# Sheet_1_2023-02-03.net
KiCad netlist of a schematic drawn in Altium Designer
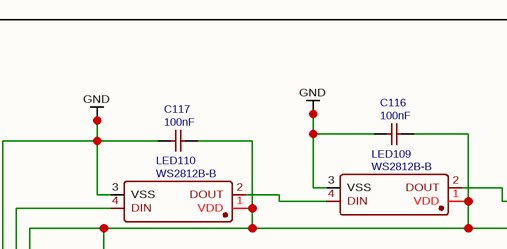
[diagram p0: Sheet_1_2023-02-03.schdoc, row 1 of 4 left]
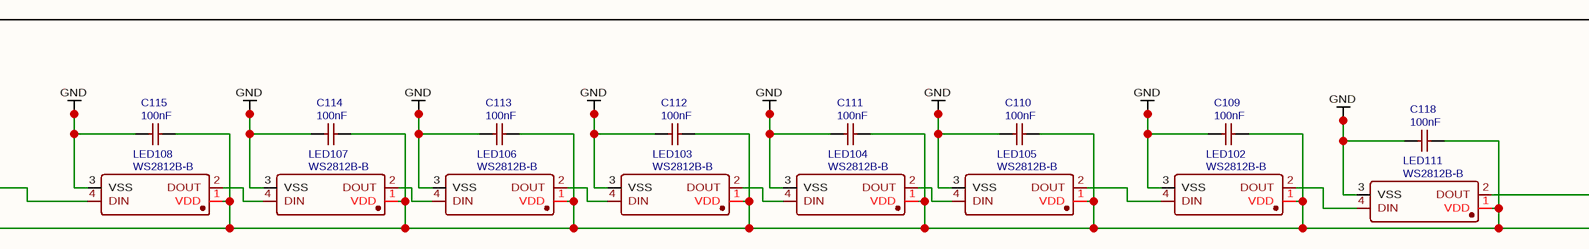
[diagram p1: Sheet_1_2023-02-03.schdoc, row 1 of 4 middle]
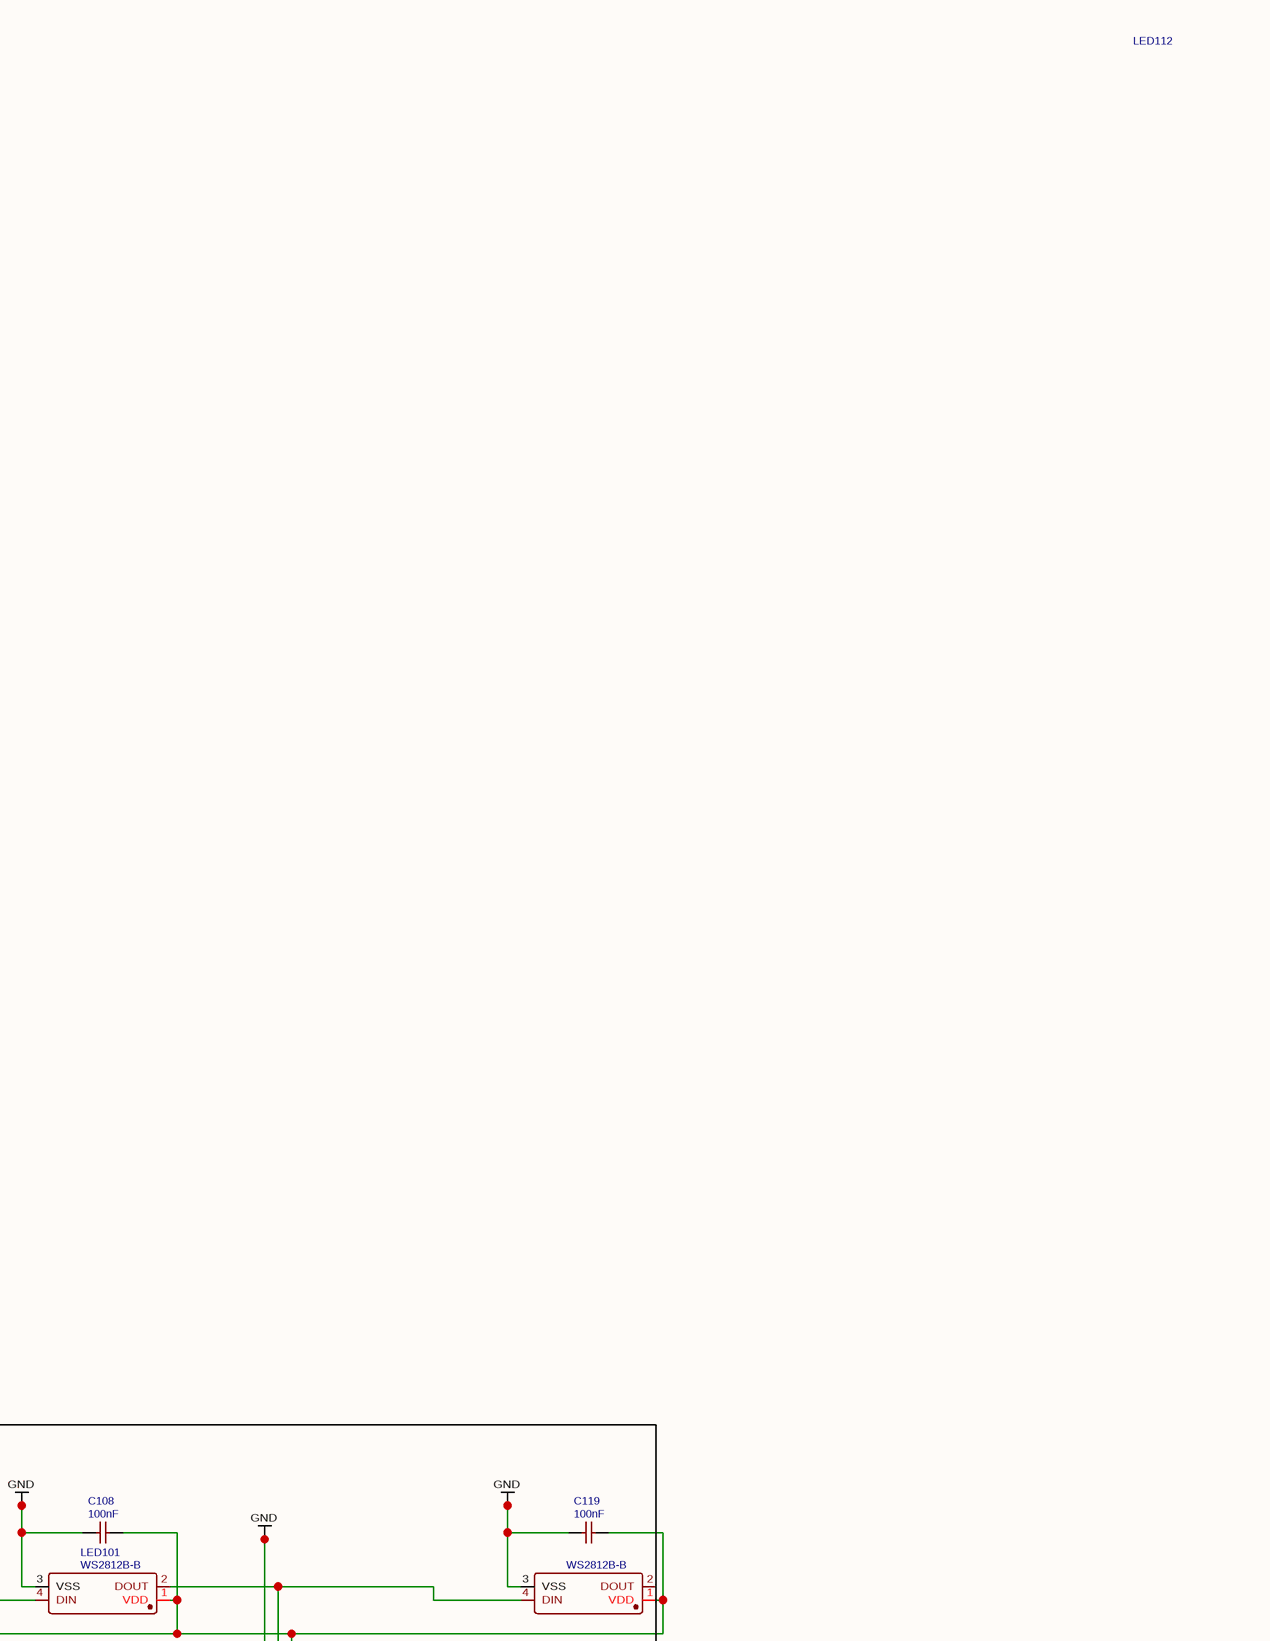
[diagram p2: Sheet_1_2023-02-03.schdoc, row 1 of 4 right]
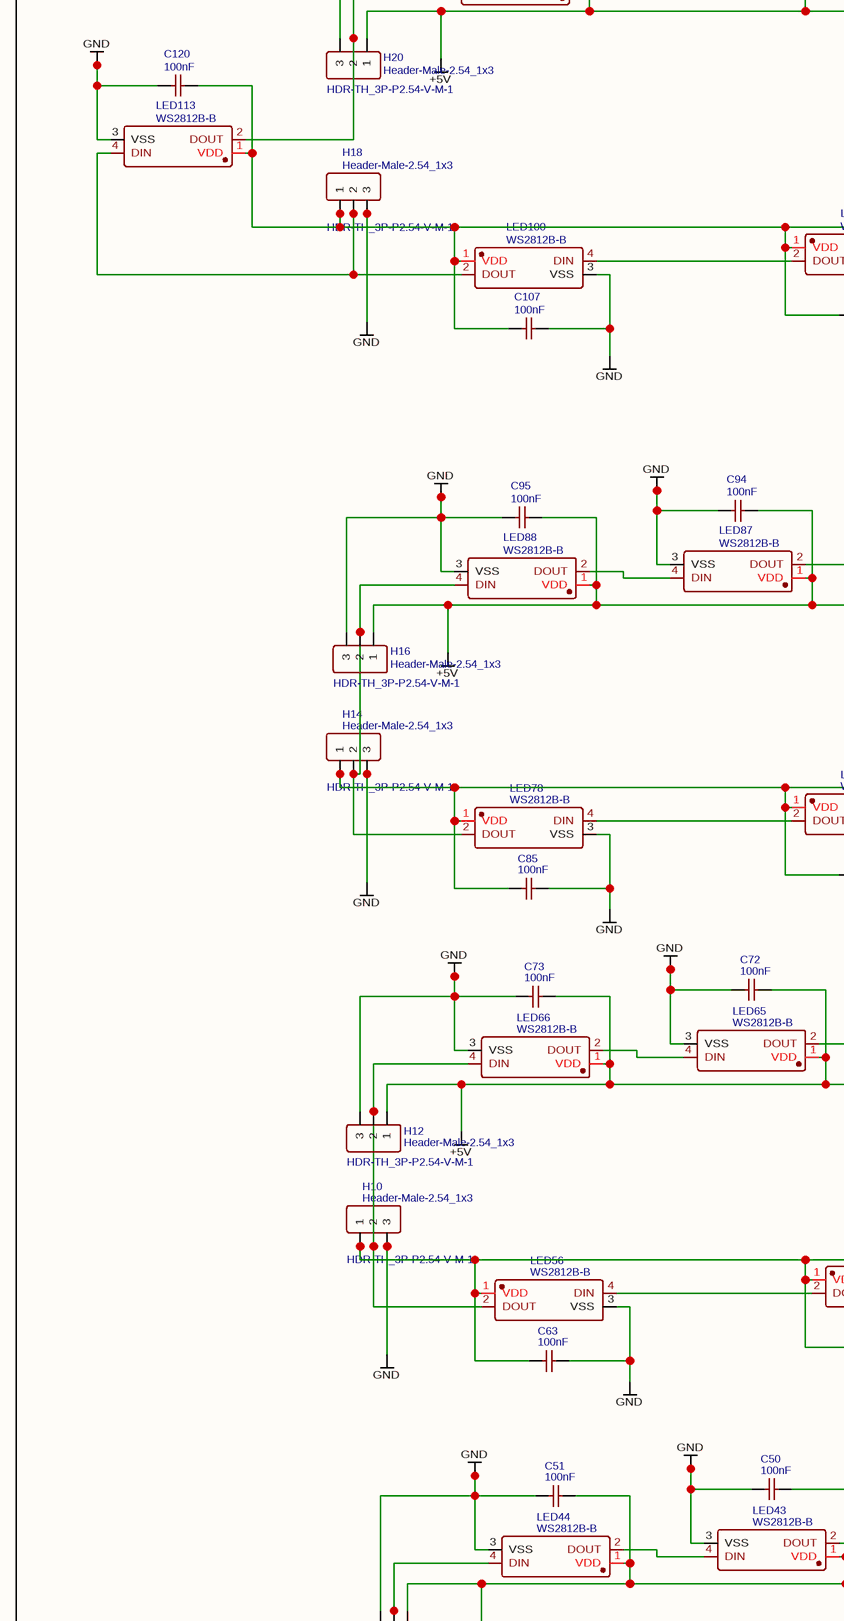
[diagram p3: Sheet_1_2023-02-03.schdoc, row 2 of 4 left]
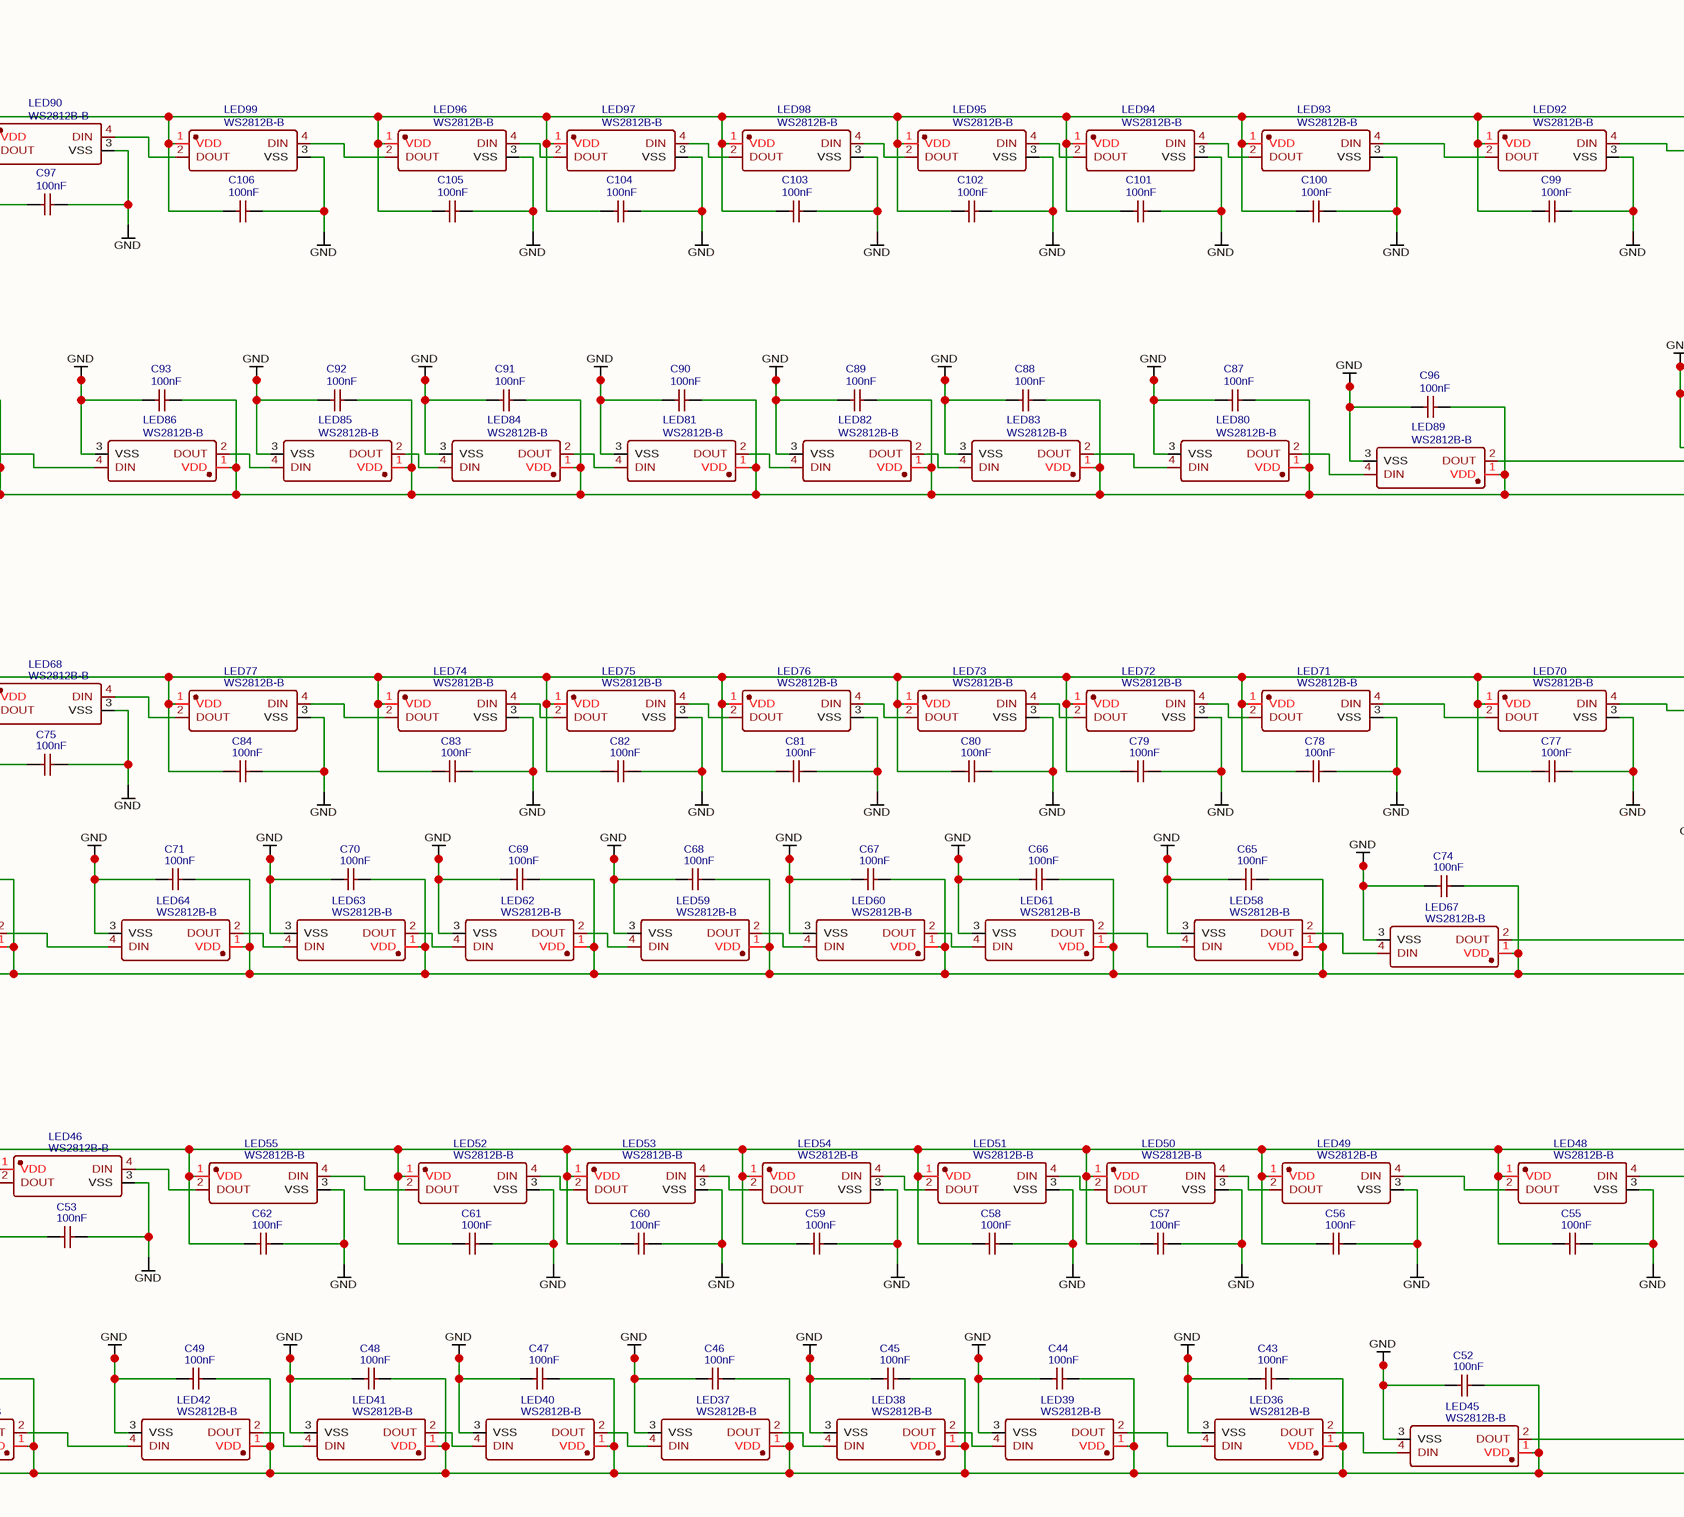
[diagram p4: Sheet_1_2023-02-03.schdoc, row 2 of 4 middle]
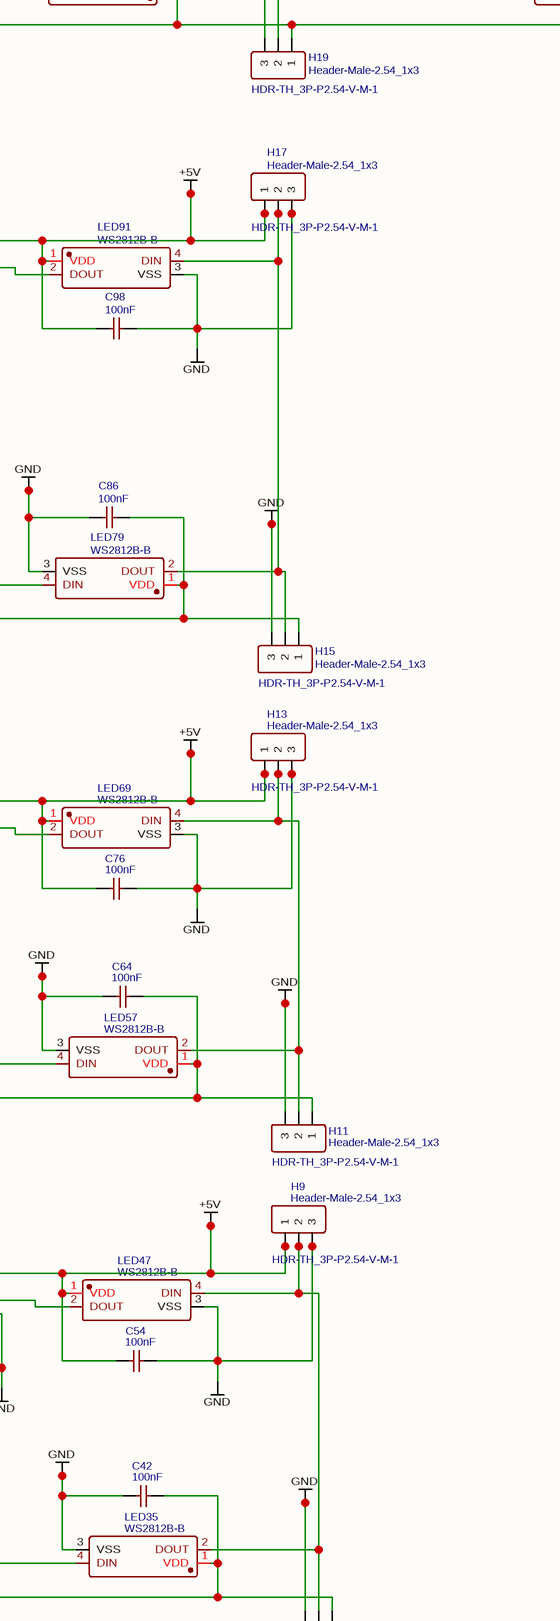
[diagram p5: Sheet_1_2023-02-03.schdoc, row 2 of 4 right]
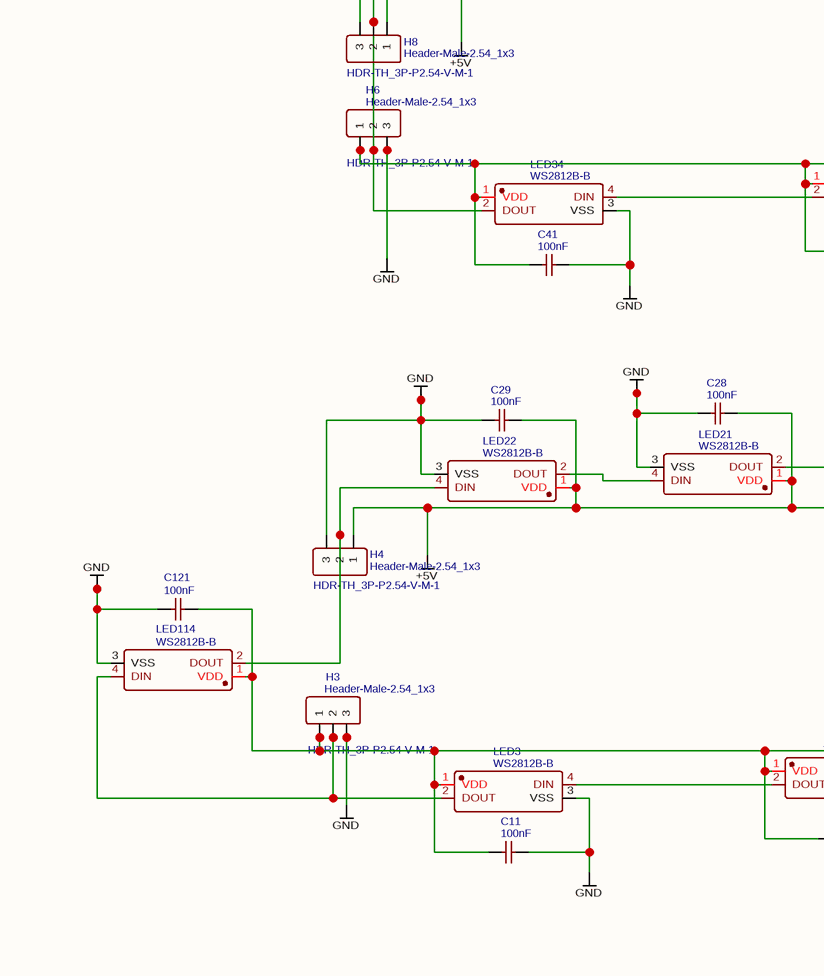
[diagram p6: Sheet_1_2023-02-03.schdoc, row 3 of 4 left]
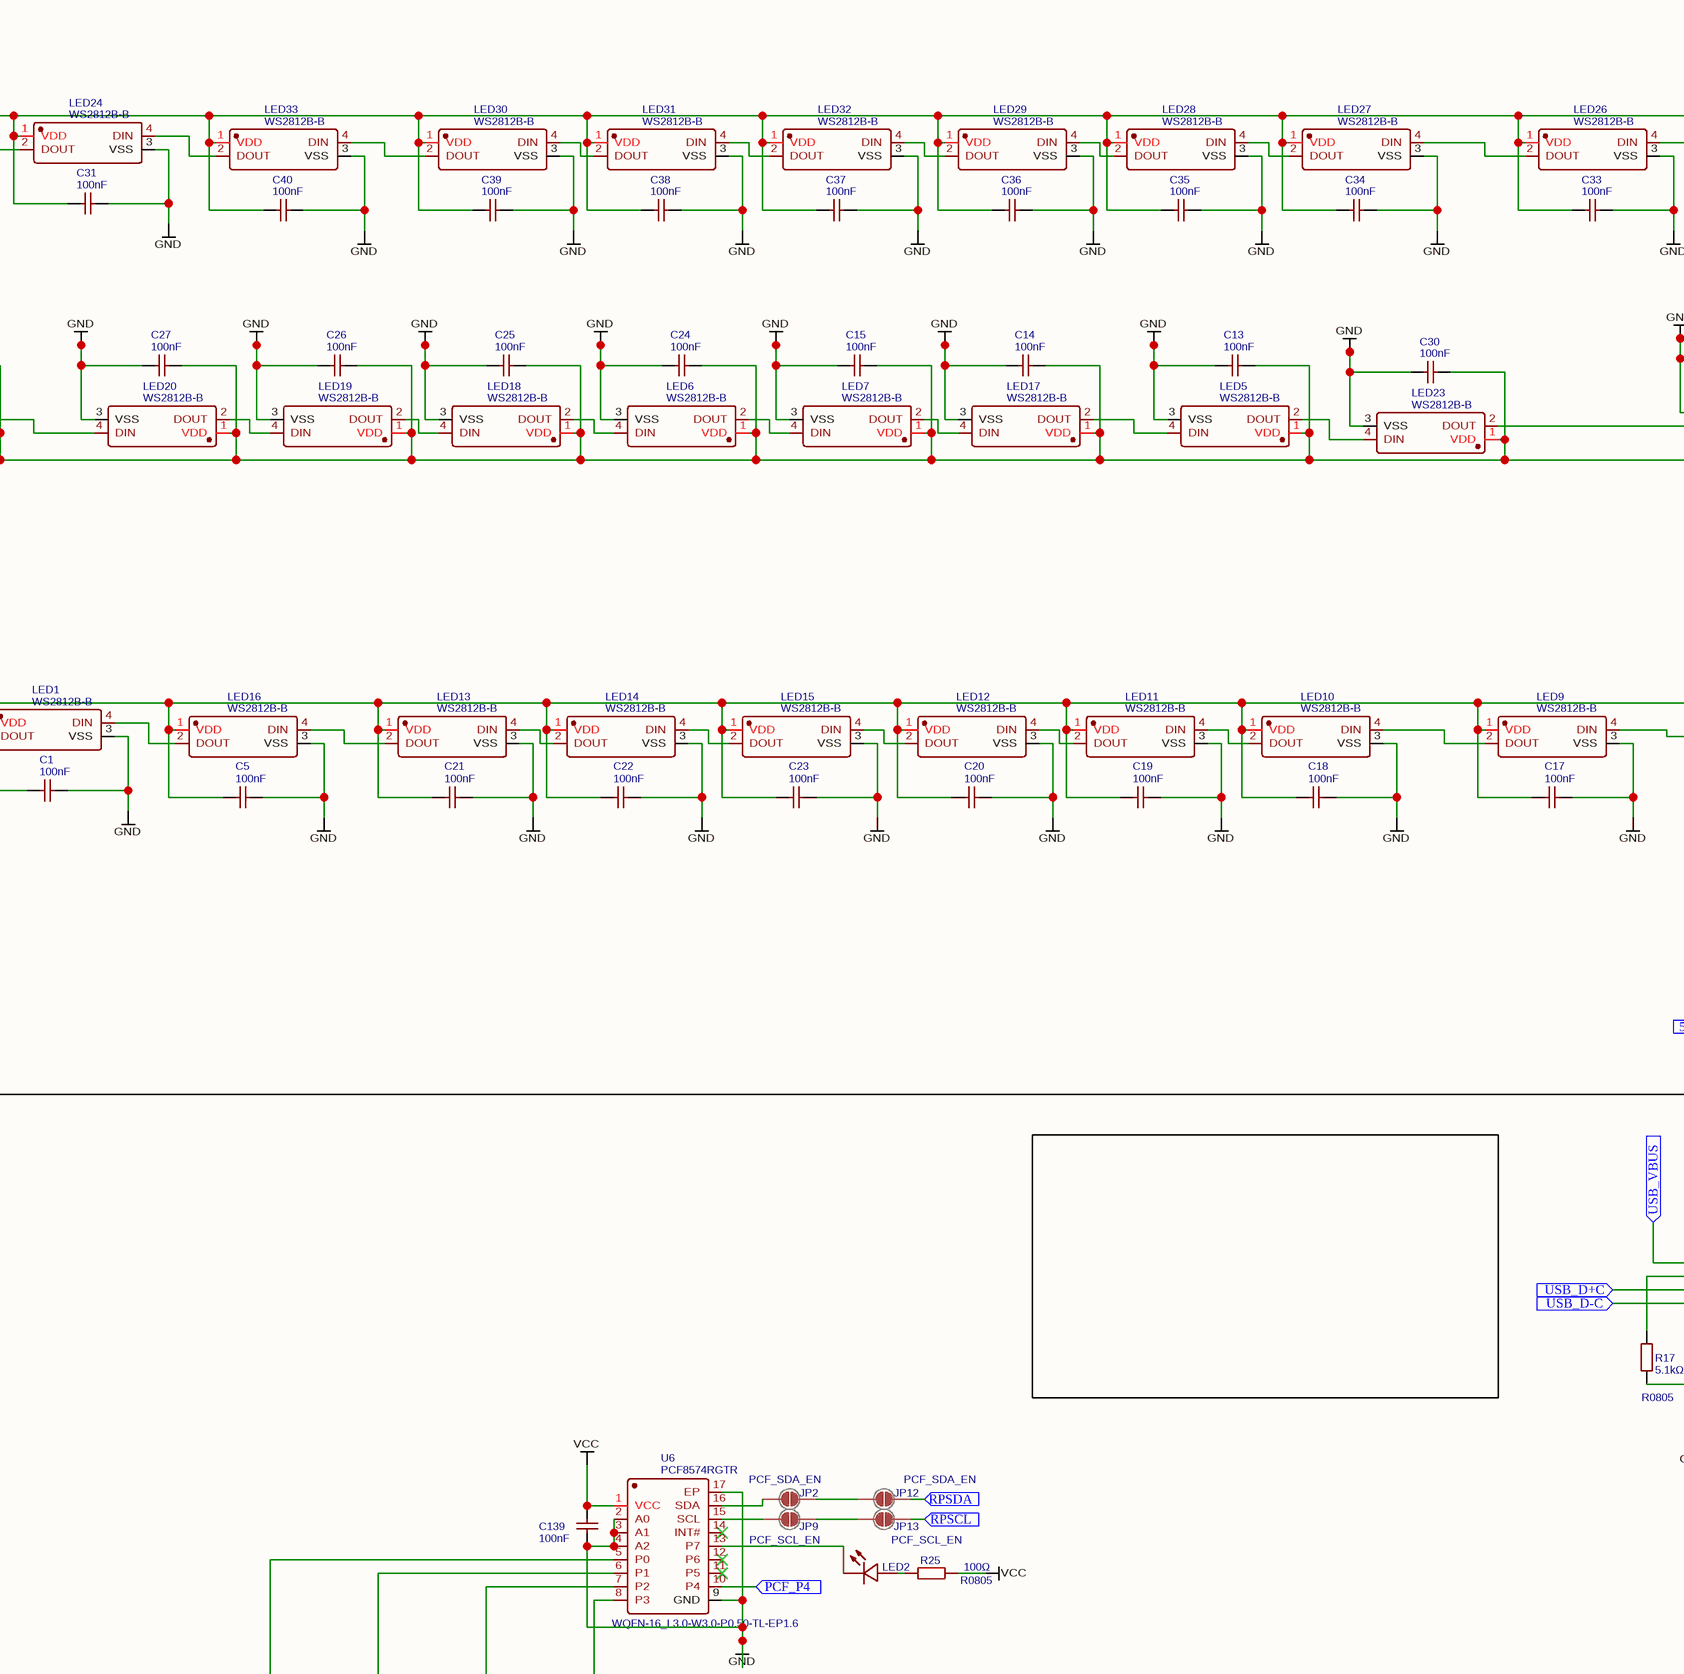
[diagram p7: Sheet_1_2023-02-03.schdoc, row 3 of 4 middle]
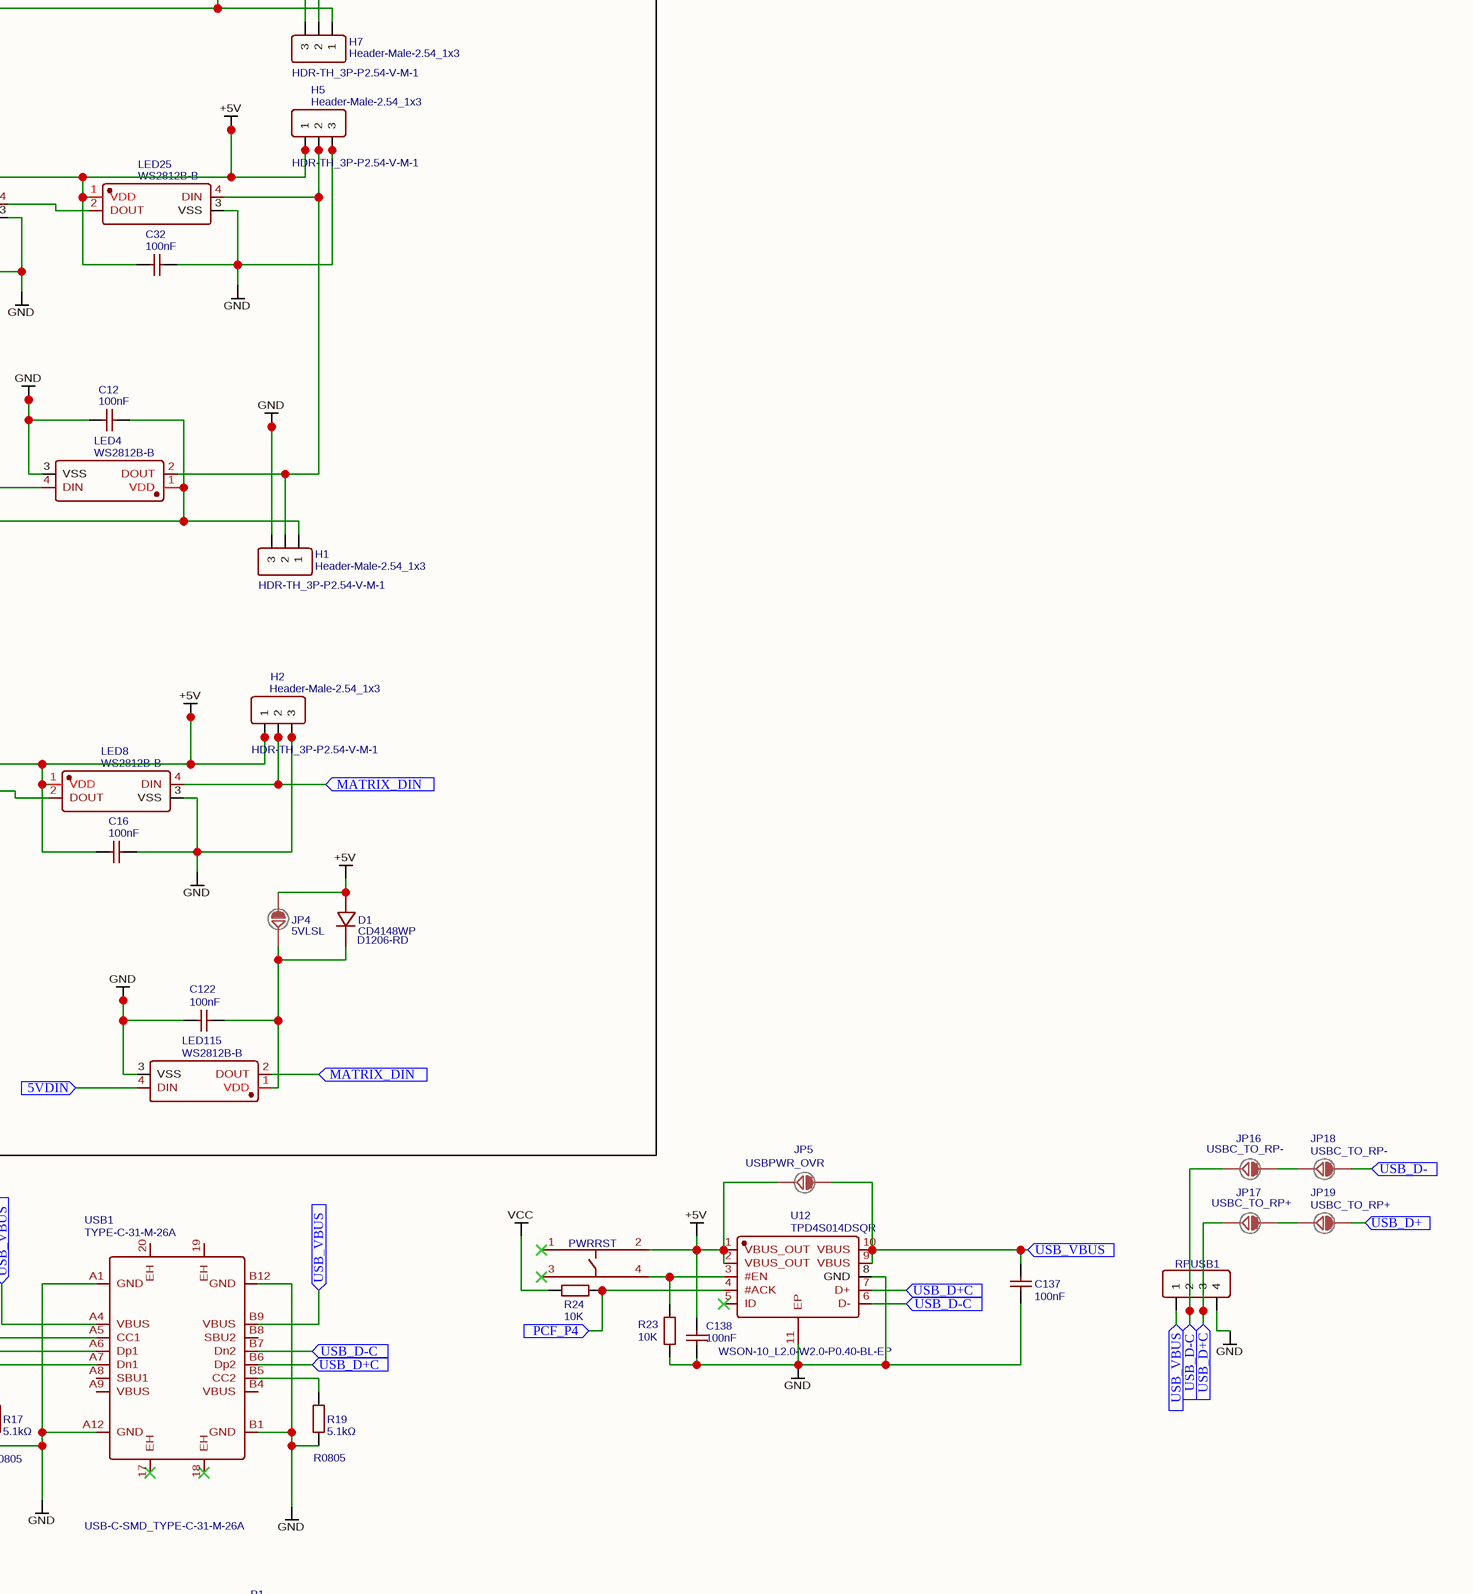
[diagram p8: Sheet_1_2023-02-03.schdoc, row 3 of 4 right]
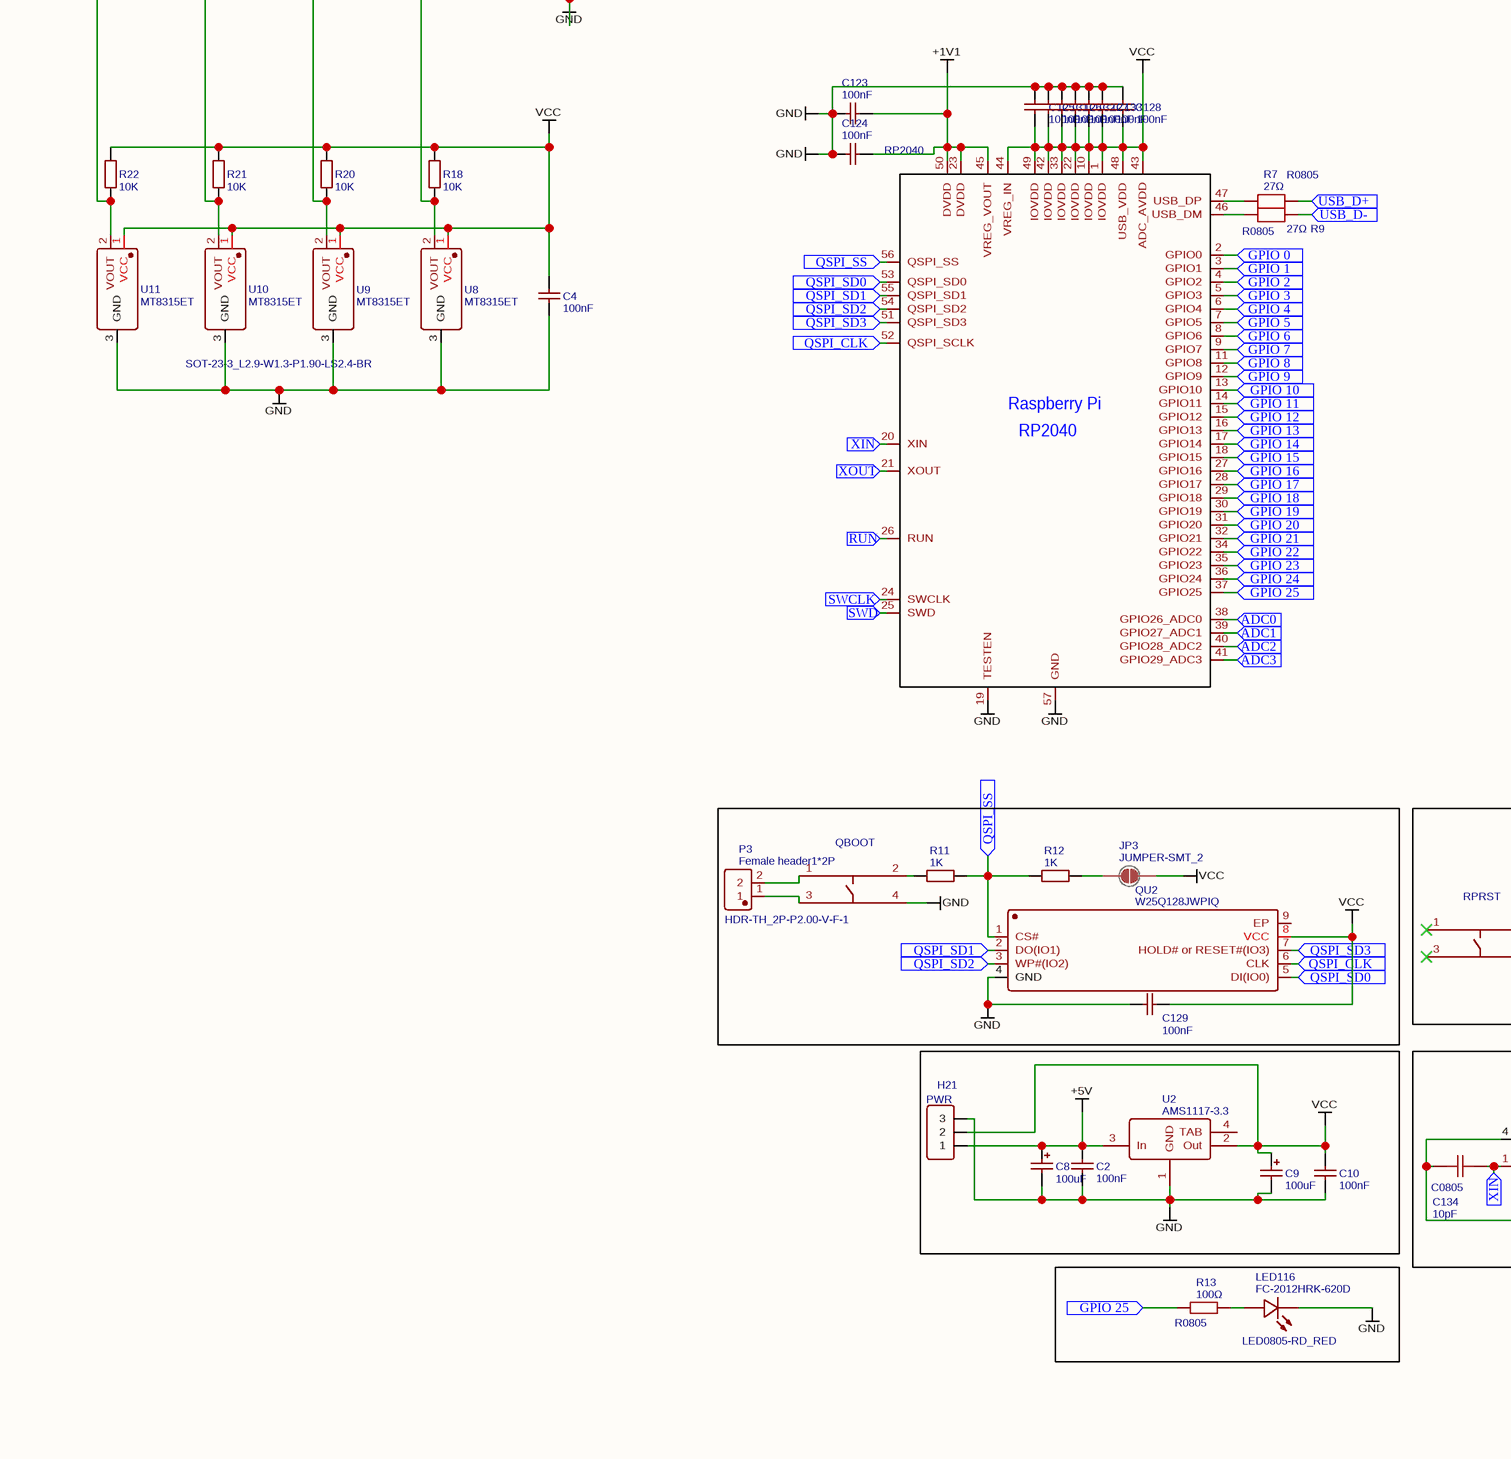
[diagram p9: Sheet_1_2023-02-03.schdoc, row 4 of 4 middle]
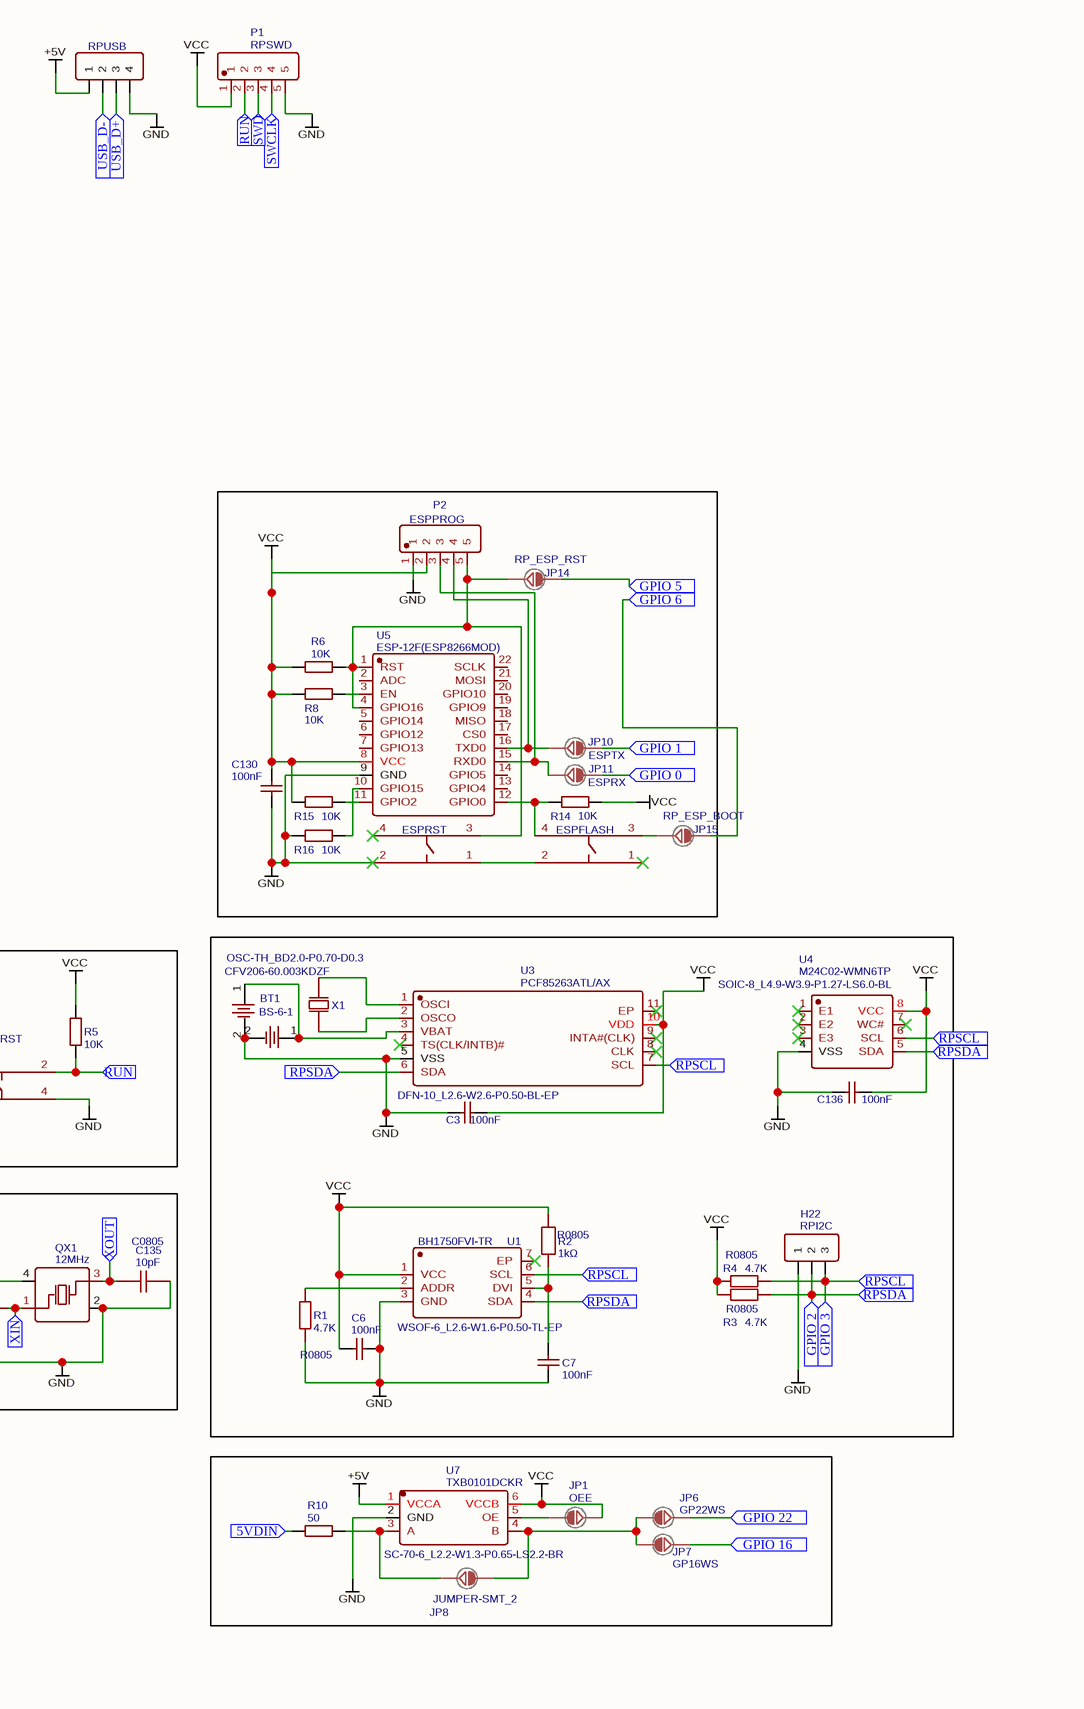
[diagram p10: Sheet_1_2023-02-03.schdoc, row 4 of 4 right]

(export (version "E")
  (design (tool "Eeschema 10.0.6"))
  (components
    (comp (ref "BT1")
      (value "BS-6-1")
      (fields (field (name "BOM_SUPPLIER PART") "C969909") (field (name "CONTRIBUTOR") "LCSC"))
      (libsource (lib "altium-import") (part "root_0_BS-6-1_"))
    )
    (comp (ref "BT2")
      (value "BS-6-1")
      (fields (field (name "BOM_SUPPLIER PART") "C969909") (field (name "CONTRIBUTOR") "LCSC"))
      (libsource (lib "altium-import") (part "root_1_BS-6-1_"))
    )
    (comp (ref "C1")
      (value "100nF")
      (fields
        (field (name "BOM_MANUFACTURER PART") "CC0805KRX7R9BB104")
        (field (name "BOM_SUPPLIER PART") "C49678")
      )
      (libsource (lib "altium-import") (part "root_0_100nF_"))
    )
    (comp (ref "C2")
      (value "100nF")
      (fields
        (field (name "BOM_MANUFACTURER PART") "CC0805KRX7R9BB104")
        (field (name "BOM_SUPPLIER PART") "C49678")
      )
      (libsource (lib "altium-import") (part "root_1_100nF_"))
    )
    (comp (ref "C3")
      (value "100nF")
      (fields
        (field (name "BOM_MANUFACTURER PART") "CC0805KRX7R9BB104")
        (field (name "BOM_SUPPLIER PART") "C49678")
      )
      (libsource (lib "altium-import") (part "root_2_100nF_"))
    )
    (comp (ref "C4")
      (value "100nF")
      (fields
        (field (name "BOM_MANUFACTURER PART") "CC0805KRX7R9BB104")
        (field (name "BOM_SUPPLIER PART") "C49678")
      )
      (libsource (lib "altium-import") (part "root_3_100nF_"))
    )
    (comp (ref "C5")
      (value "100nF")
      (fields
        (field (name "BOM_MANUFACTURER PART") "CC0805KRX7R9BB104")
        (field (name "BOM_SUPPLIER PART") "C49678")
      )
      (libsource (lib "altium-import") (part "root_0_100nF_"))
    )
    (comp (ref "C6")
      (value "100nF")
      (fields
        (field (name "BOM_MANUFACTURER PART") "CC0805KRX7R9BB104")
        (field (name "BOM_SUPPLIER PART") "C49678")
      )
      (libsource (lib "altium-import") (part "root_2_100nF_"))
    )
    (comp (ref "C7")
      (value "100nF")
      (fields
        (field (name "BOM_MANUFACTURER PART") "CC0805KRX7R9BB104")
        (field (name "BOM_SUPPLIER PART") "C49678")
      )
      (libsource (lib "altium-import") (part "root_3_100nF_"))
    )
    (comp (ref "C8")
      (value "100uF")
      (fields
        (field (name "BOM_MANUFACTURER PART") "TAJB107K006RNJ")
        (field (name "BOM_SUPPLIER PART") "C16133")
      )
      (libsource (lib "altium-import") (part "root_3_100uF_"))
    )
    (comp (ref "C9")
      (value "100uF")
      (fields
        (field (name "BOM_MANUFACTURER PART") "TAJB107K006RNJ")
        (field (name "BOM_SUPPLIER PART") "C16133")
      )
      (libsource (lib "altium-import") (part "root_3_100uF_"))
    )
    (comp (ref "C10")
      (value "100nF")
      (fields
        (field (name "BOM_MANUFACTURER PART") "CC0805KRX7R9BB104")
        (field (name "BOM_SUPPLIER PART") "C49678")
      )
      (libsource (lib "altium-import") (part "root_1_100nF_"))
    )
    (comp (ref "C11")
      (value "100nF")
      (fields
        (field (name "BOM_MANUFACTURER PART") "CC0805KRX7R9BB104")
        (field (name "BOM_SUPPLIER PART") "C49678")
      )
      (libsource (lib "altium-import") (part "root_0_100nF_"))
    )
    (comp (ref "C12")
      (value "100nF")
      (fields
        (field (name "BOM_MANUFACTURER PART") "CC0805KRX7R9BB104")
        (field (name "BOM_SUPPLIER PART") "C49678")
      )
      (libsource (lib "altium-import") (part "root_2_100nF_"))
    )
    (comp (ref "C13")
      (value "100nF")
      (fields
        (field (name "BOM_MANUFACTURER PART") "CC0805KRX7R9BB104")
        (field (name "BOM_SUPPLIER PART") "C49678")
      )
      (libsource (lib "altium-import") (part "root_2_100nF_"))
    )
    (comp (ref "C14")
      (value "100nF")
      (fields
        (field (name "BOM_MANUFACTURER PART") "CC0805KRX7R9BB104")
        (field (name "BOM_SUPPLIER PART") "C49678")
      )
      (libsource (lib "altium-import") (part "root_2_100nF_"))
    )
    (comp (ref "C15")
      (value "100nF")
      (fields
        (field (name "BOM_MANUFACTURER PART") "CC0805KRX7R9BB104")
        (field (name "BOM_SUPPLIER PART") "C49678")
      )
      (libsource (lib "altium-import") (part "root_2_100nF_"))
    )
    (comp (ref "C16")
      (value "100nF")
      (fields
        (field (name "BOM_MANUFACTURER PART") "CC0805KRX7R9BB104")
        (field (name "BOM_SUPPLIER PART") "C49678")
      )
      (libsource (lib "altium-import") (part "root_0_100nF_"))
    )
    (comp (ref "C17")
      (value "100nF")
      (fields
        (field (name "BOM_MANUFACTURER PART") "CC0805KRX7R9BB104")
        (field (name "BOM_SUPPLIER PART") "C49678")
      )
      (libsource (lib "altium-import") (part "root_0_100nF_"))
    )
    (comp (ref "C18")
      (value "100nF")
      (fields
        (field (name "BOM_MANUFACTURER PART") "CC0805KRX7R9BB104")
        (field (name "BOM_SUPPLIER PART") "C49678")
      )
      (libsource (lib "altium-import") (part "root_0_100nF_"))
    )
    (comp (ref "C19")
      (value "100nF")
      (fields
        (field (name "BOM_MANUFACTURER PART") "CC0805KRX7R9BB104")
        (field (name "BOM_SUPPLIER PART") "C49678")
      )
      (libsource (lib "altium-import") (part "root_0_100nF_"))
    )
    (comp (ref "C20")
      (value "100nF")
      (fields
        (field (name "BOM_MANUFACTURER PART") "CC0805KRX7R9BB104")
        (field (name "BOM_SUPPLIER PART") "C49678")
      )
      (libsource (lib "altium-import") (part "root_0_100nF_"))
    )
    (comp (ref "C21")
      (value "100nF")
      (fields
        (field (name "BOM_MANUFACTURER PART") "CC0805KRX7R9BB104")
        (field (name "BOM_SUPPLIER PART") "C49678")
      )
      (libsource (lib "altium-import") (part "root_0_100nF_"))
    )
    (comp (ref "C22")
      (value "100nF")
      (fields
        (field (name "BOM_MANUFACTURER PART") "CC0805KRX7R9BB104")
        (field (name "BOM_SUPPLIER PART") "C49678")
      )
      (libsource (lib "altium-import") (part "root_0_100nF_"))
    )
    (comp (ref "C23")
      (value "100nF")
      (fields
        (field (name "BOM_MANUFACTURER PART") "CC0805KRX7R9BB104")
        (field (name "BOM_SUPPLIER PART") "C49678")
      )
      (libsource (lib "altium-import") (part "root_0_100nF_"))
    )
    (comp (ref "C24")
      (value "100nF")
      (fields
        (field (name "BOM_MANUFACTURER PART") "CC0805KRX7R9BB104")
        (field (name "BOM_SUPPLIER PART") "C49678")
      )
      (libsource (lib "altium-import") (part "root_2_100nF_"))
    )
    (comp (ref "C25")
      (value "100nF")
      (fields
        (field (name "BOM_MANUFACTURER PART") "CC0805KRX7R9BB104")
        (field (name "BOM_SUPPLIER PART") "C49678")
      )
      (libsource (lib "altium-import") (part "root_2_100nF_"))
    )
    (comp (ref "C26")
      (value "100nF")
      (fields
        (field (name "BOM_MANUFACTURER PART") "CC0805KRX7R9BB104")
        (field (name "BOM_SUPPLIER PART") "C49678")
      )
      (libsource (lib "altium-import") (part "root_2_100nF_"))
    )
    (comp (ref "C27")
      (value "100nF")
      (fields
        (field (name "BOM_MANUFACTURER PART") "CC0805KRX7R9BB104")
        (field (name "BOM_SUPPLIER PART") "C49678")
      )
      (libsource (lib "altium-import") (part "root_2_100nF_"))
    )
    (comp (ref "C28")
      (value "100nF")
      (fields
        (field (name "BOM_MANUFACTURER PART") "CC0805KRX7R9BB104")
        (field (name "BOM_SUPPLIER PART") "C49678")
      )
      (libsource (lib "altium-import") (part "root_2_100nF_"))
    )
    (comp (ref "C29")
      (value "100nF")
      (fields
        (field (name "BOM_MANUFACTURER PART") "CC0805KRX7R9BB104")
        (field (name "BOM_SUPPLIER PART") "C49678")
      )
      (libsource (lib "altium-import") (part "root_2_100nF_"))
    )
    (comp (ref "C30")
      (value "100nF")
      (fields
        (field (name "BOM_MANUFACTURER PART") "CC0805KRX7R9BB104")
        (field (name "BOM_SUPPLIER PART") "C49678")
      )
      (libsource (lib "altium-import") (part "root_2_100nF_"))
    )
    (comp (ref "C31")
      (value "100nF")
      (fields
        (field (name "BOM_MANUFACTURER PART") "CC0805KRX7R9BB104")
        (field (name "BOM_SUPPLIER PART") "C49678")
      )
      (libsource (lib "altium-import") (part "root_0_100nF_"))
    )
    (comp (ref "C32")
      (value "100nF")
      (fields
        (field (name "BOM_MANUFACTURER PART") "CC0805KRX7R9BB104")
        (field (name "BOM_SUPPLIER PART") "C49678")
      )
      (libsource (lib "altium-import") (part "root_0_100nF_"))
    )
    (comp (ref "C33")
      (value "100nF")
      (fields
        (field (name "BOM_MANUFACTURER PART") "CC0805KRX7R9BB104")
        (field (name "BOM_SUPPLIER PART") "C49678")
      )
      (libsource (lib "altium-import") (part "root_0_100nF_"))
    )
    (comp (ref "C34")
      (value "100nF")
      (fields
        (field (name "BOM_MANUFACTURER PART") "CC0805KRX7R9BB104")
        (field (name "BOM_SUPPLIER PART") "C49678")
      )
      (libsource (lib "altium-import") (part "root_0_100nF_"))
    )
    (comp (ref "C35")
      (value "100nF")
      (fields
        (field (name "BOM_MANUFACTURER PART") "CC0805KRX7R9BB104")
        (field (name "BOM_SUPPLIER PART") "C49678")
      )
      (libsource (lib "altium-import") (part "root_0_100nF_"))
    )
    (comp (ref "C36")
      (value "100nF")
      (fields
        (field (name "BOM_MANUFACTURER PART") "CC0805KRX7R9BB104")
        (field (name "BOM_SUPPLIER PART") "C49678")
      )
      (libsource (lib "altium-import") (part "root_0_100nF_"))
    )
    (comp (ref "C37")
      (value "100nF")
      (fields
        (field (name "BOM_MANUFACTURER PART") "CC0805KRX7R9BB104")
        (field (name "BOM_SUPPLIER PART") "C49678")
      )
      (libsource (lib "altium-import") (part "root_0_100nF_"))
    )
    (comp (ref "C38")
      (value "100nF")
      (fields
        (field (name "BOM_MANUFACTURER PART") "CC0805KRX7R9BB104")
        (field (name "BOM_SUPPLIER PART") "C49678")
      )
      (libsource (lib "altium-import") (part "root_0_100nF_"))
    )
    (comp (ref "C39")
      (value "100nF")
      (fields
        (field (name "BOM_MANUFACTURER PART") "CC0805KRX7R9BB104")
        (field (name "BOM_SUPPLIER PART") "C49678")
      )
      (libsource (lib "altium-import") (part "root_0_100nF_"))
    )
    (comp (ref "C40")
      (value "100nF")
      (fields
        (field (name "BOM_MANUFACTURER PART") "CC0805KRX7R9BB104")
        (field (name "BOM_SUPPLIER PART") "C49678")
      )
      (libsource (lib "altium-import") (part "root_0_100nF_"))
    )
    (comp (ref "C41")
      (value "100nF")
      (fields
        (field (name "BOM_MANUFACTURER PART") "CC0805KRX7R9BB104")
        (field (name "BOM_SUPPLIER PART") "C49678")
      )
      (libsource (lib "altium-import") (part "root_0_100nF_"))
    )
    (comp (ref "C42")
      (value "100nF")
      (fields
        (field (name "BOM_MANUFACTURER PART") "CC0805KRX7R9BB104")
        (field (name "BOM_SUPPLIER PART") "C49678")
      )
      (libsource (lib "altium-import") (part "root_2_100nF_"))
    )
    (comp (ref "C43")
      (value "100nF")
      (fields
        (field (name "BOM_MANUFACTURER PART") "CC0805KRX7R9BB104")
        (field (name "BOM_SUPPLIER PART") "C49678")
      )
      (libsource (lib "altium-import") (part "root_2_100nF_"))
    )
    (comp (ref "C44")
      (value "100nF")
      (fields
        (field (name "BOM_MANUFACTURER PART") "CC0805KRX7R9BB104")
        (field (name "BOM_SUPPLIER PART") "C49678")
      )
      (libsource (lib "altium-import") (part "root_2_100nF_"))
    )
    (comp (ref "C45")
      (value "100nF")
      (fields
        (field (name "BOM_MANUFACTURER PART") "CC0805KRX7R9BB104")
        (field (name "BOM_SUPPLIER PART") "C49678")
      )
      (libsource (lib "altium-import") (part "root_2_100nF_"))
    )
    (comp (ref "C46")
      (value "100nF")
      (fields
        (field (name "BOM_MANUFACTURER PART") "CC0805KRX7R9BB104")
        (field (name "BOM_SUPPLIER PART") "C49678")
      )
      (libsource (lib "altium-import") (part "root_2_100nF_"))
    )
    (comp (ref "C47")
      (value "100nF")
      (fields
        (field (name "BOM_MANUFACTURER PART") "CC0805KRX7R9BB104")
        (field (name "BOM_SUPPLIER PART") "C49678")
      )
      (libsource (lib "altium-import") (part "root_2_100nF_"))
    )
    (comp (ref "C48")
      (value "100nF")
      (fields
        (field (name "BOM_MANUFACTURER PART") "CC0805KRX7R9BB104")
        (field (name "BOM_SUPPLIER PART") "C49678")
      )
      (libsource (lib "altium-import") (part "root_2_100nF_"))
    )
    (comp (ref "C49")
      (value "100nF")
      (fields
        (field (name "BOM_MANUFACTURER PART") "CC0805KRX7R9BB104")
        (field (name "BOM_SUPPLIER PART") "C49678")
      )
      (libsource (lib "altium-import") (part "root_2_100nF_"))
    )
    (comp (ref "C50")
      (value "100nF")
      (fields
        (field (name "BOM_MANUFACTURER PART") "CC0805KRX7R9BB104")
        (field (name "BOM_SUPPLIER PART") "C49678")
      )
      (libsource (lib "altium-import") (part "root_2_100nF_"))
    )
    (comp (ref "C51")
      (value "100nF")
      (fields
        (field (name "BOM_MANUFACTURER PART") "CC0805KRX7R9BB104")
        (field (name "BOM_SUPPLIER PART") "C49678")
      )
      (libsource (lib "altium-import") (part "root_2_100nF_"))
    )
    (comp (ref "C52")
      (value "100nF")
      (fields
        (field (name "BOM_MANUFACTURER PART") "CC0805KRX7R9BB104")
        (field (name "BOM_SUPPLIER PART") "C49678")
      )
      (libsource (lib "altium-import") (part "root_2_100nF_"))
    )
    (comp (ref "C53")
      (value "100nF")
      (fields
        (field (name "BOM_MANUFACTURER PART") "CC0805KRX7R9BB104")
        (field (name "BOM_SUPPLIER PART") "C49678")
      )
      (libsource (lib "altium-import") (part "root_0_100nF_"))
    )
    (comp (ref "C54")
      (value "100nF")
      (fields
        (field (name "BOM_MANUFACTURER PART") "CC0805KRX7R9BB104")
        (field (name "BOM_SUPPLIER PART") "C49678")
      )
      (libsource (lib "altium-import") (part "root_0_100nF_"))
    )
    (comp (ref "C55")
      (value "100nF")
      (fields
        (field (name "BOM_MANUFACTURER PART") "CC0805KRX7R9BB104")
        (field (name "BOM_SUPPLIER PART") "C49678")
      )
      (libsource (lib "altium-import") (part "root_0_100nF_"))
    )
    (comp (ref "C56")
      (value "100nF")
      (fields
        (field (name "BOM_MANUFACTURER PART") "CC0805KRX7R9BB104")
        (field (name "BOM_SUPPLIER PART") "C49678")
      )
      (libsource (lib "altium-import") (part "root_0_100nF_"))
    )
    (comp (ref "C57")
      (value "100nF")
      (fields
        (field (name "BOM_MANUFACTURER PART") "CC0805KRX7R9BB104")
        (field (name "BOM_SUPPLIER PART") "C49678")
      )
      (libsource (lib "altium-import") (part "root_0_100nF_"))
    )
    (comp (ref "C58")
      (value "100nF")
      (fields
        (field (name "BOM_MANUFACTURER PART") "CC0805KRX7R9BB104")
        (field (name "BOM_SUPPLIER PART") "C49678")
      )
      (libsource (lib "altium-import") (part "root_0_100nF_"))
    )
    (comp (ref "C59")
      (value "100nF")
      (fields
        (field (name "BOM_MANUFACTURER PART") "CC0805KRX7R9BB104")
        (field (name "BOM_SUPPLIER PART") "C49678")
      )
      (libsource (lib "altium-import") (part "root_0_100nF_"))
    )
    (comp (ref "C60")
      (value "100nF")
      (fields
        (field (name "BOM_MANUFACTURER PART") "CC0805KRX7R9BB104")
        (field (name "BOM_SUPPLIER PART") "C49678")
      )
      (libsource (lib "altium-import") (part "root_0_100nF_"))
    )
    (comp (ref "C61")
      (value "100nF")
      (fields
        (field (name "BOM_MANUFACTURER PART") "CC0805KRX7R9BB104")
        (field (name "BOM_SUPPLIER PART") "C49678")
      )
      (libsource (lib "altium-import") (part "root_0_100nF_"))
    )
    (comp (ref "C62")
      (value "100nF")
      (fields
        (field (name "BOM_MANUFACTURER PART") "CC0805KRX7R9BB104")
        (field (name "BOM_SUPPLIER PART") "C49678")
      )
      (libsource (lib "altium-import") (part "root_0_100nF_"))
    )
    (comp (ref "C63")
      (value "100nF")
      (fields
        (field (name "BOM_MANUFACTURER PART") "CC0805KRX7R9BB104")
        (field (name "BOM_SUPPLIER PART") "C49678")
      )
      (libsource (lib "altium-import") (part "root_0_100nF_"))
    )
    (comp (ref "C64")
      (value "100nF")
      (fields
        (field (name "BOM_MANUFACTURER PART") "CC0805KRX7R9BB104")
        (field (name "BOM_SUPPLIER PART") "C49678")
      )
      (libsource (lib "altium-import") (part "root_2_100nF_"))
    )
    (comp (ref "C65")
      (value "100nF")
      (fields
        (field (name "BOM_MANUFACTURER PART") "CC0805KRX7R9BB104")
        (field (name "BOM_SUPPLIER PART") "C49678")
      )
      (libsource (lib "altium-import") (part "root_2_100nF_"))
    )
    (comp (ref "C66")
      (value "100nF")
      (fields
        (field (name "BOM_MANUFACTURER PART") "CC0805KRX7R9BB104")
        (field (name "BOM_SUPPLIER PART") "C49678")
      )
      (libsource (lib "altium-import") (part "root_2_100nF_"))
    )
    (comp (ref "C67")
      (value "100nF")
      (fields
        (field (name "BOM_MANUFACTURER PART") "CC0805KRX7R9BB104")
        (field (name "BOM_SUPPLIER PART") "C49678")
      )
      (libsource (lib "altium-import") (part "root_2_100nF_"))
    )
    (comp (ref "C68")
      (value "100nF")
      (fields
        (field (name "BOM_MANUFACTURER PART") "CC0805KRX7R9BB104")
        (field (name "BOM_SUPPLIER PART") "C49678")
      )
      (libsource (lib "altium-import") (part "root_2_100nF_"))
    )
    (comp (ref "C69")
      (value "100nF")
      (fields
        (field (name "BOM_MANUFACTURER PART") "CC0805KRX7R9BB104")
        (field (name "BOM_SUPPLIER PART") "C49678")
      )
      (libsource (lib "altium-import") (part "root_2_100nF_"))
    )
    (comp (ref "C70")
      (value "100nF")
      (fields
        (field (name "BOM_MANUFACTURER PART") "CC0805KRX7R9BB104")
        (field (name "BOM_SUPPLIER PART") "C49678")
      )
      (libsource (lib "altium-import") (part "root_2_100nF_"))
    )
    (comp (ref "C71")
      (value "100nF")
      (fields
        (field (name "BOM_MANUFACTURER PART") "CC0805KRX7R9BB104")
        (field (name "BOM_SUPPLIER PART") "C49678")
      )
      (libsource (lib "altium-import") (part "root_2_100nF_"))
    )
    (comp (ref "C72")
      (value "100nF")
      (fields
        (field (name "BOM_MANUFACTURER PART") "CC0805KRX7R9BB104")
        (field (name "BOM_SUPPLIER PART") "C49678")
      )
      (libsource (lib "altium-import") (part "root_2_100nF_"))
    )
    (comp (ref "C73")
      (value "100nF")
      (fields
        (field (name "BOM_MANUFACTURER PART") "CC0805KRX7R9BB104")
        (field (name "BOM_SUPPLIER PART") "C49678")
      )
      (libsource (lib "altium-import") (part "root_2_100nF_"))
    )
    (comp (ref "C74")
      (value "100nF")
      (fields
        (field (name "BOM_MANUFACTURER PART") "CC0805KRX7R9BB104")
        (field (name "BOM_SUPPLIER PART") "C49678")
      )
      (libsource (lib "altium-import") (part "root_2_100nF_"))
    )
    (comp (ref "C75")
      (value "100nF")
      (fields
        (field (name "BOM_MANUFACTURER PART") "CC0805KRX7R9BB104")
        (field (name "BOM_SUPPLIER PART") "C49678")
      )
      (libsource (lib "altium-import") (part "root_0_100nF_"))
    )
    (comp (ref "C76")
      (value "100nF")
      (fields
        (field (name "BOM_MANUFACTURER PART") "CC0805KRX7R9BB104")
        (field (name "BOM_SUPPLIER PART") "C49678")
      )
      (libsource (lib "altium-import") (part "root_0_100nF_"))
    )
    (comp (ref "C77")
      (value "100nF")
      (fields
        (field (name "BOM_MANUFACTURER PART") "CC0805KRX7R9BB104")
        (field (name "BOM_SUPPLIER PART") "C49678")
      )
      (libsource (lib "altium-import") (part "root_0_100nF_"))
    )
    (comp (ref "C78")
      (value "100nF")
      (fields
        (field (name "BOM_MANUFACTURER PART") "CC0805KRX7R9BB104")
        (field (name "BOM_SUPPLIER PART") "C49678")
      )
      (libsource (lib "altium-import") (part "root_0_100nF_"))
    )
    (comp (ref "C79")
      (value "100nF")
      (fields
        (field (name "BOM_MANUFACTURER PART") "CC0805KRX7R9BB104")
        (field (name "BOM_SUPPLIER PART") "C49678")
      )
      (libsource (lib "altium-import") (part "root_0_100nF_"))
    )
    (comp (ref "C80")
      (value "100nF")
      (fields
        (field (name "BOM_MANUFACTURER PART") "CC0805KRX7R9BB104")
        (field (name "BOM_SUPPLIER PART") "C49678")
      )
      (libsource (lib "altium-import") (part "root_0_100nF_"))
    )
    (comp (ref "C81")
      (value "100nF")
      (fields
        (field (name "BOM_MANUFACTURER PART") "CC0805KRX7R9BB104")
        (field (name "BOM_SUPPLIER PART") "C49678")
      )
      (libsource (lib "altium-import") (part "root_0_100nF_"))
    )
    (comp (ref "C82")
      (value "100nF")
      (fields
        (field (name "BOM_MANUFACTURER PART") "CC0805KRX7R9BB104")
        (field (name "BOM_SUPPLIER PART") "C49678")
      )
      (libsource (lib "altium-import") (part "root_0_100nF_"))
    )
    (comp (ref "C83")
      (value "100nF")
      (fields
        (field (name "BOM_MANUFACTURER PART") "CC0805KRX7R9BB104")
        (field (name "BOM_SUPPLIER PART") "C49678")
      )
      (libsource (lib "altium-import") (part "root_0_100nF_"))
    )
    (comp (ref "C84")
      (value "100nF")
      (fields
        (field (name "BOM_MANUFACTURER PART") "CC0805KRX7R9BB104")
        (field (name "BOM_SUPPLIER PART") "C49678")
      )
      (libsource (lib "altium-import") (part "root_0_100nF_"))
    )
    (comp (ref "C85")
      (value "100nF")
      (fields
        (field (name "BOM_MANUFACTURER PART") "CC0805KRX7R9BB104")
        (field (name "BOM_SUPPLIER PART") "C49678")
      )
      (libsource (lib "altium-import") (part "root_0_100nF_"))
    )
    (comp (ref "C86")
      (value "100nF")
      (fields
        (field (name "BOM_MANUFACTURER PART") "CC0805KRX7R9BB104")
        (field (name "BOM_SUPPLIER PART") "C49678")
      )
      (libsource (lib "altium-import") (part "root_2_100nF_"))
    )
    (comp (ref "C87")
      (value "100nF")
      (fields
        (field (name "BOM_MANUFACTURER PART") "CC0805KRX7R9BB104")
        (field (name "BOM_SUPPLIER PART") "C49678")
      )
      (libsource (lib "altium-import") (part "root_2_100nF_"))
    )
    (comp (ref "C88")
      (value "100nF")
      (fields
        (field (name "BOM_MANUFACTURER PART") "CC0805KRX7R9BB104")
        (field (name "BOM_SUPPLIER PART") "C49678")
      )
      (libsource (lib "altium-import") (part "root_2_100nF_"))
    )
    (comp (ref "C89")
      (value "100nF")
      (fields
        (field (name "BOM_MANUFACTURER PART") "CC0805KRX7R9BB104")
        (field (name "BOM_SUPPLIER PART") "C49678")
      )
      (libsource (lib "altium-import") (part "root_2_100nF_"))
    )
    (comp (ref "C90")
      (value "100nF")
      (fields
        (field (name "BOM_MANUFACTURER PART") "CC0805KRX7R9BB104")
        (field (name "BOM_SUPPLIER PART") "C49678")
      )
      (libsource (lib "altium-import") (part "root_2_100nF_"))
    )
    (comp (ref "C91")
      (value "100nF")
      (fields
        (field (name "BOM_MANUFACTURER PART") "CC0805KRX7R9BB104")
        (field (name "BOM_SUPPLIER PART") "C49678")
      )
      (libsource (lib "altium-import") (part "root_2_100nF_"))
    )
    (comp (ref "C92")
      (value "100nF")
      (fields
        (field (name "BOM_MANUFACTURER PART") "CC0805KRX7R9BB104")
        (field (name "BOM_SUPPLIER PART") "C49678")
      )
      (libsource (lib "altium-import") (part "root_2_100nF_"))
    )
    (comp (ref "C93")
      (value "100nF")
      (fields
        (field (name "BOM_MANUFACTURER PART") "CC0805KRX7R9BB104")
        (field (name "BOM_SUPPLIER PART") "C49678")
      )
      (libsource (lib "altium-import") (part "root_2_100nF_"))
    )
    (comp (ref "C94")
      (value "100nF")
      (fields
        (field (name "BOM_MANUFACTURER PART") "CC0805KRX7R9BB104")
        (field (name "BOM_SUPPLIER PART") "C49678")
      )
      (libsource (lib "altium-import") (part "root_2_100nF_"))
    )
    (comp (ref "C95")
      (value "100nF")
      (fields
        (field (name "BOM_MANUFACTURER PART") "CC0805KRX7R9BB104")
        (field (name "BOM_SUPPLIER PART") "C49678")
      )
      (libsource (lib "altium-import") (part "root_2_100nF_"))
    )
    (comp (ref "C96")
      (value "100nF")
      (fields
        (field (name "BOM_MANUFACTURER PART") "CC0805KRX7R9BB104")
        (field (name "BOM_SUPPLIER PART") "C49678")
      )
      (libsource (lib "altium-import") (part "root_2_100nF_"))
    )
    (comp (ref "C97")
      (value "100nF")
      (fields
        (field (name "BOM_MANUFACTURER PART") "CC0805KRX7R9BB104")
        (field (name "BOM_SUPPLIER PART") "C49678")
      )
      (libsource (lib "altium-import") (part "root_0_100nF_"))
    )
    (comp (ref "C98")
      (value "100nF")
      (fields
        (field (name "BOM_MANUFACTURER PART") "CC0805KRX7R9BB104")
        (field (name "BOM_SUPPLIER PART") "C49678")
      )
      (libsource (lib "altium-import") (part "root_0_100nF_"))
    )
    (comp (ref "C99")
      (value "100nF")
      (fields
        (field (name "BOM_MANUFACTURER PART") "CC0805KRX7R9BB104")
        (field (name "BOM_SUPPLIER PART") "C49678")
      )
      (libsource (lib "altium-import") (part "root_0_100nF_"))
    )
    (comp (ref "C100")
      (value "100nF")
      (fields
        (field (name "BOM_MANUFACTURER PART") "CC0805KRX7R9BB104")
        (field (name "BOM_SUPPLIER PART") "C49678")
      )
      (libsource (lib "altium-import") (part "root_0_100nF_"))
    )
    (comp (ref "C101")
      (value "100nF")
      (fields
        (field (name "BOM_MANUFACTURER PART") "CC0805KRX7R9BB104")
        (field (name "BOM_SUPPLIER PART") "C49678")
      )
      (libsource (lib "altium-import") (part "root_0_100nF_"))
    )
    (comp (ref "C102")
      (value "100nF")
      (fields
        (field (name "BOM_MANUFACTURER PART") "CC0805KRX7R9BB104")
        (field (name "BOM_SUPPLIER PART") "C49678")
      )
      (libsource (lib "altium-import") (part "root_0_100nF_"))
    )
    (comp (ref "C103")
      (value "100nF")
      (fields
        (field (name "BOM_MANUFACTURER PART") "CC0805KRX7R9BB104")
        (field (name "BOM_SUPPLIER PART") "C49678")
      )
      (libsource (lib "altium-import") (part "root_0_100nF_"))
    )
    (comp (ref "C104")
      (value "100nF")
      (fields
        (field (name "BOM_MANUFACTURER PART") "CC0805KRX7R9BB104")
        (field (name "BOM_SUPPLIER PART") "C49678")
      )
      (libsource (lib "altium-import") (part "root_0_100nF_"))
    )
    (comp (ref "C105")
      (value "100nF")
      (fields
        (field (name "BOM_MANUFACTURER PART") "CC0805KRX7R9BB104")
        (field (name "BOM_SUPPLIER PART") "C49678")
      )
      (libsource (lib "altium-import") (part "root_0_100nF_"))
    )
    (comp (ref "C106")
      (value "100nF")
      (fields
        (field (name "BOM_MANUFACTURER PART") "CC0805KRX7R9BB104")
        (field (name "BOM_SUPPLIER PART") "C49678")
      )
      (libsource (lib "altium-import") (part "root_0_100nF_"))
    )
    (comp (ref "C107")
      (value "100nF")
      (fields
        (field (name "BOM_MANUFACTURER PART") "CC0805KRX7R9BB104")
        (field (name "BOM_SUPPLIER PART") "C49678")
      )
      (libsource (lib "altium-import") (part "root_0_100nF_"))
    )
    (comp (ref "C108")
      (value "100nF")
      (fields
        (field (name "BOM_MANUFACTURER PART") "CC0805KRX7R9BB104")
        (field (name "BOM_SUPPLIER PART") "C49678")
      )
      (libsource (lib "altium-import") (part "root_2_100nF_"))
    )
    (comp (ref "C109")
      (value "100nF")
      (fields
        (field (name "BOM_MANUFACTURER PART") "CC0805KRX7R9BB104")
        (field (name "BOM_SUPPLIER PART") "C49678")
      )
      (libsource (lib "altium-import") (part "root_2_100nF_"))
    )
    (comp (ref "C110")
      (value "100nF")
      (fields
        (field (name "BOM_MANUFACTURER PART") "CC0805KRX7R9BB104")
        (field (name "BOM_SUPPLIER PART") "C49678")
      )
      (libsource (lib "altium-import") (part "root_2_100nF_"))
    )
    (comp (ref "C111")
      (value "100nF")
      (fields
        (field (name "BOM_MANUFACTURER PART") "CC0805KRX7R9BB104")
        (field (name "BOM_SUPPLIER PART") "C49678")
      )
      (libsource (lib "altium-import") (part "root_2_100nF_"))
    )
    (comp (ref "C112")
      (value "100nF")
      (fields
        (field (name "BOM_MANUFACTURER PART") "CC0805KRX7R9BB104")
        (field (name "BOM_SUPPLIER PART") "C49678")
      )
      (libsource (lib "altium-import") (part "root_2_100nF_"))
    )
    (comp (ref "C113")
      (value "100nF")
      (fields
        (field (name "BOM_MANUFACTURER PART") "CC0805KRX7R9BB104")
        (field (name "BOM_SUPPLIER PART") "C49678")
      )
      (libsource (lib "altium-import") (part "root_2_100nF_"))
    )
    (comp (ref "C114")
      (value "100nF")
      (fields
        (field (name "BOM_MANUFACTURER PART") "CC0805KRX7R9BB104")
        (field (name "BOM_SUPPLIER PART") "C49678")
      )
      (libsource (lib "altium-import") (part "root_2_100nF_"))
    )
    (comp (ref "C115")
      (value "100nF")
      (fields
        (field (name "BOM_MANUFACTURER PART") "CC0805KRX7R9BB104")
        (field (name "BOM_SUPPLIER PART") "C49678")
      )
      (libsource (lib "altium-import") (part "root_2_100nF_"))
    )
    (comp (ref "C116")
      (value "100nF")
      (fields
        (field (name "BOM_MANUFACTURER PART") "CC0805KRX7R9BB104")
        (field (name "BOM_SUPPLIER PART") "C49678")
      )
      (libsource (lib "altium-import") (part "root_2_100nF_"))
    )
    (comp (ref "C117")
      (value "100nF")
      (fields
        (field (name "BOM_MANUFACTURER PART") "CC0805KRX7R9BB104")
        (field (name "BOM_SUPPLIER PART") "C49678")
      )
      (libsource (lib "altium-import") (part "root_2_100nF_"))
    )
    (comp (ref "C118")
      (value "100nF")
      (fields
        (field (name "BOM_MANUFACTURER PART") "CC0805KRX7R9BB104")
        (field (name "BOM_SUPPLIER PART") "C49678")
      )
      (libsource (lib "altium-import") (part "root_2_100nF_"))
    )
    (comp (ref "C119")
      (value "100nF")
      (fields
        (field (name "BOM_MANUFACTURER PART") "CC0805KRX7R9BB104")
        (field (name "BOM_SUPPLIER PART") "C49678")
      )
      (libsource (lib "altium-import") (part "root_2_100nF_"))
    )
    (comp (ref "C120")
      (value "100nF")
      (fields
        (field (name "BOM_MANUFACTURER PART") "CC0805KRX7R9BB104")
        (field (name "BOM_SUPPLIER PART") "C49678")
      )
      (libsource (lib "altium-import") (part "root_2_100nF_"))
    )
    (comp (ref "C121")
      (value "100nF")
      (fields
        (field (name "BOM_MANUFACTURER PART") "CC0805KRX7R9BB104")
        (field (name "BOM_SUPPLIER PART") "C49678")
      )
      (libsource (lib "altium-import") (part "root_2_100nF_"))
    )
    (comp (ref "C122")
      (value "100nF")
      (fields
        (field (name "BOM_MANUFACTURER PART") "CC0805KRX7R9BB104")
        (field (name "BOM_SUPPLIER PART") "C49678")
      )
      (libsource (lib "altium-import") (part "root_2_100nF_"))
    )
    (comp (ref "C123")
      (value "100nF")
      (fields
        (field (name "BOM_MANUFACTURER PART") "CC0805KRX7R9BB104")
        (field (name "BOM_SUPPLIER PART") "C49678")
      )
      (libsource (lib "altium-import") (part "root_2_100nF_"))
    )
    (comp (ref "C124")
      (value "100nF")
      (fields
        (field (name "BOM_MANUFACTURER PART") "CC0805KRX7R9BB104")
        (field (name "BOM_SUPPLIER PART") "C49678")
      )
      (libsource (lib "altium-import") (part "root_2_100nF_"))
    )
    (comp (ref "C125")
      (value "100nF")
      (fields
        (field (name "BOM_MANUFACTURER PART") "CC0805KRX7R9BB104")
        (field (name "BOM_SUPPLIER PART") "C49678")
      )
      (libsource (lib "altium-import") (part "root_3_100nF_"))
    )
    (comp (ref "C126")
      (value "100nF")
      (fields
        (field (name "BOM_MANUFACTURER PART") "CC0805KRX7R9BB104")
        (field (name "BOM_SUPPLIER PART") "C49678")
      )
      (libsource (lib "altium-import") (part "root_3_100nF_"))
    )
    (comp (ref "C127")
      (value "100nF")
      (fields
        (field (name "BOM_MANUFACTURER PART") "CC0805KRX7R9BB104")
        (field (name "BOM_SUPPLIER PART") "C49678")
      )
      (libsource (lib "altium-import") (part "root_3_100nF_"))
    )
    (comp (ref "C128")
      (value "100nF")
      (fields
        (field (name "BOM_MANUFACTURER PART") "CC0805KRX7R9BB104")
        (field (name "BOM_SUPPLIER PART") "C49678")
      )
      (libsource (lib "altium-import") (part "root_3_100nF_"))
    )
    (comp (ref "C129")
      (value "100nF")
      (fields
        (field (name "BOM_MANUFACTURER PART") "CC0805KRX7R9BB104")
        (field (name "BOM_SUPPLIER PART") "C49678")
      )
      (libsource (lib "altium-import") (part "root_2_100nF_"))
    )
    (comp (ref "C130")
      (value "100nF")
      (fields
        (field (name "BOM_MANUFACTURER PART") "CC0805KRX7R9BB104")
        (field (name "BOM_SUPPLIER PART") "C49678")
      )
      (libsource (lib "altium-import") (part "root_3_100nF_"))
    )
    (comp (ref "C131")
      (value "100nF")
      (fields
        (field (name "BOM_MANUFACTURER PART") "CC0805KRX7R9BB104")
        (field (name "BOM_SUPPLIER PART") "C49678")
      )
      (libsource (lib "altium-import") (part "root_3_100nF_"))
    )
    (comp (ref "C132")
      (value "100nF")
      (fields
        (field (name "BOM_MANUFACTURER PART") "CC0805KRX7R9BB104")
        (field (name "BOM_SUPPLIER PART") "C49678")
      )
      (libsource (lib "altium-import") (part "root_3_100nF_"))
    )
    (comp (ref "C133")
      (value "100nF")
      (fields
        (field (name "BOM_MANUFACTURER PART") "CC0805KRX7R9BB104")
        (field (name "BOM_SUPPLIER PART") "C49678")
      )
      (libsource (lib "altium-import") (part "root_3_100nF_"))
    )
    (comp (ref "C134")
      (value "10pF")
      (fields
        (field (name "BOM_SUPPLIER PART") "C1785")
        (field (name "BOM_MANUFACTURER PART") "CL21C100JBANNNC")
        (field (name "CONTRIBUTOR") "LCSC")
      )
      (libsource (lib "altium-import") (part "root_2_10pF_"))
    )
    (comp (ref "C135")
      (value "10pF")
      (fields
        (field (name "BOM_SUPPLIER PART") "C1785")
        (field (name "BOM_MANUFACTURER PART") "CL21C100JBANNNC")
        (field (name "CONTRIBUTOR") "LCSC")
      )
      (libsource (lib "altium-import") (part "root_2_10pF_"))
    )
    (comp (ref "C136")
      (value "100nF")
      (fields
        (field (name "BOM_MANUFACTURER PART") "CC0805KRX7R9BB104")
        (field (name "BOM_SUPPLIER PART") "C49678")
      )
      (libsource (lib "altium-import") (part "root_2_100nF_"))
    )
    (comp (ref "C137")
      (value "100nF")
      (fields
        (field (name "BOM_MANUFACTURER PART") "CC0805KRX7R9BB104")
        (field (name "BOM_SUPPLIER PART") "C49678")
      )
      (libsource (lib "altium-import") (part "root_3_100nF_"))
    )
    (comp (ref "C138")
      (value "100nF")
      (fields
        (field (name "BOM_MANUFACTURER PART") "CC0805KRX7R9BB104")
        (field (name "BOM_SUPPLIER PART") "C49678")
      )
      (libsource (lib "altium-import") (part "root_3_100nF_"))
    )
    (comp (ref "C139")
      (value "100nF")
      (fields
        (field (name "BOM_MANUFACTURER PART") "CC0805KRX7R9BB104")
        (field (name "BOM_SUPPLIER PART") "C49678")
      )
      (libsource (lib "altium-import") (part "root_1_100nF_"))
    )
    (comp (ref "D1")
      (value "CD4148WP")
      (fields (field (name "BOM_SUPPLIER PART") "C109000"))
      (libsource (lib "altium-import") (part "root_1_CD4148WP_"))
    )
    (comp (ref "ESPFLASH")
      (value "PTS810SJM250SMTRLFS")
      (fields (field (name "BOM_SUPPLIER PART") "C116501") (field (name "CONTRIBUTOR") "LCSC"))
      (libsource (lib "altium-import") (part "root_2_PTS810SJM250SMTRLFS_"))
    )
    (comp (ref "ESPRST")
      (value "PTS810SJM250SMTRLFS")
      (fields (field (name "BOM_SUPPLIER PART") "C116501") (field (name "CONTRIBUTOR") "LCSC"))
      (libsource (lib "altium-import") (part "root_2_PTS810SJM250SMTRLFS_"))
    )
    (comp (ref "H1")
      (value "Header-Male-2.54_1x3")
      (fields
        (field (name "BOM_MANUFACTURER PART") "Header2.54mm 1*3P")
        (field (name "BOM_SUPPLIER PART") "C49257")
      )
      (libsource (lib "altium-import") (part "root_3_Header-Male-2.54_1x3_"))
    )
    (comp (ref "H2")
      (value "Header-Male-2.54_1x3")
      (fields
        (field (name "BOM_MANUFACTURER PART") "Header2.54mm 1*3P")
        (field (name "BOM_SUPPLIER PART") "C49257")
      )
      (libsource (lib "altium-import") (part "root_1_Header-Male-2.54_1x3_"))
    )
    (comp (ref "H3")
      (value "Header-Male-2.54_1x3")
      (fields
        (field (name "BOM_MANUFACTURER PART") "Header2.54mm 1*3P")
        (field (name "BOM_SUPPLIER PART") "C49257")
      )
      (libsource (lib "altium-import") (part "root_1_Header-Male-2.54_1x3_"))
    )
    (comp (ref "H4")
      (value "Header-Male-2.54_1x3")
      (fields
        (field (name "BOM_MANUFACTURER PART") "Header2.54mm 1*3P")
        (field (name "BOM_SUPPLIER PART") "C49257")
      )
      (libsource (lib "altium-import") (part "root_3_Header-Male-2.54_1x3_"))
    )
    (comp (ref "H5")
      (value "Header-Male-2.54_1x3")
      (fields
        (field (name "BOM_MANUFACTURER PART") "Header2.54mm 1*3P")
        (field (name "BOM_SUPPLIER PART") "C49257")
      )
      (libsource (lib "altium-import") (part "root_1_Header-Male-2.54_1x3_"))
    )
    (comp (ref "H6")
      (value "Header-Male-2.54_1x3")
      (fields
        (field (name "BOM_MANUFACTURER PART") "Header2.54mm 1*3P")
        (field (name "BOM_SUPPLIER PART") "C49257")
      )
      (libsource (lib "altium-import") (part "root_1_Header-Male-2.54_1x3_"))
    )
    (comp (ref "H7")
      (value "Header-Male-2.54_1x3")
      (fields
        (field (name "BOM_MANUFACTURER PART") "Header2.54mm 1*3P")
        (field (name "BOM_SUPPLIER PART") "C49257")
      )
      (libsource (lib "altium-import") (part "root_3_Header-Male-2.54_1x3_"))
    )
    (comp (ref "H8")
      (value "Header-Male-2.54_1x3")
      (fields
        (field (name "BOM_MANUFACTURER PART") "Header2.54mm 1*3P")
        (field (name "BOM_SUPPLIER PART") "C49257")
      )
      (libsource (lib "altium-import") (part "root_3_Header-Male-2.54_1x3_"))
    )
    (comp (ref "H9")
      (value "Header-Male-2.54_1x3")
      (fields
        (field (name "BOM_MANUFACTURER PART") "Header2.54mm 1*3P")
        (field (name "BOM_SUPPLIER PART") "C49257")
      )
      (libsource (lib "altium-import") (part "root_1_Header-Male-2.54_1x3_"))
    )
    (comp (ref "H10")
      (value "Header-Male-2.54_1x3")
      (fields
        (field (name "BOM_MANUFACTURER PART") "Header2.54mm 1*3P")
        (field (name "BOM_SUPPLIER PART") "C49257")
      )
      (libsource (lib "altium-import") (part "root_1_Header-Male-2.54_1x3_"))
    )
    (comp (ref "H11")
      (value "Header-Male-2.54_1x3")
      (fields
        (field (name "BOM_MANUFACTURER PART") "Header2.54mm 1*3P")
        (field (name "BOM_SUPPLIER PART") "C49257")
      )
      (libsource (lib "altium-import") (part "root_3_Header-Male-2.54_1x3_"))
    )
    (comp (ref "H12")
      (value "Header-Male-2.54_1x3")
      (fields
        (field (name "BOM_MANUFACTURER PART") "Header2.54mm 1*3P")
        (field (name "BOM_SUPPLIER PART") "C49257")
      )
      (libsource (lib "altium-import") (part "root_3_Header-Male-2.54_1x3_"))
    )
    (comp (ref "H13")
      (value "Header-Male-2.54_1x3")
      (fields
        (field (name "BOM_MANUFACTURER PART") "Header2.54mm 1*3P")
        (field (name "BOM_SUPPLIER PART") "C49257")
      )
      (libsource (lib "altium-import") (part "root_1_Header-Male-2.54_1x3_"))
    )
    (comp (ref "H14")
      (value "Header-Male-2.54_1x3")
      (fields
        (field (name "BOM_MANUFACTURER PART") "Header2.54mm 1*3P")
        (field (name "BOM_SUPPLIER PART") "C49257")
      )
      (libsource (lib "altium-import") (part "root_1_Header-Male-2.54_1x3_"))
    )
    (comp (ref "H15")
      (value "Header-Male-2.54_1x3")
      (fields
        (field (name "BOM_MANUFACTURER PART") "Header2.54mm 1*3P")
        (field (name "BOM_SUPPLIER PART") "C49257")
      )
      (libsource (lib "altium-import") (part "root_3_Header-Male-2.54_1x3_"))
    )
    (comp (ref "H16")
      (value "Header-Male-2.54_1x3")
      (fields
        (field (name "BOM_MANUFACTURER PART") "Header2.54mm 1*3P")
        (field (name "BOM_SUPPLIER PART") "C49257")
      )
      (libsource (lib "altium-import") (part "root_3_Header-Male-2.54_1x3_"))
    )
    (comp (ref "H17")
      (value "Header-Male-2.54_1x3")
      (fields
        (field (name "BOM_MANUFACTURER PART") "Header2.54mm 1*3P")
        (field (name "BOM_SUPPLIER PART") "C49257")
      )
      (libsource (lib "altium-import") (part "root_1_Header-Male-2.54_1x3_"))
    )
    (comp (ref "H18")
      (value "Header-Male-2.54_1x3")
      (fields
        (field (name "BOM_MANUFACTURER PART") "Header2.54mm 1*3P")
        (field (name "BOM_SUPPLIER PART") "C49257")
      )
      (libsource (lib "altium-import") (part "root_1_Header-Male-2.54_1x3_"))
    )
    (comp (ref "H19")
      (value "Header-Male-2.54_1x3")
      (fields
        (field (name "BOM_MANUFACTURER PART") "Header2.54mm 1*3P")
        (field (name "BOM_SUPPLIER PART") "C49257")
      )
      (libsource (lib "altium-import") (part "root_3_Header-Male-2.54_1x3_"))
    )
    (comp (ref "H20")
      (value "Header-Male-2.54_1x3")
      (fields
        (field (name "BOM_MANUFACTURER PART") "Header2.54mm 1*3P")
        (field (name "BOM_SUPPLIER PART") "C49257")
      )
      (libsource (lib "altium-import") (part "root_3_Header-Male-2.54_1x3_"))
    )
    (comp (ref "H21")
      (value "PWR")
      (fields
        (field (name "BOM_MANUFACTURER PART") "Header2.54mm 1*3P")
        (field (name "BOM_SUPPLIER PART") "C49257")
      )
      (libsource (lib "altium-import") (part "root_2_PWR_"))
    )
    (comp (ref "H22")
      (value "RPI2C")
      (fields
        (field (name "BOM_MANUFACTURER PART") "Header2.54mm 1*3P")
        (field (name "BOM_SUPPLIER PART") "C49257")
      )
      (libsource (lib "altium-import") (part "root_1_RPI2C_"))
    )
    (comp (ref "JP1")
      (value "OEE")
      (fields (field (name "CONTRIBUTOR") "Celeron"))
      (libsource (lib "altium-import") (part "root_2_OEE_"))
    )
    (comp (ref "JP2")
      (value "PCF_SDA_EN")
      (fields (field (name "CONTRIBUTOR") "Celeron"))
      (libsource (lib "altium-import") (part "root_0_PCF_SDA_EN_"))
    )
    (comp (ref "JP3")
      (value "JUMPER-SMT_2")
      (fields (field (name "CONTRIBUTOR") "Celeron"))
      (libsource (lib "") (part "root_0_JUMPER-SMT_2__1"))
    )
    (comp (ref "JP4")
      (value "5VLSL")
      (fields (field (name "CONTRIBUTOR") "Celeron"))
      (libsource (lib "altium-import") (part "root_3_5VLSL_"))
    )
    (comp (ref "JP5")
      (value "USBPWR_OVR")
      (fields (field (name "CONTRIBUTOR") "Celeron"))
      (libsource (lib "altium-import") (part "root_0_USBPWR_OVR_"))
    )
    (comp (ref "JP6")
      (value "GP22WS")
      (fields (field (name "CONTRIBUTOR") "Celeron"))
      (libsource (lib "altium-import") (part "root_2_GP22WS_"))
    )
    (comp (ref "JP7")
      (value "GP16WS")
      (fields (field (name "CONTRIBUTOR") "Celeron"))
      (libsource (lib "altium-import") (part "root_2_GP16WS_"))
    )
    (comp (ref "JP8")
      (value "JUMPER-SMT_2")
      (fields (field (name "CONTRIBUTOR") "Celeron"))
      (libsource (lib "altium-import") (part "root_0_JUMPER-SMT_2_"))
    )
    (comp (ref "JP9")
      (value "PCF_SCL_EN")
      (fields (field (name "CONTRIBUTOR") "Celeron"))
      (libsource (lib "altium-import") (part "root_0_PCF_SCL_EN_"))
    )
    (comp (ref "JP10")
      (value "ESPTX")
      (fields (field (name "CONTRIBUTOR") "Celeron"))
      (libsource (lib "altium-import") (part "root_0_ESPTX_"))
    )
    (comp (ref "JP11")
      (value "ESPRX")
      (fields (field (name "CONTRIBUTOR") "Celeron"))
      (libsource (lib "altium-import") (part "root_0_ESPRX_"))
    )
    (comp (ref "JP12")
      (value "PCF_SDA_EN")
      (fields (field (name "CONTRIBUTOR") "Celeron"))
      (libsource (lib "altium-import") (part "root_0_PCF_SDA_EN_"))
    )
    (comp (ref "JP13")
      (value "PCF_SCL_EN")
      (fields (field (name "CONTRIBUTOR") "Celeron"))
      (libsource (lib "altium-import") (part "root_0_PCF_SCL_EN_"))
    )
    (comp (ref "JP14")
      (value "RP_ESP_RST")
      (fields (field (name "CONTRIBUTOR") "Celeron"))
      (libsource (lib "altium-import") (part "root_0_RP_ESP_RST_"))
    )
    (comp (ref "JP15")
      (value "RP_ESP_BOOT")
      (fields (field (name "CONTRIBUTOR") "Celeron"))
      (libsource (lib "altium-import") (part "root_0_RP_ESP_BOOT_"))
    )
    (comp (ref "JP16")
      (value "USBC_TO_RP-")
      (fields (field (name "CONTRIBUTOR") "Celeron"))
      (libsource (lib "altium-import") (part "root_0_USBC_TO_RP-_"))
    )
    (comp (ref "JP17")
      (value "USBC_TO_RP+")
      (fields (field (name "CONTRIBUTOR") "Celeron"))
      (libsource (lib "altium-import") (part "root_0_USBC_TO_RP+_"))
    )
    (comp (ref "JP18")
      (value "USBC_TO_RP-")
      (fields (field (name "CONTRIBUTOR") "Celeron"))
      (libsource (lib "altium-import") (part "root_0_USBC_TO_RP-_"))
    )
    (comp (ref "JP19")
      (value "USBC_TO_RP+")
      (fields (field (name "CONTRIBUTOR") "Celeron"))
      (libsource (lib "altium-import") (part "root_0_USBC_TO_RP+_"))
    )
    (comp (ref "LED1")
      (value "WS2812B-B")
      (fields (field (name "BOM_SUPPLIER PART") "C114586") (field (name "CONTRIBUTOR") "LCSC"))
      (libsource (lib "altium-import") (part "root_0_WS2812B-B_"))
    )
    (comp (ref "LED2")
      (value "FC-2012HRK-620D")
      (fields (field (name "BOM_SUPPLIER PART") "C84256"))
      (libsource (lib "altium-import") (part "root_0_FC-2012HRK-620D_"))
    )
    (comp (ref "LED3")
      (value "WS2812B-B")
      (fields (field (name "BOM_SUPPLIER PART") "C114586") (field (name "CONTRIBUTOR") "LCSC"))
      (libsource (lib "altium-import") (part "root_0_WS2812B-B_"))
    )
    (comp (ref "LED4")
      (value "WS2812B-B")
      (fields (field (name "BOM_SUPPLIER PART") "C114586") (field (name "CONTRIBUTOR") "LCSC"))
      (libsource (lib "altium-import") (part "root_2_WS2812B-B_"))
    )
    (comp (ref "LED5")
      (value "WS2812B-B")
      (fields (field (name "BOM_SUPPLIER PART") "C114586") (field (name "CONTRIBUTOR") "LCSC"))
      (libsource (lib "altium-import") (part "root_2_WS2812B-B_"))
    )
    (comp (ref "LED6")
      (value "WS2812B-B")
      (fields (field (name "BOM_SUPPLIER PART") "C114586") (field (name "CONTRIBUTOR") "LCSC"))
      (libsource (lib "altium-import") (part "root_2_WS2812B-B_"))
    )
    (comp (ref "LED7")
      (value "WS2812B-B")
      (fields (field (name "BOM_SUPPLIER PART") "C114586") (field (name "CONTRIBUTOR") "LCSC"))
      (libsource (lib "altium-import") (part "root_2_WS2812B-B_"))
    )
    (comp (ref "LED8")
      (value "WS2812B-B")
      (fields (field (name "BOM_SUPPLIER PART") "C114586") (field (name "CONTRIBUTOR") "LCSC"))
      (libsource (lib "altium-import") (part "root_0_WS2812B-B_"))
    )
    (comp (ref "LED9")
      (value "WS2812B-B")
      (fields (field (name "BOM_SUPPLIER PART") "C114586") (field (name "CONTRIBUTOR") "LCSC"))
      (libsource (lib "altium-import") (part "root_0_WS2812B-B_"))
    )
    (comp (ref "LED10")
      (value "WS2812B-B")
      (fields (field (name "BOM_SUPPLIER PART") "C114586") (field (name "CONTRIBUTOR") "LCSC"))
      (libsource (lib "altium-import") (part "root_0_WS2812B-B_"))
    )
    (comp (ref "LED11")
      (value "WS2812B-B")
      (fields (field (name "BOM_SUPPLIER PART") "C114586") (field (name "CONTRIBUTOR") "LCSC"))
      (libsource (lib "altium-import") (part "root_0_WS2812B-B_"))
    )
    (comp (ref "LED12")
      (value "WS2812B-B")
      (fields (field (name "BOM_SUPPLIER PART") "C114586") (field (name "CONTRIBUTOR") "LCSC"))
      (libsource (lib "altium-import") (part "root_0_WS2812B-B_"))
    )
    (comp (ref "LED13")
      (value "WS2812B-B")
      (fields (field (name "BOM_SUPPLIER PART") "C114586") (field (name "CONTRIBUTOR") "LCSC"))
      (libsource (lib "altium-import") (part "root_0_WS2812B-B_"))
    )
    (comp (ref "LED14")
      (value "WS2812B-B")
      (fields (field (name "BOM_SUPPLIER PART") "C114586") (field (name "CONTRIBUTOR") "LCSC"))
      (libsource (lib "altium-import") (part "root_0_WS2812B-B_"))
    )
    (comp (ref "LED15")
      (value "WS2812B-B")
      (fields (field (name "BOM_SUPPLIER PART") "C114586") (field (name "CONTRIBUTOR") "LCSC"))
      (libsource (lib "altium-import") (part "root_0_WS2812B-B_"))
    )
    (comp (ref "LED16")
      (value "WS2812B-B")
      (fields (field (name "BOM_SUPPLIER PART") "C114586") (field (name "CONTRIBUTOR") "LCSC"))
      (libsource (lib "altium-import") (part "root_0_WS2812B-B_"))
    )
    (comp (ref "LED17")
      (value "WS2812B-B")
      (fields (field (name "BOM_SUPPLIER PART") "C114586") (field (name "CONTRIBUTOR") "LCSC"))
      (libsource (lib "altium-import") (part "root_2_WS2812B-B_"))
    )
    (comp (ref "LED18")
      (value "WS2812B-B")
      (fields (field (name "BOM_SUPPLIER PART") "C114586") (field (name "CONTRIBUTOR") "LCSC"))
      (libsource (lib "altium-import") (part "root_2_WS2812B-B_"))
    )
    (comp (ref "LED19")
      (value "WS2812B-B")
      (fields (field (name "BOM_SUPPLIER PART") "C114586") (field (name "CONTRIBUTOR") "LCSC"))
      (libsource (lib "altium-import") (part "root_2_WS2812B-B_"))
    )
    (comp (ref "LED20")
      (value "WS2812B-B")
      (fields (field (name "BOM_SUPPLIER PART") "C114586") (field (name "CONTRIBUTOR") "LCSC"))
      (libsource (lib "altium-import") (part "root_2_WS2812B-B_"))
    )
    (comp (ref "LED21")
      (value "WS2812B-B")
      (fields (field (name "BOM_SUPPLIER PART") "C114586") (field (name "CONTRIBUTOR") "LCSC"))
      (libsource (lib "altium-import") (part "root_2_WS2812B-B_"))
    )
    (comp (ref "LED22")
      (value "WS2812B-B")
      (fields (field (name "BOM_SUPPLIER PART") "C114586") (field (name "CONTRIBUTOR") "LCSC"))
      (libsource (lib "altium-import") (part "root_2_WS2812B-B_"))
    )
    (comp (ref "LED23")
      (value "WS2812B-B")
      (fields (field (name "BOM_SUPPLIER PART") "C114586") (field (name "CONTRIBUTOR") "LCSC"))
      (libsource (lib "altium-import") (part "root_2_WS2812B-B_"))
    )
    (comp (ref "LED24")
      (value "WS2812B-B")
      (fields (field (name "BOM_SUPPLIER PART") "C114586") (field (name "CONTRIBUTOR") "LCSC"))
      (libsource (lib "altium-import") (part "root_0_WS2812B-B_"))
    )
    (comp (ref "LED25")
      (value "WS2812B-B")
      (fields (field (name "BOM_SUPPLIER PART") "C114586") (field (name "CONTRIBUTOR") "LCSC"))
      (libsource (lib "altium-import") (part "root_0_WS2812B-B_"))
    )
    (comp (ref "LED26")
      (value "WS2812B-B")
      (fields (field (name "BOM_SUPPLIER PART") "C114586") (field (name "CONTRIBUTOR") "LCSC"))
      (libsource (lib "altium-import") (part "root_0_WS2812B-B_"))
    )
    (comp (ref "LED27")
      (value "WS2812B-B")
      (fields (field (name "BOM_SUPPLIER PART") "C114586") (field (name "CONTRIBUTOR") "LCSC"))
      (libsource (lib "altium-import") (part "root_0_WS2812B-B_"))
    )
    (comp (ref "LED28")
      (value "WS2812B-B")
      (fields (field (name "BOM_SUPPLIER PART") "C114586") (field (name "CONTRIBUTOR") "LCSC"))
      (libsource (lib "altium-import") (part "root_0_WS2812B-B_"))
    )
    (comp (ref "LED29")
      (value "WS2812B-B")
      (fields (field (name "BOM_SUPPLIER PART") "C114586") (field (name "CONTRIBUTOR") "LCSC"))
      (libsource (lib "altium-import") (part "root_0_WS2812B-B_"))
    )
    (comp (ref "LED30")
      (value "WS2812B-B")
      (fields (field (name "BOM_SUPPLIER PART") "C114586") (field (name "CONTRIBUTOR") "LCSC"))
      (libsource (lib "altium-import") (part "root_0_WS2812B-B_"))
    )
    (comp (ref "LED31")
      (value "WS2812B-B")
      (fields (field (name "BOM_SUPPLIER PART") "C114586") (field (name "CONTRIBUTOR") "LCSC"))
      (libsource (lib "altium-import") (part "root_0_WS2812B-B_"))
    )
    (comp (ref "LED32")
      (value "WS2812B-B")
      (fields (field (name "BOM_SUPPLIER PART") "C114586") (field (name "CONTRIBUTOR") "LCSC"))
      (libsource (lib "altium-import") (part "root_0_WS2812B-B_"))
    )
    (comp (ref "LED33")
      (value "WS2812B-B")
      (fields (field (name "BOM_SUPPLIER PART") "C114586") (field (name "CONTRIBUTOR") "LCSC"))
      (libsource (lib "altium-import") (part "root_0_WS2812B-B_"))
    )
    (comp (ref "LED34")
      (value "WS2812B-B")
      (fields (field (name "BOM_SUPPLIER PART") "C114586") (field (name "CONTRIBUTOR") "LCSC"))
      (libsource (lib "altium-import") (part "root_0_WS2812B-B_"))
    )
    (comp (ref "LED35")
      (value "WS2812B-B")
      (fields (field (name "BOM_SUPPLIER PART") "C114586") (field (name "CONTRIBUTOR") "LCSC"))
      (libsource (lib "altium-import") (part "root_2_WS2812B-B_"))
    )
    (comp (ref "LED36")
      (value "WS2812B-B")
      (fields (field (name "BOM_SUPPLIER PART") "C114586") (field (name "CONTRIBUTOR") "LCSC"))
      (libsource (lib "altium-import") (part "root_2_WS2812B-B_"))
    )
    (comp (ref "LED37")
      (value "WS2812B-B")
      (fields (field (name "BOM_SUPPLIER PART") "C114586") (field (name "CONTRIBUTOR") "LCSC"))
      (libsource (lib "altium-import") (part "root_2_WS2812B-B_"))
    )
    (comp (ref "LED38")
      (value "WS2812B-B")
      (fields (field (name "BOM_SUPPLIER PART") "C114586") (field (name "CONTRIBUTOR") "LCSC"))
      (libsource (lib "altium-import") (part "root_2_WS2812B-B_"))
    )
    (comp (ref "LED39")
      (value "WS2812B-B")
      (fields (field (name "BOM_SUPPLIER PART") "C114586") (field (name "CONTRIBUTOR") "LCSC"))
      (libsource (lib "altium-import") (part "root_2_WS2812B-B_"))
    )
    (comp (ref "LED40")
      (value "WS2812B-B")
      (fields (field (name "BOM_SUPPLIER PART") "C114586") (field (name "CONTRIBUTOR") "LCSC"))
      (libsource (lib "altium-import") (part "root_2_WS2812B-B_"))
    )
    (comp (ref "LED41")
      (value "WS2812B-B")
      (fields (field (name "BOM_SUPPLIER PART") "C114586") (field (name "CONTRIBUTOR") "LCSC"))
      (libsource (lib "altium-import") (part "root_2_WS2812B-B_"))
    )
    (comp (ref "LED42")
      (value "WS2812B-B")
      (fields (field (name "BOM_SUPPLIER PART") "C114586") (field (name "CONTRIBUTOR") "LCSC"))
      (libsource (lib "altium-import") (part "root_2_WS2812B-B_"))
    )
    (comp (ref "LED43")
      (value "WS2812B-B")
      (fields (field (name "BOM_SUPPLIER PART") "C114586") (field (name "CONTRIBUTOR") "LCSC"))
      (libsource (lib "altium-import") (part "root_2_WS2812B-B_"))
    )
    (comp (ref "LED44")
      (value "WS2812B-B")
      (fields (field (name "BOM_SUPPLIER PART") "C114586") (field (name "CONTRIBUTOR") "LCSC"))
      (libsource (lib "altium-import") (part "root_2_WS2812B-B_"))
    )
    (comp (ref "LED45")
      (value "WS2812B-B")
      (fields (field (name "BOM_SUPPLIER PART") "C114586") (field (name "CONTRIBUTOR") "LCSC"))
      (libsource (lib "altium-import") (part "root_2_WS2812B-B_"))
    )
    (comp (ref "LED46")
      (value "WS2812B-B")
      (fields (field (name "BOM_SUPPLIER PART") "C114586") (field (name "CONTRIBUTOR") "LCSC"))
      (libsource (lib "altium-import") (part "root_0_WS2812B-B_"))
    )
    (comp (ref "LED47")
      (value "WS2812B-B")
      (fields (field (name "BOM_SUPPLIER PART") "C114586") (field (name "CONTRIBUTOR") "LCSC"))
      (libsource (lib "altium-import") (part "root_0_WS2812B-B_"))
    )
    (comp (ref "LED48")
      (value "WS2812B-B")
      (fields (field (name "BOM_SUPPLIER PART") "C114586") (field (name "CONTRIBUTOR") "LCSC"))
      (libsource (lib "altium-import") (part "root_0_WS2812B-B_"))
    )
    (comp (ref "LED49")
      (value "WS2812B-B")
      (fields (field (name "BOM_SUPPLIER PART") "C114586") (field (name "CONTRIBUTOR") "LCSC"))
      (libsource (lib "altium-import") (part "root_0_WS2812B-B_"))
    )
    (comp (ref "LED50")
      (value "WS2812B-B")
      (fields (field (name "BOM_SUPPLIER PART") "C114586") (field (name "CONTRIBUTOR") "LCSC"))
      (libsource (lib "altium-import") (part "root_0_WS2812B-B_"))
    )
    (comp (ref "LED51")
      (value "WS2812B-B")
      (fields (field (name "BOM_SUPPLIER PART") "C114586") (field (name "CONTRIBUTOR") "LCSC"))
      (libsource (lib "altium-import") (part "root_0_WS2812B-B_"))
    )
    (comp (ref "LED52")
      (value "WS2812B-B")
      (fields (field (name "BOM_SUPPLIER PART") "C114586") (field (name "CONTRIBUTOR") "LCSC"))
      (libsource (lib "altium-import") (part "root_0_WS2812B-B_"))
    )
    (comp (ref "LED53")
      (value "WS2812B-B")
      (fields (field (name "BOM_SUPPLIER PART") "C114586") (field (name "CONTRIBUTOR") "LCSC"))
      (libsource (lib "altium-import") (part "root_0_WS2812B-B_"))
    )
    (comp (ref "LED54")
      (value "WS2812B-B")
      (fields (field (name "BOM_SUPPLIER PART") "C114586") (field (name "CONTRIBUTOR") "LCSC"))
      (libsource (lib "altium-import") (part "root_0_WS2812B-B_"))
    )
    (comp (ref "LED55")
      (value "WS2812B-B")
      (fields (field (name "BOM_SUPPLIER PART") "C114586") (field (name "CONTRIBUTOR") "LCSC"))
      (libsource (lib "altium-import") (part "root_0_WS2812B-B_"))
    )
    (comp (ref "LED56")
      (value "WS2812B-B")
      (fields (field (name "BOM_SUPPLIER PART") "C114586") (field (name "CONTRIBUTOR") "LCSC"))
      (libsource (lib "altium-import") (part "root_0_WS2812B-B_"))
    )
    (comp (ref "LED57")
      (value "WS2812B-B")
      (fields (field (name "BOM_SUPPLIER PART") "C114586") (field (name "CONTRIBUTOR") "LCSC"))
      (libsource (lib "altium-import") (part "root_2_WS2812B-B_"))
    )
    (comp (ref "LED58")
      (value "WS2812B-B")
      (fields (field (name "BOM_SUPPLIER PART") "C114586") (field (name "CONTRIBUTOR") "LCSC"))
      (libsource (lib "altium-import") (part "root_2_WS2812B-B_"))
    )
    (comp (ref "LED59")
      (value "WS2812B-B")
      (fields (field (name "BOM_SUPPLIER PART") "C114586") (field (name "CONTRIBUTOR") "LCSC"))
      (libsource (lib "altium-import") (part "root_2_WS2812B-B_"))
    )
    (comp (ref "LED60")
      (value "WS2812B-B")
      (fields (field (name "BOM_SUPPLIER PART") "C114586") (field (name "CONTRIBUTOR") "LCSC"))
      (libsource (lib "altium-import") (part "root_2_WS2812B-B_"))
    )
    (comp (ref "LED61")
      (value "WS2812B-B")
      (fields (field (name "BOM_SUPPLIER PART") "C114586") (field (name "CONTRIBUTOR") "LCSC"))
      (libsource (lib "altium-import") (part "root_2_WS2812B-B_"))
    )
    (comp (ref "LED62")
      (value "WS2812B-B")
      (fields (field (name "BOM_SUPPLIER PART") "C114586") (field (name "CONTRIBUTOR") "LCSC"))
      (libsource (lib "altium-import") (part "root_2_WS2812B-B_"))
    )
    (comp (ref "LED63")
      (value "WS2812B-B")
      (fields (field (name "BOM_SUPPLIER PART") "C114586") (field (name "CONTRIBUTOR") "LCSC"))
      (libsource (lib "altium-import") (part "root_2_WS2812B-B_"))
    )
    (comp (ref "LED64")
      (value "WS2812B-B")
      (fields (field (name "BOM_SUPPLIER PART") "C114586") (field (name "CONTRIBUTOR") "LCSC"))
      (libsource (lib "altium-import") (part "root_2_WS2812B-B_"))
    )
    (comp (ref "LED65")
      (value "WS2812B-B")
      (fields (field (name "BOM_SUPPLIER PART") "C114586") (field (name "CONTRIBUTOR") "LCSC"))
      (libsource (lib "altium-import") (part "root_2_WS2812B-B_"))
    )
    (comp (ref "LED66")
      (value "WS2812B-B")
      (fields (field (name "BOM_SUPPLIER PART") "C114586") (field (name "CONTRIBUTOR") "LCSC"))
      (libsource (lib "altium-import") (part "root_2_WS2812B-B_"))
    )
    (comp (ref "LED67")
      (value "WS2812B-B")
      (fields (field (name "BOM_SUPPLIER PART") "C114586") (field (name "CONTRIBUTOR") "LCSC"))
      (libsource (lib "altium-import") (part "root_2_WS2812B-B_"))
    )
    (comp (ref "LED68")
      (value "WS2812B-B")
      (fields (field (name "BOM_SUPPLIER PART") "C114586") (field (name "CONTRIBUTOR") "LCSC"))
      (libsource (lib "altium-import") (part "root_0_WS2812B-B_"))
    )
    (comp (ref "LED69")
      (value "WS2812B-B")
      (fields (field (name "BOM_SUPPLIER PART") "C114586") (field (name "CONTRIBUTOR") "LCSC"))
      (libsource (lib "altium-import") (part "root_0_WS2812B-B_"))
    )
    (comp (ref "LED70")
      (value "WS2812B-B")
      (fields (field (name "BOM_SUPPLIER PART") "C114586") (field (name "CONTRIBUTOR") "LCSC"))
      (libsource (lib "altium-import") (part "root_0_WS2812B-B_"))
    )
    (comp (ref "LED71")
      (value "WS2812B-B")
      (fields (field (name "BOM_SUPPLIER PART") "C114586") (field (name "CONTRIBUTOR") "LCSC"))
      (libsource (lib "altium-import") (part "root_0_WS2812B-B_"))
    )
    (comp (ref "LED72")
      (value "WS2812B-B")
      (fields (field (name "BOM_SUPPLIER PART") "C114586") (field (name "CONTRIBUTOR") "LCSC"))
      (libsource (lib "altium-import") (part "root_0_WS2812B-B_"))
    )
    (comp (ref "LED73")
      (value "WS2812B-B")
      (fields (field (name "BOM_SUPPLIER PART") "C114586") (field (name "CONTRIBUTOR") "LCSC"))
      (libsource (lib "altium-import") (part "root_0_WS2812B-B_"))
    )
    (comp (ref "LED74")
      (value "WS2812B-B")
      (fields (field (name "BOM_SUPPLIER PART") "C114586") (field (name "CONTRIBUTOR") "LCSC"))
      (libsource (lib "altium-import") (part "root_0_WS2812B-B_"))
    )
    (comp (ref "LED75")
      (value "WS2812B-B")
      (fields (field (name "BOM_SUPPLIER PART") "C114586") (field (name "CONTRIBUTOR") "LCSC"))
      (libsource (lib "altium-import") (part "root_0_WS2812B-B_"))
    )
    (comp (ref "LED76")
      (value "WS2812B-B")
      (fields (field (name "BOM_SUPPLIER PART") "C114586") (field (name "CONTRIBUTOR") "LCSC"))
      (libsource (lib "altium-import") (part "root_0_WS2812B-B_"))
    )
    (comp (ref "LED77")
      (value "WS2812B-B")
      (fields (field (name "BOM_SUPPLIER PART") "C114586") (field (name "CONTRIBUTOR") "LCSC"))
      (libsource (lib "altium-import") (part "root_0_WS2812B-B_"))
    )
    (comp (ref "LED78")
      (value "WS2812B-B")
      (fields (field (name "BOM_SUPPLIER PART") "C114586") (field (name "CONTRIBUTOR") "LCSC"))
      (libsource (lib "altium-import") (part "root_0_WS2812B-B_"))
    )
    (comp (ref "LED79")
      (value "WS2812B-B")
      (fields (field (name "BOM_SUPPLIER PART") "C114586") (field (name "CONTRIBUTOR") "LCSC"))
      (libsource (lib "altium-import") (part "root_2_WS2812B-B_"))
    )
    (comp (ref "LED80")
      (value "WS2812B-B")
      (fields (field (name "BOM_SUPPLIER PART") "C114586") (field (name "CONTRIBUTOR") "LCSC"))
      (libsource (lib "altium-import") (part "root_2_WS2812B-B_"))
    )
    (comp (ref "LED81")
      (value "WS2812B-B")
      (fields (field (name "BOM_SUPPLIER PART") "C114586") (field (name "CONTRIBUTOR") "LCSC"))
      (libsource (lib "altium-import") (part "root_2_WS2812B-B_"))
    )
    (comp (ref "LED82")
      (value "WS2812B-B")
      (fields (field (name "BOM_SUPPLIER PART") "C114586") (field (name "CONTRIBUTOR") "LCSC"))
      (libsource (lib "altium-import") (part "root_2_WS2812B-B_"))
    )
    (comp (ref "LED83")
      (value "WS2812B-B")
      (fields (field (name "BOM_SUPPLIER PART") "C114586") (field (name "CONTRIBUTOR") "LCSC"))
      (libsource (lib "altium-import") (part "root_2_WS2812B-B_"))
    )
    (comp (ref "LED84")
      (value "WS2812B-B")
      (fields (field (name "BOM_SUPPLIER PART") "C114586") (field (name "CONTRIBUTOR") "LCSC"))
      (libsource (lib "altium-import") (part "root_2_WS2812B-B_"))
    )
    (comp (ref "LED85")
      (value "WS2812B-B")
      (fields (field (name "BOM_SUPPLIER PART") "C114586") (field (name "CONTRIBUTOR") "LCSC"))
      (libsource (lib "altium-import") (part "root_2_WS2812B-B_"))
    )
    (comp (ref "LED86")
      (value "WS2812B-B")
      (fields (field (name "BOM_SUPPLIER PART") "C114586") (field (name "CONTRIBUTOR") "LCSC"))
      (libsource (lib "altium-import") (part "root_2_WS2812B-B_"))
    )
    (comp (ref "LED87")
      (value "WS2812B-B")
      (fields (field (name "BOM_SUPPLIER PART") "C114586") (field (name "CONTRIBUTOR") "LCSC"))
      (libsource (lib "altium-import") (part "root_2_WS2812B-B_"))
    )
    (comp (ref "LED88")
      (value "WS2812B-B")
      (fields (field (name "BOM_SUPPLIER PART") "C114586") (field (name "CONTRIBUTOR") "LCSC"))
      (libsource (lib "altium-import") (part "root_2_WS2812B-B_"))
    )
    (comp (ref "LED89")
      (value "WS2812B-B")
      (fields (field (name "BOM_SUPPLIER PART") "C114586") (field (name "CONTRIBUTOR") "LCSC"))
      (libsource (lib "altium-import") (part "root_2_WS2812B-B_"))
    )
    (comp (ref "LED90")
      (value "WS2812B-B")
      (fields (field (name "BOM_SUPPLIER PART") "C114586") (field (name "CONTRIBUTOR") "LCSC"))
      (libsource (lib "altium-import") (part "root_0_WS2812B-B_"))
    )
    (comp (ref "LED91")
      (value "WS2812B-B")
      (fields (field (name "BOM_SUPPLIER PART") "C114586") (field (name "CONTRIBUTOR") "LCSC"))
      (libsource (lib "altium-import") (part "root_0_WS2812B-B_"))
    )
    (comp (ref "LED92")
      (value "WS2812B-B")
      (fields (field (name "BOM_SUPPLIER PART") "C114586") (field (name "CONTRIBUTOR") "LCSC"))
      (libsource (lib "altium-import") (part "root_0_WS2812B-B_"))
    )
    (comp (ref "LED93")
      (value "WS2812B-B")
      (fields (field (name "BOM_SUPPLIER PART") "C114586") (field (name "CONTRIBUTOR") "LCSC"))
      (libsource (lib "altium-import") (part "root_0_WS2812B-B_"))
    )
    (comp (ref "LED94")
      (value "WS2812B-B")
      (fields (field (name "BOM_SUPPLIER PART") "C114586") (field (name "CONTRIBUTOR") "LCSC"))
      (libsource (lib "altium-import") (part "root_0_WS2812B-B_"))
    )
    (comp (ref "LED95")
      (value "WS2812B-B")
      (fields (field (name "BOM_SUPPLIER PART") "C114586") (field (name "CONTRIBUTOR") "LCSC"))
      (libsource (lib "altium-import") (part "root_0_WS2812B-B_"))
    )
    (comp (ref "LED96")
      (value "WS2812B-B")
      (fields (field (name "BOM_SUPPLIER PART") "C114586") (field (name "CONTRIBUTOR") "LCSC"))
      (libsource (lib "altium-import") (part "root_0_WS2812B-B_"))
    )
    (comp (ref "LED97")
      (value "WS2812B-B")
      (fields (field (name "BOM_SUPPLIER PART") "C114586") (field (name "CONTRIBUTOR") "LCSC"))
      (libsource (lib "altium-import") (part "root_0_WS2812B-B_"))
    )
    (comp (ref "LED98")
      (value "WS2812B-B")
      (fields (field (name "BOM_SUPPLIER PART") "C114586") (field (name "CONTRIBUTOR") "LCSC"))
      (libsource (lib "altium-import") (part "root_0_WS2812B-B_"))
    )
    (comp (ref "LED99")
      (value "WS2812B-B")
      (fields (field (name "BOM_SUPPLIER PART") "C114586") (field (name "CONTRIBUTOR") "LCSC"))
      (libsource (lib "altium-import") (part "root_0_WS2812B-B_"))
    )
    (comp (ref "LED100")
      (value "WS2812B-B")
      (fields (field (name "BOM_SUPPLIER PART") "C114586") (field (name "CONTRIBUTOR") "LCSC"))
      (libsource (lib "altium-import") (part "root_0_WS2812B-B_"))
    )
    (comp (ref "LED101")
      (value "WS2812B-B")
      (fields (field (name "BOM_SUPPLIER PART") "C114586") (field (name "CONTRIBUTOR") "LCSC"))
      (libsource (lib "altium-import") (part "root_2_WS2812B-B_"))
    )
    (comp (ref "LED102")
      (value "WS2812B-B")
      (fields (field (name "BOM_SUPPLIER PART") "C114586") (field (name "CONTRIBUTOR") "LCSC"))
      (libsource (lib "altium-import") (part "root_2_WS2812B-B_"))
    )
    (comp (ref "LED103")
      (value "WS2812B-B")
      (fields (field (name "BOM_SUPPLIER PART") "C114586") (field (name "CONTRIBUTOR") "LCSC"))
      (libsource (lib "altium-import") (part "root_2_WS2812B-B_"))
    )
    (comp (ref "LED104")
      (value "WS2812B-B")
      (fields (field (name "BOM_SUPPLIER PART") "C114586") (field (name "CONTRIBUTOR") "LCSC"))
      (libsource (lib "altium-import") (part "root_2_WS2812B-B_"))
    )
    (comp (ref "LED105")
      (value "WS2812B-B")
      (fields (field (name "BOM_SUPPLIER PART") "C114586") (field (name "CONTRIBUTOR") "LCSC"))
      (libsource (lib "altium-import") (part "root_2_WS2812B-B_"))
    )
    (comp (ref "LED106")
      (value "WS2812B-B")
      (fields (field (name "BOM_SUPPLIER PART") "C114586") (field (name "CONTRIBUTOR") "LCSC"))
      (libsource (lib "altium-import") (part "root_2_WS2812B-B_"))
    )
    (comp (ref "LED107")
      (value "WS2812B-B")
      (fields (field (name "BOM_SUPPLIER PART") "C114586") (field (name "CONTRIBUTOR") "LCSC"))
      (libsource (lib "altium-import") (part "root_2_WS2812B-B_"))
    )
    (comp (ref "LED108")
      (value "WS2812B-B")
      (fields (field (name "BOM_SUPPLIER PART") "C114586") (field (name "CONTRIBUTOR") "LCSC"))
      (libsource (lib "altium-import") (part "root_2_WS2812B-B_"))
    )
    (comp (ref "LED109")
      (value "WS2812B-B")
      (fields (field (name "BOM_SUPPLIER PART") "C114586") (field (name "CONTRIBUTOR") "LCSC"))
      (libsource (lib "altium-import") (part "root_2_WS2812B-B_"))
    )
    (comp (ref "LED110")
      (value "WS2812B-B")
      (fields (field (name "BOM_SUPPLIER PART") "C114586") (field (name "CONTRIBUTOR") "LCSC"))
      (libsource (lib "altium-import") (part "root_2_WS2812B-B_"))
    )
    (comp (ref "LED111")
      (value "WS2812B-B")
      (fields (field (name "BOM_SUPPLIER PART") "C114586") (field (name "CONTRIBUTOR") "LCSC"))
      (libsource (lib "altium-import") (part "root_2_WS2812B-B_"))
    )
    (comp (ref "LED112")
      (value "WS2812B-B")
      (fields (field (name "BOM_SUPPLIER PART") "C114586") (field (name "CONTRIBUTOR") "LCSC"))
      (libsource (lib "altium-import") (part "root_2_WS2812B-B_"))
    )
    (comp (ref "LED113")
      (value "WS2812B-B")
      (fields (field (name "BOM_SUPPLIER PART") "C114586") (field (name "CONTRIBUTOR") "LCSC"))
      (libsource (lib "altium-import") (part "root_2_WS2812B-B_"))
    )
    (comp (ref "LED114")
      (value "WS2812B-B")
      (fields (field (name "BOM_SUPPLIER PART") "C114586") (field (name "CONTRIBUTOR") "LCSC"))
      (libsource (lib "altium-import") (part "root_2_WS2812B-B_"))
    )
    (comp (ref "LED115")
      (value "WS2812B-B")
      (fields (field (name "BOM_SUPPLIER PART") "C114586") (field (name "CONTRIBUTOR") "LCSC"))
      (libsource (lib "altium-import") (part "root_2_WS2812B-B_"))
    )
    (comp (ref "LED116")
      (value "FC-2012HRK-620D")
      (fields (field (name "BOM_SUPPLIER PART") "C84256"))
      (libsource (lib "altium-import") (part "root_2_FC-2012HRK-620D_"))
    )
    (comp (ref "P1")
      (value "RPSWD")
      (fields
        (field (name "BOM_MANUFACTURER PART") "Female header1*5P")
        (field (name "BOM_SUPPLIER PART") "C66508")
      )
      (libsource (lib "altium-import") (part "root_1_RPSWD_"))
    )
    (comp (ref "P2")
      (value "ESPPROG")
      (fields
        (field (name "BOM_MANUFACTURER PART") "Female header1*5P")
        (field (name "BOM_SUPPLIER PART") "C66508")
      )
      (libsource (lib "altium-import") (part "root_1_ESPPROG_"))
    )
    (comp (ref "P3")
      (value "Female header1*2P")
      (fields (field (name "BOM_SUPPLIER PART") "C66509"))
      (libsource (lib "altium-import") (part "root_2_Female header1*2P_"))
    )
    (comp (ref "PWRRST")
      (value "PTS810SJM250SMTRLFS")
      (fields (field (name "BOM_SUPPLIER PART") "C116501") (field (name "CONTRIBUTOR") "LCSC"))
      (libsource (lib "altium-import") (part "root_0_PTS810SJM250SMTRLFS_"))
    )
    (comp (ref "QBOOT")
      (value "PTS810SJM250SMTRLFS")
      (fields (field (name "BOM_SUPPLIER PART") "C116501") (field (name "CONTRIBUTOR") "LCSC"))
      (libsource (lib "altium-import") (part "root_0_PTS810SJM250SMTRLFS_"))
    )
    (comp (ref "QU1")
      (value "RP2040")
      (fields (field (name "BOM_SUPPLIER PART") "C2040") (field (name "CONTRIBUTOR") "LCSC"))
      (libsource (lib "altium-import") (part "root_0_RP2040_"))
    )
    (comp (ref "QU2")
      (value "W25Q128JWPIQ")
      (fields (field (name "BOM_SUPPLIER PART") "C2689660") (field (name "CONTRIBUTOR") "LCSC"))
      (libsource (lib "altium-import") (part "root_0_W25Q128JWPIQ_"))
    )
    (comp (ref "QX1")
      (value "12MHz")
      (fields
        (field (name "BOM_MANUFACTURER PART") "X322512MSB4SI")
        (field (name "BOM_SUPPLIER PART") "C9002")
        (field (name "CONTRIBUTOR") "LCSC")
      )
      (libsource (lib "altium-import") (part "root_0_12MHz_"))
    )
    (comp (ref "R1")
      (value "4.7K")
      (fields
        (field (name "BOM_SUPPLIER PART") "C17673")
        (field (name "BOM_MANUFACTURER PART") "0805W8F4701T5E")
        (field (name "CONTRIBUTOR") "LCSC")
      )
      (libsource (lib "altium-import") (part "root_3_4.7K_"))
    )
    (comp (ref "R2")
      (value "1kΩ")
      (fields
        (field (name "BOM_SUPPLIER PART") "C17513")
        (field (name "BOM_MANUFACTURER PART") "0805W8F1001T5E")
        (field (name "CONTRIBUTOR") "LCSC")
      )
      (libsource (lib "altium-import") (part "root_1_1kΩ_"))
    )
    (comp (ref "R3")
      (value "4.7K")
      (fields
        (field (name "BOM_SUPPLIER PART") "C17673")
        (field (name "BOM_MANUFACTURER PART") "0805W8F4701T5E")
        (field (name "CONTRIBUTOR") "LCSC")
      )
      (libsource (lib "altium-import") (part "root_0_4.7K_"))
    )
    (comp (ref "R4")
      (value "4.7K")
      (fields
        (field (name "BOM_SUPPLIER PART") "C17673")
        (field (name "BOM_MANUFACTURER PART") "0805W8F4701T5E")
        (field (name "CONTRIBUTOR") "LCSC")
      )
      (libsource (lib "altium-import") (part "root_0_4.7K_"))
    )
    (comp (ref "R5")
      (value "10K")
      (fields
        (field (name "BOM_MANUFACTURER PART") "0805W8F1002T5E")
        (field (name "BOM_SUPPLIER PART") "C17414")
      )
      (libsource (lib "altium-import") (part "root_1_10K_"))
    )
    (comp (ref "R6")
      (value "10K")
      (fields
        (field (name "BOM_MANUFACTURER PART") "0805W8F1002T5E")
        (field (name "BOM_SUPPLIER PART") "C17414")
      )
      (libsource (lib "altium-import") (part "root_2_10K_"))
    )
    (comp (ref "R7")
      (value "27Ω")
      (fields
        (field (name "BOM_SUPPLIER PART") "C17594")
        (field (name "BOM_MANUFACTURER PART") "0805W8F270JT5E")
        (field (name "CONTRIBUTOR") "LCSC")
      )
      (libsource (lib "altium-import") (part "root_0_27Ω_"))
    )
    (comp (ref "R8")
      (value "10K")
      (fields
        (field (name "BOM_MANUFACTURER PART") "0805W8F1002T5E")
        (field (name "BOM_SUPPLIER PART") "C17414")
      )
      (libsource (lib "altium-import") (part "root_2_10K_"))
    )
    (comp (ref "R9")
      (value "27Ω")
      (fields
        (field (name "BOM_SUPPLIER PART") "C17594")
        (field (name "BOM_MANUFACTURER PART") "0805W8F270JT5E")
        (field (name "CONTRIBUTOR") "LCSC")
      )
      (libsource (lib "altium-import") (part "root_0_27Ω_"))
    )
    (comp (ref "R10")
      (value "50")
      (fields
        (field (name "BOM_MANUFACTURER PART") "0805W8F1002T5E")
        (field (name "BOM_SUPPLIER PART") "C17414")
      )
      (libsource (lib "altium-import") (part "root_0_50_"))
    )
    (comp (ref "R11")
      (value "1K")
      (fields
        (field (name "BOM_MANUFACTURER PART") "0805W8F1001T5E")
        (field (name "BOM_SUPPLIER PART") "C17513")
      )
      (libsource (lib "altium-import") (part "root_2_1K_"))
    )
    (comp (ref "R12")
      (value "1K")
      (fields
        (field (name "BOM_MANUFACTURER PART") "0805W8F1001T5E")
        (field (name "BOM_SUPPLIER PART") "C17513")
      )
      (libsource (lib "altium-import") (part "root_2_1K_"))
    )
    (comp (ref "R13")
      (value "100Ω")
      (fields
        (field (name "BOM_SUPPLIER PART") "C17408")
        (field (name "BOM_MANUFACTURER PART") "0805W8F1000T5E")
        (field (name "CONTRIBUTOR") "LCSC")
      )
      (libsource (lib "altium-import") (part "root_0_100Ω_"))
    )
    (comp (ref "R14")
      (value "10K")
      (fields
        (field (name "BOM_MANUFACTURER PART") "0805W8F1002T5E")
        (field (name "BOM_SUPPLIER PART") "C17414")
      )
      (libsource (lib "altium-import") (part "root_2_10K_"))
    )
    (comp (ref "R15")
      (value "10K")
      (fields
        (field (name "BOM_MANUFACTURER PART") "0805W8F1002T5E")
        (field (name "BOM_SUPPLIER PART") "C17414")
      )
      (libsource (lib "altium-import") (part "root_0_10K_"))
    )
    (comp (ref "R16")
      (value "10K")
      (fields
        (field (name "BOM_MANUFACTURER PART") "0805W8F1002T5E")
        (field (name "BOM_SUPPLIER PART") "C17414")
      )
      (libsource (lib "altium-import") (part "root_0_10K_"))
    )
    (comp (ref "R17")
      (value "5.1kΩ")
      (fields
        (field (name "BOM_MANUFACTURER PART") "0805W8F5101T5E")
        (field (name "BOM_SUPPLIER PART") "C27834")
      )
      (libsource (lib "altium-import") (part "root_1_5.1kΩ_"))
    )
    (comp (ref "R18")
      (value "10K")
      (fields
        (field (name "BOM_MANUFACTURER PART") "0805W8F1002T5E")
        (field (name "BOM_SUPPLIER PART") "C17414")
      )
      (libsource (lib "altium-import") (part "root_1_10K_"))
    )
    (comp (ref "R19")
      (value "5.1kΩ")
      (fields
        (field (name "BOM_MANUFACTURER PART") "0805W8F5101T5E")
        (field (name "BOM_SUPPLIER PART") "C27834")
      )
      (libsource (lib "altium-import") (part "root_1_5.1kΩ_"))
    )
    (comp (ref "R20")
      (value "10K")
      (fields
        (field (name "BOM_MANUFACTURER PART") "0805W8F1002T5E")
        (field (name "BOM_SUPPLIER PART") "C17414")
      )
      (libsource (lib "altium-import") (part "root_1_10K_"))
    )
    (comp (ref "R21")
      (value "10K")
      (fields
        (field (name "BOM_MANUFACTURER PART") "0805W8F1002T5E")
        (field (name "BOM_SUPPLIER PART") "C17414")
      )
      (libsource (lib "altium-import") (part "root_1_10K_"))
    )
    (comp (ref "R22")
      (value "10K")
      (fields
        (field (name "BOM_MANUFACTURER PART") "0805W8F1002T5E")
        (field (name "BOM_SUPPLIER PART") "C17414")
      )
      (libsource (lib "altium-import") (part "root_1_10K_"))
    )
    (comp (ref "R23")
      (value "10K")
      (fields
        (field (name "BOM_MANUFACTURER PART") "0805W8F1002T5E")
        (field (name "BOM_SUPPLIER PART") "C17414")
      )
      (libsource (lib "altium-import") (part "root_1_10K_"))
    )
    (comp (ref "R24")
      (value "10K")
      (fields
        (field (name "BOM_MANUFACTURER PART") "0805W8F1002T5E")
        (field (name "BOM_SUPPLIER PART") "C17414")
      )
      (libsource (lib "altium-import") (part "root_2_10K_"))
    )
    (comp (ref "R25")
      (value "100Ω")
      (fields
        (field (name "BOM_SUPPLIER PART") "C17408")
        (field (name "BOM_MANUFACTURER PART") "0805W8F1000T5E")
        (field (name "CONTRIBUTOR") "LCSC")
      )
      (libsource (lib "altium-import") (part "root_2_100Ω_"))
    )
    (comp (ref "RPRST")
      (value "PTS810SJM250SMTRLFS")
      (fields (field (name "BOM_SUPPLIER PART") "C116501") (field (name "CONTRIBUTOR") "LCSC"))
      (libsource (lib "altium-import") (part "root_0_PTS810SJM250SMTRLFS_"))
    )
    (comp (ref "RPUSB")
      (value "HDR-M-2.54_1x4")
      (fields (field (name "BOM_SUPPLIER PART") "C124378") (field (name "CONTRIBUTOR") "LCEDA_Lib"))
      (libsource (lib "altium-import") (part "root_1_HDR-M-2.54_1x4_"))
    )
    (comp (ref "RPUSB1")
      (value "HDR-M-2.54_1x4")
      (fields (field (name "BOM_SUPPLIER PART") "C124378") (field (name "CONTRIBUTOR") "LCEDA_Lib"))
      (libsource (lib "altium-import") (part "root_1_HDR-M-2.54_1x4_"))
    )
    (comp (ref "U1")
      (value "BH1750FVI-TR")
      (fields (field (name "BOM_SUPPLIER PART") "C78960"))
      (libsource (lib "altium-import") (part "root_0_BH1750FVI-TR_"))
    )
    (comp (ref "U2")
      (value "AMS1117-3.3")
      (fields (field (name "BOM_SUPPLIER PART") "C6186"))
      (libsource (lib "altium-import") (part "root_0_AMS1117-3.3_"))
    )
    (comp (ref "U3")
      (value "PCF85263ATL/AX")
      (fields (field (name "BOM_SUPPLIER PART") "C2651523") (field (name "CONTRIBUTOR") "LCSC"))
      (libsource (lib "altium-import") (part "root_0_PCF85263ATL/AX_"))
    )
    (comp (ref "U4")
      (value "M24C02-WMN6TP")
      (fields (field (name "BOM_SUPPLIER PART") "C7562"))
      (libsource (lib "altium-import") (part "root_0_M24C02-WMN6TP_"))
    )
    (comp (ref "U5")
      (value "ESP-12F(ESP8266MOD)")
      (fields (field (name "BOM_SUPPLIER PART") "C82891"))
      (libsource (lib "altium-import") (part "root_0_ESP-12F(ESP8266MOD)_"))
    )
    (comp (ref "U6")
      (value "PCF8574RGTR")
      (fields (field (name "BOM_SUPPLIER PART") "C2652270") (field (name "CONTRIBUTOR") "LCSC"))
      (libsource (lib "altium-import") (part "root_0_PCF8574RGTR_"))
    )
    (comp (ref "U7")
      (value "TXB0101DCKR")
      (fields (field (name "BOM_SUPPLIER PART") "C324081") (field (name "CONTRIBUTOR") "LCSC"))
      (libsource (lib "altium-import") (part "root_0_TXB0101DCKR_"))
    )
    (comp (ref "U8")
      (value "MT8315ET")
      (fields (field (name "BOM_SUPPLIER PART") "C879584") (field (name "CONTRIBUTOR") "LCSC"))
      (libsource (lib "altium-import") (part "root_3_MT8315ET_"))
    )
    (comp (ref "U9")
      (value "MT8315ET")
      (fields (field (name "BOM_SUPPLIER PART") "C879584") (field (name "CONTRIBUTOR") "LCSC"))
      (libsource (lib "altium-import") (part "root_3_MT8315ET_"))
    )
    (comp (ref "U10")
      (value "MT8315ET")
      (fields (field (name "BOM_SUPPLIER PART") "C879584") (field (name "CONTRIBUTOR") "LCSC"))
      (libsource (lib "altium-import") (part "root_3_MT8315ET_"))
    )
    (comp (ref "U11")
      (value "MT8315ET")
      (fields (field (name "BOM_SUPPLIER PART") "C879584") (field (name "CONTRIBUTOR") "LCSC"))
      (libsource (lib "altium-import") (part "root_3_MT8315ET_"))
    )
    (comp (ref "U12")
      (value "TPD4S014DSQR")
      (fields (field (name "BOM_SUPPLIER PART") "C202244") (field (name "CONTRIBUTOR") "LCSC"))
      (libsource (lib "altium-import") (part "root_0_TPD4S014DSQR_"))
    )
    (comp (ref "USB1")
      (value "TYPE-C-31-M-26A")
      (fields (field (name "BOM_SUPPLIER PART") "C2848621") (field (name "CONTRIBUTOR") "LCSC"))
      (libsource (lib "altium-import") (part "root_0_TYPE-C-31-M-26A_"))
    )
    (comp (ref "X1")
      (value "CFV206-60.003KDZF")
      (fields (field (name "BOM_SUPPLIER PART") "C389957") (field (name "CONTRIBUTOR") "LCSC"))
      (libsource (lib "altium-import") (part "root_3_CFV206-60.003KDZF_"))
    )
  )
  (nets
    (net (code "1") (name "+1V1") (class "Default")
      (node (ref "C123") (pin "1") (pinfunction "1_1") (pintype "passive"))
      (node (ref "C124") (pin "1") (pinfunction "1_1") (pintype "passive"))
      (node (ref "QU1") (pin "23") (pinfunction "DVDD_23") (pintype "passive"))
      (node (ref "QU1") (pin "45") (pinfunction "VREG_VOUT_45") (pintype "passive"))
      (node (ref "QU1") (pin "50") (pinfunction "DVDD_50") (pintype "passive"))
    )
    (net (code "2") (name "+5V") (class "Default")
      (node (ref "C1") (pin "1") (pinfunction "1_1") (pintype "passive"))
      (node (ref "C100") (pin "1") (pinfunction "1_1") (pintype "passive"))
      (node (ref "C101") (pin "1") (pinfunction "1_1") (pintype "passive"))
      (node (ref "C102") (pin "1") (pinfunction "1_1") (pintype "passive"))
      (node (ref "C103") (pin "1") (pinfunction "1_1") (pintype "passive"))
      (node (ref "C104") (pin "1") (pinfunction "1_1") (pintype "passive"))
      (node (ref "C105") (pin "1") (pinfunction "1_1") (pintype "passive"))
      (node (ref "C106") (pin "1") (pinfunction "1_1") (pintype "passive"))
      (node (ref "C107") (pin "1") (pinfunction "1_1") (pintype "passive"))
      (node (ref "C108") (pin "1") (pinfunction "1_1") (pintype "passive"))
      (node (ref "C109") (pin "1") (pinfunction "1_1") (pintype "passive"))
      (node (ref "C11") (pin "1") (pinfunction "1_1") (pintype "passive"))
      (node (ref "C110") (pin "1") (pinfunction "1_1") (pintype "passive"))
      (node (ref "C111") (pin "1") (pinfunction "1_1") (pintype "passive"))
      (node (ref "C112") (pin "1") (pinfunction "1_1") (pintype "passive"))
      (node (ref "C113") (pin "1") (pinfunction "1_1") (pintype "passive"))
      (node (ref "C114") (pin "1") (pinfunction "1_1") (pintype "passive"))
      (node (ref "C115") (pin "1") (pinfunction "1_1") (pintype "passive"))
      (node (ref "C116") (pin "1") (pinfunction "1_1") (pintype "passive"))
      (node (ref "C117") (pin "1") (pinfunction "1_1") (pintype "passive"))
      (node (ref "C118") (pin "1") (pinfunction "1_1") (pintype "passive"))
      (node (ref "C119") (pin "1") (pinfunction "1_1") (pintype "passive"))
      (node (ref "C12") (pin "1") (pinfunction "1_1") (pintype "passive"))
      (node (ref "C120") (pin "1") (pinfunction "1_1") (pintype "passive"))
      (node (ref "C121") (pin "1") (pinfunction "1_1") (pintype "passive"))
      (node (ref "C13") (pin "1") (pinfunction "1_1") (pintype "passive"))
      (node (ref "C138") (pin "1") (pinfunction "1_1") (pintype "passive"))
      (node (ref "C14") (pin "1") (pinfunction "1_1") (pintype "passive"))
      (node (ref "C15") (pin "1") (pinfunction "1_1") (pintype "passive"))
      (node (ref "C16") (pin "1") (pinfunction "1_1") (pintype "passive"))
      (node (ref "C17") (pin "1") (pinfunction "1_1") (pintype "passive"))
      (node (ref "C18") (pin "1") (pinfunction "1_1") (pintype "passive"))
      (node (ref "C19") (pin "1") (pinfunction "1_1") (pintype "passive"))
      (node (ref "C2") (pin "2") (pinfunction "2_2") (pintype "passive"))
      (node (ref "C20") (pin "1") (pinfunction "1_1") (pintype "passive"))
      (node (ref "C21") (pin "1") (pinfunction "1_1") (pintype "passive"))
      (node (ref "C22") (pin "1") (pinfunction "1_1") (pintype "passive"))
      (node (ref "C23") (pin "1") (pinfunction "1_1") (pintype "passive"))
      (node (ref "C24") (pin "1") (pinfunction "1_1") (pintype "passive"))
      (node (ref "C25") (pin "1") (pinfunction "1_1") (pintype "passive"))
      (node (ref "C26") (pin "1") (pinfunction "1_1") (pintype "passive"))
      (node (ref "C27") (pin "1") (pinfunction "1_1") (pintype "passive"))
      (node (ref "C28") (pin "1") (pinfunction "1_1") (pintype "passive"))
      (node (ref "C29") (pin "1") (pinfunction "1_1") (pintype "passive"))
      (node (ref "C30") (pin "1") (pinfunction "1_1") (pintype "passive"))
      (node (ref "C31") (pin "1") (pinfunction "1_1") (pintype "passive"))
      (node (ref "C32") (pin "1") (pinfunction "1_1") (pintype "passive"))
      (node (ref "C33") (pin "1") (pinfunction "1_1") (pintype "passive"))
      (node (ref "C34") (pin "1") (pinfunction "1_1") (pintype "passive"))
      (node (ref "C35") (pin "1") (pinfunction "1_1") (pintype "passive"))
      (node (ref "C36") (pin "1") (pinfunction "1_1") (pintype "passive"))
      (node (ref "C37") (pin "1") (pinfunction "1_1") (pintype "passive"))
      (node (ref "C38") (pin "1") (pinfunction "1_1") (pintype "passive"))
      (node (ref "C39") (pin "1") (pinfunction "1_1") (pintype "passive"))
      (node (ref "C40") (pin "1") (pinfunction "1_1") (pintype "passive"))
      (node (ref "C41") (pin "1") (pinfunction "1_1") (pintype "passive"))
      (node (ref "C42") (pin "1") (pinfunction "1_1") (pintype "passive"))
      (node (ref "C43") (pin "1") (pinfunction "1_1") (pintype "passive"))
      (node (ref "C44") (pin "1") (pinfunction "1_1") (pintype "passive"))
      (node (ref "C45") (pin "1") (pinfunction "1_1") (pintype "passive"))
      (node (ref "C46") (pin "1") (pinfunction "1_1") (pintype "passive"))
      (node (ref "C47") (pin "1") (pinfunction "1_1") (pintype "passive"))
      (node (ref "C48") (pin "1") (pinfunction "1_1") (pintype "passive"))
      (node (ref "C49") (pin "1") (pinfunction "1_1") (pintype "passive"))
      (node (ref "C5") (pin "1") (pinfunction "1_1") (pintype "passive"))
      (node (ref "C50") (pin "1") (pinfunction "1_1") (pintype "passive"))
      (node (ref "C51") (pin "1") (pinfunction "1_1") (pintype "passive"))
      (node (ref "C52") (pin "1") (pinfunction "1_1") (pintype "passive"))
      (node (ref "C53") (pin "1") (pinfunction "1_1") (pintype "passive"))
      (node (ref "C54") (pin "1") (pinfunction "1_1") (pintype "passive"))
      (node (ref "C55") (pin "1") (pinfunction "1_1") (pintype "passive"))
      (node (ref "C56") (pin "1") (pinfunction "1_1") (pintype "passive"))
      (node (ref "C57") (pin "1") (pinfunction "1_1") (pintype "passive"))
      (node (ref "C58") (pin "1") (pinfunction "1_1") (pintype "passive"))
      (node (ref "C59") (pin "1") (pinfunction "1_1") (pintype "passive"))
      (node (ref "C60") (pin "1") (pinfunction "1_1") (pintype "passive"))
      (node (ref "C61") (pin "1") (pinfunction "1_1") (pintype "passive"))
      (node (ref "C62") (pin "1") (pinfunction "1_1") (pintype "passive"))
      (node (ref "C63") (pin "1") (pinfunction "1_1") (pintype "passive"))
      (node (ref "C64") (pin "1") (pinfunction "1_1") (pintype "passive"))
      (node (ref "C65") (pin "1") (pinfunction "1_1") (pintype "passive"))
      (node (ref "C66") (pin "1") (pinfunction "1_1") (pintype "passive"))
      (node (ref "C67") (pin "1") (pinfunction "1_1") (pintype "passive"))
      (node (ref "C68") (pin "1") (pinfunction "1_1") (pintype "passive"))
      (node (ref "C69") (pin "1") (pinfunction "1_1") (pintype "passive"))
      (node (ref "C70") (pin "1") (pinfunction "1_1") (pintype "passive"))
      (node (ref "C71") (pin "1") (pinfunction "1_1") (pintype "passive"))
      (node (ref "C72") (pin "1") (pinfunction "1_1") (pintype "passive"))
      (node (ref "C73") (pin "1") (pinfunction "1_1") (pintype "passive"))
      (node (ref "C74") (pin "1") (pinfunction "1_1") (pintype "passive"))
      (node (ref "C75") (pin "1") (pinfunction "1_1") (pintype "passive"))
      (node (ref "C76") (pin "1") (pinfunction "1_1") (pintype "passive"))
      (node (ref "C77") (pin "1") (pinfunction "1_1") (pintype "passive"))
      (node (ref "C78") (pin "1") (pinfunction "1_1") (pintype "passive"))
      (node (ref "C79") (pin "1") (pinfunction "1_1") (pintype "passive"))
      (node (ref "C8") (pin "1") (pinfunction "1_1") (pintype "passive"))
      (node (ref "C80") (pin "1") (pinfunction "1_1") (pintype "passive"))
      (node (ref "C81") (pin "1") (pinfunction "1_1") (pintype "passive"))
      (node (ref "C82") (pin "1") (pinfunction "1_1") (pintype "passive"))
      (node (ref "C83") (pin "1") (pinfunction "1_1") (pintype "passive"))
      (node (ref "C84") (pin "1") (pinfunction "1_1") (pintype "passive"))
      (node (ref "C85") (pin "1") (pinfunction "1_1") (pintype "passive"))
      (node (ref "C86") (pin "1") (pinfunction "1_1") (pintype "passive"))
      (node (ref "C87") (pin "1") (pinfunction "1_1") (pintype "passive"))
      (node (ref "C88") (pin "1") (pinfunction "1_1") (pintype "passive"))
      (node (ref "C89") (pin "1") (pinfunction "1_1") (pintype "passive"))
      (node (ref "C90") (pin "1") (pinfunction "1_1") (pintype "passive"))
      (node (ref "C91") (pin "1") (pinfunction "1_1") (pintype "passive"))
      (node (ref "C92") (pin "1") (pinfunction "1_1") (pintype "passive"))
      (node (ref "C93") (pin "1") (pinfunction "1_1") (pintype "passive"))
      (node (ref "C94") (pin "1") (pinfunction "1_1") (pintype "passive"))
      (node (ref "C95") (pin "1") (pinfunction "1_1") (pintype "passive"))
      (node (ref "C96") (pin "1") (pinfunction "1_1") (pintype "passive"))
      (node (ref "C97") (pin "1") (pinfunction "1_1") (pintype "passive"))
      (node (ref "C98") (pin "1") (pinfunction "1_1") (pintype "passive"))
      (node (ref "C99") (pin "1") (pinfunction "1_1") (pintype "passive"))
      (node (ref "D1") (pin "2") (pinfunction "A_2") (pintype "passive"))
      (node (ref "H1") (pin "1") (pinfunction "1_1") (pintype "passive"))
      (node (ref "H10") (pin "1") (pinfunction "1_1") (pintype "passive"))
      (node (ref "H11") (pin "1") (pinfunction "1_1") (pintype "passive"))
      (node (ref "H12") (pin "1") (pinfunction "1_1") (pintype "passive"))
      (node (ref "H13") (pin "1") (pinfunction "1_1") (pintype "passive"))
      (node (ref "H14") (pin "1") (pinfunction "1_1") (pintype "passive"))
      (node (ref "H15") (pin "1") (pinfunction "1_1") (pintype "passive"))
      (node (ref "H16") (pin "1") (pinfunction "1_1") (pintype "passive"))
      (node (ref "H17") (pin "1") (pinfunction "1_1") (pintype "passive"))
      (node (ref "H18") (pin "1") (pinfunction "1_1") (pintype "passive"))
      (node (ref "H19") (pin "1") (pinfunction "1_1") (pintype "passive"))
      (node (ref "H2") (pin "1") (pinfunction "1_1") (pintype "passive"))
      (node (ref "H20") (pin "1") (pinfunction "1_1") (pintype "passive"))
      (node (ref "H21") (pin "1") (pinfunction "1_1") (pintype "passive"))
      (node (ref "H3") (pin "1") (pinfunction "1_1") (pintype "passive"))
      (node (ref "H4") (pin "1") (pinfunction "1_1") (pintype "passive"))
      (node (ref "H5") (pin "1") (pinfunction "1_1") (pintype "passive"))
      (node (ref "H6") (pin "1") (pinfunction "1_1") (pintype "passive"))
      (node (ref "H7") (pin "1") (pinfunction "1_1") (pintype "passive"))
      (node (ref "H8") (pin "1") (pinfunction "1_1") (pintype "passive"))
      (node (ref "H9") (pin "1") (pinfunction "1_1") (pintype "passive"))
      (node (ref "JP4") (pin "1") (pinfunction "1_1") (pintype "passive"))
      (node (ref "JP5") (pin "1") (pinfunction "1_1") (pintype "passive"))
      (node (ref "LED1") (pin "1") (pinfunction "VDD_1") (pintype "passive"))
      (node (ref "LED10") (pin "1") (pinfunction "VDD_1") (pintype "passive"))
      (node (ref "LED100") (pin "1") (pinfunction "VDD_1") (pintype "passive"))
      (node (ref "LED101") (pin "1") (pinfunction "VDD_1") (pintype "passive"))
      (node (ref "LED102") (pin "1") (pinfunction "VDD_1") (pintype "passive"))
      (node (ref "LED103") (pin "1") (pinfunction "VDD_1") (pintype "passive"))
      (node (ref "LED104") (pin "1") (pinfunction "VDD_1") (pintype "passive"))
      (node (ref "LED105") (pin "1") (pinfunction "VDD_1") (pintype "passive"))
      (node (ref "LED106") (pin "1") (pinfunction "VDD_1") (pintype "passive"))
      (node (ref "LED107") (pin "1") (pinfunction "VDD_1") (pintype "passive"))
      (node (ref "LED108") (pin "1") (pinfunction "VDD_1") (pintype "passive"))
      (node (ref "LED109") (pin "1") (pinfunction "VDD_1") (pintype "passive"))
      (node (ref "LED11") (pin "1") (pinfunction "VDD_1") (pintype "passive"))
      (node (ref "LED110") (pin "1") (pinfunction "VDD_1") (pintype "passive"))
      (node (ref "LED111") (pin "1") (pinfunction "VDD_1") (pintype "passive"))
      (node (ref "LED112") (pin "1") (pinfunction "VDD_1") (pintype "passive"))
      (node (ref "LED113") (pin "1") (pinfunction "VDD_1") (pintype "passive"))
      (node (ref "LED114") (pin "1") (pinfunction "VDD_1") (pintype "passive"))
      (node (ref "LED12") (pin "1") (pinfunction "VDD_1") (pintype "passive"))
      (node (ref "LED13") (pin "1") (pinfunction "VDD_1") (pintype "passive"))
      (node (ref "LED14") (pin "1") (pinfunction "VDD_1") (pintype "passive"))
      (node (ref "LED15") (pin "1") (pinfunction "VDD_1") (pintype "passive"))
      (node (ref "LED16") (pin "1") (pinfunction "VDD_1") (pintype "passive"))
      (node (ref "LED17") (pin "1") (pinfunction "VDD_1") (pintype "passive"))
      (node (ref "LED18") (pin "1") (pinfunction "VDD_1") (pintype "passive"))
      (node (ref "LED19") (pin "1") (pinfunction "VDD_1") (pintype "passive"))
      (node (ref "LED20") (pin "1") (pinfunction "VDD_1") (pintype "passive"))
      (node (ref "LED21") (pin "1") (pinfunction "VDD_1") (pintype "passive"))
      (node (ref "LED22") (pin "1") (pinfunction "VDD_1") (pintype "passive"))
      (node (ref "LED23") (pin "1") (pinfunction "VDD_1") (pintype "passive"))
      (node (ref "LED24") (pin "1") (pinfunction "VDD_1") (pintype "passive"))
      (node (ref "LED25") (pin "1") (pinfunction "VDD_1") (pintype "passive"))
      (node (ref "LED26") (pin "1") (pinfunction "VDD_1") (pintype "passive"))
      (node (ref "LED27") (pin "1") (pinfunction "VDD_1") (pintype "passive"))
      (node (ref "LED28") (pin "1") (pinfunction "VDD_1") (pintype "passive"))
      (node (ref "LED29") (pin "1") (pinfunction "VDD_1") (pintype "passive"))
      (node (ref "LED3") (pin "1") (pinfunction "VDD_1") (pintype "passive"))
      (node (ref "LED30") (pin "1") (pinfunction "VDD_1") (pintype "passive"))
      (node (ref "LED31") (pin "1") (pinfunction "VDD_1") (pintype "passive"))
      (node (ref "LED32") (pin "1") (pinfunction "VDD_1") (pintype "passive"))
      (node (ref "LED33") (pin "1") (pinfunction "VDD_1") (pintype "passive"))
      (node (ref "LED34") (pin "1") (pinfunction "VDD_1") (pintype "passive"))
      (node (ref "LED35") (pin "1") (pinfunction "VDD_1") (pintype "passive"))
      (node (ref "LED36") (pin "1") (pinfunction "VDD_1") (pintype "passive"))
      (node (ref "LED37") (pin "1") (pinfunction "VDD_1") (pintype "passive"))
      (node (ref "LED38") (pin "1") (pinfunction "VDD_1") (pintype "passive"))
      (node (ref "LED39") (pin "1") (pinfunction "VDD_1") (pintype "passive"))
      (node (ref "LED4") (pin "1") (pinfunction "VDD_1") (pintype "passive"))
      (node (ref "LED40") (pin "1") (pinfunction "VDD_1") (pintype "passive"))
      (node (ref "LED41") (pin "1") (pinfunction "VDD_1") (pintype "passive"))
      (node (ref "LED42") (pin "1") (pinfunction "VDD_1") (pintype "passive"))
      (node (ref "LED43") (pin "1") (pinfunction "VDD_1") (pintype "passive"))
      (node (ref "LED44") (pin "1") (pinfunction "VDD_1") (pintype "passive"))
      (node (ref "LED45") (pin "1") (pinfunction "VDD_1") (pintype "passive"))
      (node (ref "LED46") (pin "1") (pinfunction "VDD_1") (pintype "passive"))
      (node (ref "LED47") (pin "1") (pinfunction "VDD_1") (pintype "passive"))
      (node (ref "LED48") (pin "1") (pinfunction "VDD_1") (pintype "passive"))
      (node (ref "LED49") (pin "1") (pinfunction "VDD_1") (pintype "passive"))
      (node (ref "LED5") (pin "1") (pinfunction "VDD_1") (pintype "passive"))
      (node (ref "LED50") (pin "1") (pinfunction "VDD_1") (pintype "passive"))
      (node (ref "LED51") (pin "1") (pinfunction "VDD_1") (pintype "passive"))
      (node (ref "LED52") (pin "1") (pinfunction "VDD_1") (pintype "passive"))
      (node (ref "LED53") (pin "1") (pinfunction "VDD_1") (pintype "passive"))
      (node (ref "LED54") (pin "1") (pinfunction "VDD_1") (pintype "passive"))
      (node (ref "LED55") (pin "1") (pinfunction "VDD_1") (pintype "passive"))
      (node (ref "LED56") (pin "1") (pinfunction "VDD_1") (pintype "passive"))
      (node (ref "LED57") (pin "1") (pinfunction "VDD_1") (pintype "passive"))
      (node (ref "LED58") (pin "1") (pinfunction "VDD_1") (pintype "passive"))
      (node (ref "LED59") (pin "1") (pinfunction "VDD_1") (pintype "passive"))
      (node (ref "LED6") (pin "1") (pinfunction "VDD_1") (pintype "passive"))
      (node (ref "LED60") (pin "1") (pinfunction "VDD_1") (pintype "passive"))
      (node (ref "LED61") (pin "1") (pinfunction "VDD_1") (pintype "passive"))
      (node (ref "LED62") (pin "1") (pinfunction "VDD_1") (pintype "passive"))
      (node (ref "LED63") (pin "1") (pinfunction "VDD_1") (pintype "passive"))
      (node (ref "LED64") (pin "1") (pinfunction "VDD_1") (pintype "passive"))
      (node (ref "LED65") (pin "1") (pinfunction "VDD_1") (pintype "passive"))
      (node (ref "LED66") (pin "1") (pinfunction "VDD_1") (pintype "passive"))
      (node (ref "LED67") (pin "1") (pinfunction "VDD_1") (pintype "passive"))
      (node (ref "LED68") (pin "1") (pinfunction "VDD_1") (pintype "passive"))
      (node (ref "LED69") (pin "1") (pinfunction "VDD_1") (pintype "passive"))
      (node (ref "LED7") (pin "1") (pinfunction "VDD_1") (pintype "passive"))
      (node (ref "LED70") (pin "1") (pinfunction "VDD_1") (pintype "passive"))
      (node (ref "LED71") (pin "1") (pinfunction "VDD_1") (pintype "passive"))
      (node (ref "LED72") (pin "1") (pinfunction "VDD_1") (pintype "passive"))
      (node (ref "LED73") (pin "1") (pinfunction "VDD_1") (pintype "passive"))
      (node (ref "LED74") (pin "1") (pinfunction "VDD_1") (pintype "passive"))
      (node (ref "LED75") (pin "1") (pinfunction "VDD_1") (pintype "passive"))
      (node (ref "LED76") (pin "1") (pinfunction "VDD_1") (pintype "passive"))
      (node (ref "LED77") (pin "1") (pinfunction "VDD_1") (pintype "passive"))
      (node (ref "LED78") (pin "1") (pinfunction "VDD_1") (pintype "passive"))
      (node (ref "LED79") (pin "1") (pinfunction "VDD_1") (pintype "passive"))
      (node (ref "LED8") (pin "1") (pinfunction "VDD_1") (pintype "passive"))
      (node (ref "LED80") (pin "1") (pinfunction "VDD_1") (pintype "passive"))
      (node (ref "LED81") (pin "1") (pinfunction "VDD_1") (pintype "passive"))
      (node (ref "LED82") (pin "1") (pinfunction "VDD_1") (pintype "passive"))
      (node (ref "LED83") (pin "1") (pinfunction "VDD_1") (pintype "passive"))
      (node (ref "LED84") (pin "1") (pinfunction "VDD_1") (pintype "passive"))
      (node (ref "LED85") (pin "1") (pinfunction "VDD_1") (pintype "passive"))
      (node (ref "LED86") (pin "1") (pinfunction "VDD_1") (pintype "passive"))
      (node (ref "LED87") (pin "1") (pinfunction "VDD_1") (pintype "passive"))
      (node (ref "LED88") (pin "1") (pinfunction "VDD_1") (pintype "passive"))
      (node (ref "LED89") (pin "1") (pinfunction "VDD_1") (pintype "passive"))
      (node (ref "LED9") (pin "1") (pinfunction "VDD_1") (pintype "passive"))
      (node (ref "LED90") (pin "1") (pinfunction "VDD_1") (pintype "passive"))
      (node (ref "LED91") (pin "1") (pinfunction "VDD_1") (pintype "passive"))
      (node (ref "LED92") (pin "1") (pinfunction "VDD_1") (pintype "passive"))
      (node (ref "LED93") (pin "1") (pinfunction "VDD_1") (pintype "passive"))
      (node (ref "LED94") (pin "1") (pinfunction "VDD_1") (pintype "passive"))
      (node (ref "LED95") (pin "1") (pinfunction "VDD_1") (pintype "passive"))
      (node (ref "LED96") (pin "1") (pinfunction "VDD_1") (pintype "passive"))
      (node (ref "LED97") (pin "1") (pinfunction "VDD_1") (pintype "passive"))
      (node (ref "LED98") (pin "1") (pinfunction "VDD_1") (pintype "passive"))
      (node (ref "LED99") (pin "1") (pinfunction "VDD_1") (pintype "passive"))
      (node (ref "PWRRST") (pin "2") (pinfunction "2_2") (pintype "passive"))
      (node (ref "RPUSB") (pin "1") (pinfunction "1_1") (pintype "passive"))
      (node (ref "U12") (pin "1") (pinfunction "VBUS_OUT_1") (pintype "passive"))
      (node (ref "U12") (pin "2") (pinfunction "VBUS_OUT_2") (pintype "passive"))
      (node (ref "U2") (pin "3") (pinfunction "In_3") (pintype "passive"))
      (node (ref "U7") (pin "1") (pinfunction "VCCA_1") (pintype "passive"))
    )
    (net (code "3") (name "/5VDIN") (class "Default")
      (node (ref "LED115") (pin "4") (pinfunction "DIN_4") (pintype "passive"))
      (node (ref "R10") (pin "1") (pinfunction "1_1") (pintype "passive"))
    )
    (net (code "4") (name "/ADC0") (class "Default")
      (node (ref "QU1") (pin "38") (pinfunction "GPIO26_ADC0_38") (pintype "passive"))
    )
    (net (code "5") (name "/ADC1") (class "Default")
      (node (ref "QU1") (pin "39") (pinfunction "GPIO27_ADC1_39") (pintype "passive"))
    )
    (net (code "6") (name "/ADC2") (class "Default")
      (node (ref "QU1") (pin "40") (pinfunction "GPIO28_ADC2_40") (pintype "passive"))
    )
    (net (code "7") (name "/ADC3") (class "Default")
      (node (ref "QU1") (pin "41") (pinfunction "GPIO29_ADC3_41") (pintype "passive"))
    )
    (net (code "8") (name "/GPIO 0") (class "Default")
      (node (ref "JP11") (pin "2") (pinfunction "2_2") (pintype "passive"))
      (node (ref "QU1") (pin "2") (pinfunction "GPIO0_2") (pintype "passive"))
    )
    (net (code "9") (name "/GPIO 1") (class "Default")
      (node (ref "JP10") (pin "2") (pinfunction "2_2") (pintype "passive"))
      (node (ref "QU1") (pin "3") (pinfunction "GPIO1_3") (pintype "passive"))
    )
    (net (code "10") (name "/GPIO 2") (class "Default")
      (node (ref "H22") (pin "2") (pinfunction "2_2") (pintype "passive"))
      (node (ref "JP12") (pin "2") (pinfunction "2_2") (pintype "passive"))
      (node (ref "QU1") (pin "4") (pinfunction "GPIO2_4") (pintype "passive"))
      (node (ref "R3") (pin "2") (pinfunction "2_2") (pintype "passive"))
      (node (ref "U1") (pin "4") (pinfunction "SDA_4") (pintype "passive"))
      (node (ref "U3") (pin "6") (pinfunction "SDA_6") (pintype "passive"))
      (node (ref "U4") (pin "5") (pinfunction "SDA_5") (pintype "passive"))
    )
    (net (code "11") (name "/GPIO 3") (class "Default")
      (node (ref "H22") (pin "3") (pinfunction "3_3") (pintype "passive"))
      (node (ref "JP13") (pin "2") (pinfunction "2_2") (pintype "passive"))
      (node (ref "QU1") (pin "5") (pinfunction "GPIO3_5") (pintype "passive"))
      (node (ref "R4") (pin "2") (pinfunction "2_2") (pintype "passive"))
      (node (ref "U1") (pin "6") (pinfunction "SCL_6") (pintype "passive"))
      (node (ref "U3") (pin "7") (pinfunction "SCL_7") (pintype "passive"))
      (node (ref "U4") (pin "6") (pinfunction "SCL_6") (pintype "passive"))
    )
    (net (code "12") (name "/GPIO 4") (class "Default")
      (node (ref "QU1") (pin "6") (pinfunction "GPIO4_6") (pintype "passive"))
    )
    (net (code "13") (name "/GPIO 5") (class "Default")
      (node (ref "JP14") (pin "2") (pinfunction "2_2") (pintype "passive"))
      (node (ref "QU1") (pin "7") (pinfunction "GPIO5_7") (pintype "passive"))
    )
    (net (code "14") (name "/GPIO 6") (class "Default")
      (node (ref "JP15") (pin "2") (pinfunction "2_2") (pintype "passive"))
      (node (ref "QU1") (pin "8") (pinfunction "GPIO6_8") (pintype "passive"))
    )
    (net (code "15") (name "/GPIO 7") (class "Default")
      (node (ref "QU1") (pin "9") (pinfunction "GPIO7_9") (pintype "passive"))
    )
    (net (code "16") (name "/GPIO 8") (class "Default")
      (node (ref "QU1") (pin "11") (pinfunction "GPIO8_11") (pintype "passive"))
    )
    (net (code "17") (name "/GPIO 9") (class "Default")
      (node (ref "QU1") (pin "12") (pinfunction "GPIO9_12") (pintype "passive"))
    )
    (net (code "18") (name "/GPIO 10") (class "Default")
      (node (ref "QU1") (pin "13") (pinfunction "GPIO10_13") (pintype "passive"))
    )
    (net (code "19") (name "/GPIO 11") (class "Default")
      (node (ref "QU1") (pin "14") (pinfunction "GPIO11_14") (pintype "passive"))
    )
    (net (code "20") (name "/GPIO 12") (class "Default")
      (node (ref "QU1") (pin "15") (pinfunction "GPIO12_15") (pintype "passive"))
    )
    (net (code "21") (name "/GPIO 13") (class "Default")
      (node (ref "QU1") (pin "16") (pinfunction "GPIO13_16") (pintype "passive"))
    )
    (net (code "22") (name "/GPIO 14") (class "Default")
      (node (ref "QU1") (pin "17") (pinfunction "GPIO14_17") (pintype "passive"))
    )
    (net (code "23") (name "/GPIO 15") (class "Default")
      (node (ref "QU1") (pin "18") (pinfunction "GPIO15_18") (pintype "passive"))
    )
    (net (code "24") (name "/GPIO 16") (class "Default")
      (node (ref "JP7") (pin "1") (pinfunction "1_1") (pintype "passive"))
      (node (ref "QU1") (pin "27") (pinfunction "GPIO16_27") (pintype "passive"))
    )
    (net (code "25") (name "/GPIO 17") (class "Default")
      (node (ref "QU1") (pin "28") (pinfunction "GPIO17_28") (pintype "passive"))
    )
    (net (code "26") (name "/GPIO 18") (class "Default")
      (node (ref "QU1") (pin "29") (pinfunction "GPIO18_29") (pintype "passive"))
    )
    (net (code "27") (name "/GPIO 19") (class "Default")
      (node (ref "QU1") (pin "30") (pinfunction "GPIO19_30") (pintype "passive"))
    )
    (net (code "28") (name "/GPIO 20") (class "Default")
      (node (ref "QU1") (pin "31") (pinfunction "GPIO20_31") (pintype "passive"))
    )
    (net (code "29") (name "/GPIO 21") (class "Default")
      (node (ref "QU1") (pin "32") (pinfunction "GPIO21_32") (pintype "passive"))
    )
    (net (code "30") (name "/GPIO 22") (class "Default")
      (node (ref "JP6") (pin "1") (pinfunction "1_1") (pintype "passive"))
      (node (ref "QU1") (pin "34") (pinfunction "GPIO22_34") (pintype "passive"))
    )
    (net (code "31") (name "/GPIO 23") (class "Default")
      (node (ref "QU1") (pin "35") (pinfunction "GPIO23_35") (pintype "passive"))
    )
    (net (code "32") (name "/GPIO 24") (class "Default")
      (node (ref "QU1") (pin "36") (pinfunction "GPIO24_36") (pintype "passive"))
    )
    (net (code "33") (name "/GPIO 25") (class "Default")
      (node (ref "QU1") (pin "37") (pinfunction "GPIO25_37") (pintype "passive"))
      (node (ref "R13") (pin "1") (pinfunction "1_1") (pintype "passive"))
    )
    (net (code "34") (name "/MATRIX_DIN") (class "Default")
      (node (ref "H2") (pin "2") (pinfunction "2_2") (pintype "passive"))
      (node (ref "LED115") (pin "2") (pinfunction "DOUT_2") (pintype "passive"))
      (node (ref "LED8") (pin "4") (pinfunction "DIN_4") (pintype "passive"))
    )
    (net (code "35") (name "/PCF_P4") (class "Default")
      (node (ref "R24") (pin "1") (pinfunction "1_1") (pintype "passive"))
      (node (ref "U12") (pin "4") (pinfunction "#ACK_4") (pintype "passive"))
      (node (ref "U6") (pin "10") (pinfunction "P4_10") (pintype "passive"))
    )
    (net (code "36") (name "/QSPI_CLK") (class "Default")
      (node (ref "QU1") (pin "52") (pinfunction "QSPI_SCLK_52") (pintype "passive"))
      (node (ref "QU2") (pin "6") (pinfunction "CLK_6") (pintype "passive"))
    )
    (net (code "37") (name "/QSPI_SD0") (class "Default")
      (node (ref "QU1") (pin "53") (pinfunction "QSPI_SD0_53") (pintype "passive"))
      (node (ref "QU2") (pin "5") (pinfunction "DI(IO0)_5") (pintype "passive"))
    )
    (net (code "38") (name "/QSPI_SD1") (class "Default")
      (node (ref "QU1") (pin "55") (pinfunction "QSPI_SD1_55") (pintype "passive"))
      (node (ref "QU2") (pin "2") (pinfunction "DO(IO1)_2") (pintype "passive"))
    )
    (net (code "39") (name "/QSPI_SD2") (class "Default")
      (node (ref "QU1") (pin "54") (pinfunction "QSPI_SD2_54") (pintype "passive"))
      (node (ref "QU2") (pin "3") (pinfunction "WP#(IO2)_3") (pintype "passive"))
    )
    (net (code "40") (name "/QSPI_SD3") (class "Default")
      (node (ref "QU1") (pin "51") (pinfunction "QSPI_SD3_51") (pintype "passive"))
      (node (ref "QU2") (pin "7") (pinfunction "HOLD#_or_RESET#(IO3)_7") (pintype "passive"))
    )
    (net (code "41") (name "/QSPI_SS") (class "Default")
      (node (ref "QU1") (pin "56") (pinfunction "QSPI_SS_56") (pintype "passive"))
      (node (ref "QU2") (pin "1") (pinfunction "CS#_1") (pintype "passive"))
      (node (ref "R11") (pin "1") (pinfunction "1_1") (pintype "passive"))
      (node (ref "R12") (pin "2") (pinfunction "2_2") (pintype "passive"))
    )
    (net (code "42") (name "/RUN") (class "Default")
      (node (ref "P1") (pin "2") (pinfunction "2_2") (pintype "passive"))
      (node (ref "QU1") (pin "26") (pinfunction "RUN_26") (pintype "passive"))
      (node (ref "R5") (pin "1") (pinfunction "1_1") (pintype "passive"))
      (node (ref "RPRST") (pin "2") (pinfunction "2_2") (pintype "passive"))
    )
    (net (code "43") (name "/SWCLK") (class "Default")
      (node (ref "P1") (pin "4") (pinfunction "4_4") (pintype "passive"))
      (node (ref "QU1") (pin "24") (pinfunction "SWCLK_24") (pintype "passive"))
    )
    (net (code "44") (name "/SWD") (class "Default")
      (node (ref "P1") (pin "3") (pinfunction "3_3") (pintype "passive"))
      (node (ref "QU1") (pin "25") (pinfunction "SWD_25") (pintype "passive"))
    )
    (net (code "45") (name "/USB_D+") (class "Default")
      (node (ref "JP19") (pin "2") (pinfunction "2_2") (pintype "passive"))
      (node (ref "R7") (pin "2") (pinfunction "2_2") (pintype "passive"))
      (node (ref "RPUSB") (pin "3") (pinfunction "3_3") (pintype "passive"))
    )
    (net (code "46") (name "/USB_D+C") (class "Default")
      (node (ref "JP17") (pin "1") (pinfunction "1_1") (pintype "passive"))
      (node (ref "RPUSB1") (pin "3") (pinfunction "3_3") (pintype "passive"))
      (node (ref "U12") (pin "7") (pinfunction "D+_7") (pintype "passive"))
      (node (ref "USB1") (pin "A6") (pinfunction "Dp1_A6") (pintype "passive"))
      (node (ref "USB1") (pin "B6") (pinfunction "Dp2_B6") (pintype "passive"))
    )
    (net (code "47") (name "/USB_D-") (class "Default")
      (node (ref "JP18") (pin "2") (pinfunction "2_2") (pintype "passive"))
      (node (ref "R9") (pin "2") (pinfunction "2_2") (pintype "passive"))
      (node (ref "RPUSB") (pin "2") (pinfunction "2_2") (pintype "passive"))
    )
    (net (code "48") (name "/USB_D-C") (class "Default")
      (node (ref "JP16") (pin "1") (pinfunction "1_1") (pintype "passive"))
      (node (ref "RPUSB1") (pin "2") (pinfunction "2_2") (pintype "passive"))
      (node (ref "U12") (pin "6") (pinfunction "D-_6") (pintype "passive"))
      (node (ref "USB1") (pin "A7") (pinfunction "Dn1_A7") (pintype "passive"))
      (node (ref "USB1") (pin "B7") (pinfunction "Dn2_B7") (pintype "passive"))
    )
    (net (code "49") (name "/USB_VBUS") (class "Default")
      (node (ref "C137") (pin "1") (pinfunction "1_1") (pintype "passive"))
      (node (ref "JP5") (pin "2") (pinfunction "2_2") (pintype "passive"))
      (node (ref "RPUSB1") (pin "1") (pinfunction "1_1") (pintype "passive"))
      (node (ref "U12") (pin "10") (pinfunction "VBUS_10") (pintype "passive"))
      (node (ref "U12") (pin "9") (pinfunction "VBUS_9") (pintype "passive"))
      (node (ref "USB1") (pin "A4") (pinfunction "VBUS_A4") (pintype "passive"))
      (node (ref "USB1") (pin "B9") (pinfunction "VBUS_B9") (pintype "passive"))
    )
    (net (code "50") (name "/XIN") (class "Default")
      (node (ref "C134") (pin "1") (pinfunction "1_1") (pintype "passive"))
      (node (ref "QU1") (pin "20") (pinfunction "XIN_20") (pintype "passive"))
      (node (ref "QX1") (pin "1") (pinfunction "OSC1_1") (pintype "passive"))
    )
    (net (code "51") (name "/XOUT") (class "Default")
      (node (ref "C135") (pin "2") (pinfunction "2_2") (pintype "passive"))
      (node (ref "QU1") (pin "21") (pinfunction "XOUT_21") (pintype "passive"))
      (node (ref "QX1") (pin "3") (pinfunction "OSC2_3") (pintype "passive"))
    )
    (net (code "52") (name "GND") (class "Default")
      (node (ref "BT1") (pin "2") (pinfunction "2_2") (pintype "passive"))
      (node (ref "BT2") (pin "2") (pinfunction "2_2") (pintype "passive"))
      (node (ref "C1") (pin "2") (pinfunction "2_2") (pintype "passive"))
      (node (ref "C10") (pin "1") (pinfunction "1_1") (pintype "passive"))
      (node (ref "C100") (pin "2") (pinfunction "2_2") (pintype "passive"))
      (node (ref "C101") (pin "2") (pinfunction "2_2") (pintype "passive"))
      (node (ref "C102") (pin "2") (pinfunction "2_2") (pintype "passive"))
      (node (ref "C103") (pin "2") (pinfunction "2_2") (pintype "passive"))
      (node (ref "C104") (pin "2") (pinfunction "2_2") (pintype "passive"))
      (node (ref "C105") (pin "2") (pinfunction "2_2") (pintype "passive"))
      (node (ref "C106") (pin "2") (pinfunction "2_2") (pintype "passive"))
      (node (ref "C107") (pin "2") (pinfunction "2_2") (pintype "passive"))
      (node (ref "C108") (pin "2") (pinfunction "2_2") (pintype "passive"))
      (node (ref "C109") (pin "2") (pinfunction "2_2") (pintype "passive"))
      (node (ref "C11") (pin "2") (pinfunction "2_2") (pintype "passive"))
      (node (ref "C110") (pin "2") (pinfunction "2_2") (pintype "passive"))
      (node (ref "C111") (pin "2") (pinfunction "2_2") (pintype "passive"))
      (node (ref "C112") (pin "2") (pinfunction "2_2") (pintype "passive"))
      (node (ref "C113") (pin "2") (pinfunction "2_2") (pintype "passive"))
      (node (ref "C114") (pin "2") (pinfunction "2_2") (pintype "passive"))
      (node (ref "C115") (pin "2") (pinfunction "2_2") (pintype "passive"))
      (node (ref "C116") (pin "2") (pinfunction "2_2") (pintype "passive"))
      (node (ref "C117") (pin "2") (pinfunction "2_2") (pintype "passive"))
      (node (ref "C118") (pin "2") (pinfunction "2_2") (pintype "passive"))
      (node (ref "C119") (pin "2") (pinfunction "2_2") (pintype "passive"))
      (node (ref "C12") (pin "2") (pinfunction "2_2") (pintype "passive"))
      (node (ref "C120") (pin "2") (pinfunction "2_2") (pintype "passive"))
      (node (ref "C121") (pin "2") (pinfunction "2_2") (pintype "passive"))
      (node (ref "C122") (pin "2") (pinfunction "2_2") (pintype "passive"))
      (node (ref "C123") (pin "2") (pinfunction "2_2") (pintype "passive"))
      (node (ref "C124") (pin "2") (pinfunction "2_2") (pintype "passive"))
      (node (ref "C125") (pin "1") (pinfunction "1_1") (pintype "passive"))
      (node (ref "C126") (pin "1") (pinfunction "1_1") (pintype "passive"))
      (node (ref "C127") (pin "1") (pinfunction "1_1") (pintype "passive"))
      (node (ref "C128") (pin "1") (pinfunction "1_1") (pintype "passive"))
      (node (ref "C129") (pin "2") (pinfunction "2_2") (pintype "passive"))
      (node (ref "C13") (pin "2") (pinfunction "2_2") (pintype "passive"))
      (node (ref "C130") (pin "2") (pinfunction "2_2") (pintype "passive"))
      (node (ref "C131") (pin "1") (pinfunction "1_1") (pintype "passive"))
      (node (ref "C132") (pin "1") (pinfunction "1_1") (pintype "passive"))
      (node (ref "C133") (pin "1") (pinfunction "1_1") (pintype "passive"))
      (node (ref "C134") (pin "2") (pinfunction "2_2") (pintype "passive"))
      (node (ref "C135") (pin "1") (pinfunction "1_1") (pintype "passive"))
      (node (ref "C136") (pin "2") (pinfunction "2_2") (pintype "passive"))
      (node (ref "C137") (pin "2") (pinfunction "2_2") (pintype "passive"))
      (node (ref "C138") (pin "2") (pinfunction "2_2") (pintype "passive"))
      (node (ref "C139") (pin "1") (pinfunction "1_1") (pintype "passive"))
      (node (ref "C14") (pin "2") (pinfunction "2_2") (pintype "passive"))
      (node (ref "C15") (pin "2") (pinfunction "2_2") (pintype "passive"))
      (node (ref "C16") (pin "2") (pinfunction "2_2") (pintype "passive"))
      (node (ref "C17") (pin "2") (pinfunction "2_2") (pintype "passive"))
      (node (ref "C18") (pin "2") (pinfunction "2_2") (pintype "passive"))
      (node (ref "C19") (pin "2") (pinfunction "2_2") (pintype "passive"))
      (node (ref "C2") (pin "1") (pinfunction "1_1") (pintype "passive"))
      (node (ref "C20") (pin "2") (pinfunction "2_2") (pintype "passive"))
      (node (ref "C21") (pin "2") (pinfunction "2_2") (pintype "passive"))
      (node (ref "C22") (pin "2") (pinfunction "2_2") (pintype "passive"))
      (node (ref "C23") (pin "2") (pinfunction "2_2") (pintype "passive"))
      (node (ref "C24") (pin "2") (pinfunction "2_2") (pintype "passive"))
      (node (ref "C25") (pin "2") (pinfunction "2_2") (pintype "passive"))
      (node (ref "C26") (pin "2") (pinfunction "2_2") (pintype "passive"))
      (node (ref "C27") (pin "2") (pinfunction "2_2") (pintype "passive"))
      (node (ref "C28") (pin "2") (pinfunction "2_2") (pintype "passive"))
      (node (ref "C29") (pin "2") (pinfunction "2_2") (pintype "passive"))
      (node (ref "C3") (pin "2") (pinfunction "2_2") (pintype "passive"))
      (node (ref "C30") (pin "2") (pinfunction "2_2") (pintype "passive"))
      (node (ref "C31") (pin "2") (pinfunction "2_2") (pintype "passive"))
      (node (ref "C32") (pin "2") (pinfunction "2_2") (pintype "passive"))
      (node (ref "C33") (pin "2") (pinfunction "2_2") (pintype "passive"))
      (node (ref "C34") (pin "2") (pinfunction "2_2") (pintype "passive"))
      (node (ref "C35") (pin "2") (pinfunction "2_2") (pintype "passive"))
      (node (ref "C36") (pin "2") (pinfunction "2_2") (pintype "passive"))
      (node (ref "C37") (pin "2") (pinfunction "2_2") (pintype "passive"))
      (node (ref "C38") (pin "2") (pinfunction "2_2") (pintype "passive"))
      (node (ref "C39") (pin "2") (pinfunction "2_2") (pintype "passive"))
      (node (ref "C4") (pin "2") (pinfunction "2_2") (pintype "passive"))
      (node (ref "C40") (pin "2") (pinfunction "2_2") (pintype "passive"))
      (node (ref "C41") (pin "2") (pinfunction "2_2") (pintype "passive"))
      (node (ref "C42") (pin "2") (pinfunction "2_2") (pintype "passive"))
      (node (ref "C43") (pin "2") (pinfunction "2_2") (pintype "passive"))
      (node (ref "C44") (pin "2") (pinfunction "2_2") (pintype "passive"))
      (node (ref "C45") (pin "2") (pinfunction "2_2") (pintype "passive"))
      (node (ref "C46") (pin "2") (pinfunction "2_2") (pintype "passive"))
      (node (ref "C47") (pin "2") (pinfunction "2_2") (pintype "passive"))
      (node (ref "C48") (pin "2") (pinfunction "2_2") (pintype "passive"))
      (node (ref "C49") (pin "2") (pinfunction "2_2") (pintype "passive"))
      (node (ref "C5") (pin "2") (pinfunction "2_2") (pintype "passive"))
      (node (ref "C50") (pin "2") (pinfunction "2_2") (pintype "passive"))
      (node (ref "C51") (pin "2") (pinfunction "2_2") (pintype "passive"))
      (node (ref "C52") (pin "2") (pinfunction "2_2") (pintype "passive"))
      (node (ref "C53") (pin "2") (pinfunction "2_2") (pintype "passive"))
      (node (ref "C54") (pin "2") (pinfunction "2_2") (pintype "passive"))
      (node (ref "C55") (pin "2") (pinfunction "2_2") (pintype "passive"))
      (node (ref "C56") (pin "2") (pinfunction "2_2") (pintype "passive"))
      (node (ref "C57") (pin "2") (pinfunction "2_2") (pintype "passive"))
      (node (ref "C58") (pin "2") (pinfunction "2_2") (pintype "passive"))
      (node (ref "C59") (pin "2") (pinfunction "2_2") (pintype "passive"))
      (node (ref "C6") (pin "1") (pinfunction "1_1") (pintype "passive"))
      (node (ref "C60") (pin "2") (pinfunction "2_2") (pintype "passive"))
      (node (ref "C61") (pin "2") (pinfunction "2_2") (pintype "passive"))
      (node (ref "C62") (pin "2") (pinfunction "2_2") (pintype "passive"))
      (node (ref "C63") (pin "2") (pinfunction "2_2") (pintype "passive"))
      (node (ref "C64") (pin "2") (pinfunction "2_2") (pintype "passive"))
      (node (ref "C65") (pin "2") (pinfunction "2_2") (pintype "passive"))
      (node (ref "C66") (pin "2") (pinfunction "2_2") (pintype "passive"))
      (node (ref "C67") (pin "2") (pinfunction "2_2") (pintype "passive"))
      (node (ref "C68") (pin "2") (pinfunction "2_2") (pintype "passive"))
      (node (ref "C69") (pin "2") (pinfunction "2_2") (pintype "passive"))
      (node (ref "C7") (pin "2") (pinfunction "2_2") (pintype "passive"))
      (node (ref "C70") (pin "2") (pinfunction "2_2") (pintype "passive"))
      (node (ref "C71") (pin "2") (pinfunction "2_2") (pintype "passive"))
      (node (ref "C72") (pin "2") (pinfunction "2_2") (pintype "passive"))
      (node (ref "C73") (pin "2") (pinfunction "2_2") (pintype "passive"))
      (node (ref "C74") (pin "2") (pinfunction "2_2") (pintype "passive"))
      (node (ref "C75") (pin "2") (pinfunction "2_2") (pintype "passive"))
      (node (ref "C76") (pin "2") (pinfunction "2_2") (pintype "passive"))
      (node (ref "C77") (pin "2") (pinfunction "2_2") (pintype "passive"))
      (node (ref "C78") (pin "2") (pinfunction "2_2") (pintype "passive"))
      (node (ref "C79") (pin "2") (pinfunction "2_2") (pintype "passive"))
      (node (ref "C8") (pin "2") (pinfunction "2_2") (pintype "passive"))
      (node (ref "C80") (pin "2") (pinfunction "2_2") (pintype "passive"))
      (node (ref "C81") (pin "2") (pinfunction "2_2") (pintype "passive"))
      (node (ref "C82") (pin "2") (pinfunction "2_2") (pintype "passive"))
      (node (ref "C83") (pin "2") (pinfunction "2_2") (pintype "passive"))
      (node (ref "C84") (pin "2") (pinfunction "2_2") (pintype "passive"))
      (node (ref "C85") (pin "2") (pinfunction "2_2") (pintype "passive"))
      (node (ref "C86") (pin "2") (pinfunction "2_2") (pintype "passive"))
      (node (ref "C87") (pin "2") (pinfunction "2_2") (pintype "passive"))
      (node (ref "C88") (pin "2") (pinfunction "2_2") (pintype "passive"))
      (node (ref "C89") (pin "2") (pinfunction "2_2") (pintype "passive"))
      (node (ref "C9") (pin "2") (pinfunction "2_2") (pintype "passive"))
      (node (ref "C90") (pin "2") (pinfunction "2_2") (pintype "passive"))
      (node (ref "C91") (pin "2") (pinfunction "2_2") (pintype "passive"))
      (node (ref "C92") (pin "2") (pinfunction "2_2") (pintype "passive"))
      (node (ref "C93") (pin "2") (pinfunction "2_2") (pintype "passive"))
      (node (ref "C94") (pin "2") (pinfunction "2_2") (pintype "passive"))
      (node (ref "C95") (pin "2") (pinfunction "2_2") (pintype "passive"))
      (node (ref "C96") (pin "2") (pinfunction "2_2") (pintype "passive"))
      (node (ref "C97") (pin "2") (pinfunction "2_2") (pintype "passive"))
      (node (ref "C98") (pin "2") (pinfunction "2_2") (pintype "passive"))
      (node (ref "C99") (pin "2") (pinfunction "2_2") (pintype "passive"))
      (node (ref "ESPRST") (pin "2") (pinfunction "2_2") (pintype "passive"))
      (node (ref "H1") (pin "3") (pinfunction "3_3") (pintype "passive"))
      (node (ref "H10") (pin "3") (pinfunction "3_3") (pintype "passive"))
      (node (ref "H11") (pin "3") (pinfunction "3_3") (pintype "passive"))
      (node (ref "H12") (pin "3") (pinfunction "3_3") (pintype "passive"))
      (node (ref "H13") (pin "3") (pinfunction "3_3") (pintype "passive"))
      (node (ref "H14") (pin "3") (pinfunction "3_3") (pintype "passive"))
      (node (ref "H15") (pin "3") (pinfunction "3_3") (pintype "passive"))
      (node (ref "H16") (pin "3") (pinfunction "3_3") (pintype "passive"))
      (node (ref "H17") (pin "3") (pinfunction "3_3") (pintype "passive"))
      (node (ref "H18") (pin "3") (pinfunction "3_3") (pintype "passive"))
      (node (ref "H19") (pin "3") (pinfunction "3_3") (pintype "passive"))
      (node (ref "H2") (pin "3") (pinfunction "3_3") (pintype "passive"))
      (node (ref "H20") (pin "3") (pinfunction "3_3") (pintype "passive"))
      (node (ref "H21") (pin "3") (pinfunction "3_3") (pintype "passive"))
      (node (ref "H22") (pin "1") (pinfunction "1_1") (pintype "passive"))
      (node (ref "H3") (pin "3") (pinfunction "3_3") (pintype "passive"))
      (node (ref "H4") (pin "3") (pinfunction "3_3") (pintype "passive"))
      (node (ref "H5") (pin "3") (pinfunction "3_3") (pintype "passive"))
      (node (ref "H6") (pin "3") (pinfunction "3_3") (pintype "passive"))
      (node (ref "H7") (pin "3") (pinfunction "3_3") (pintype "passive"))
      (node (ref "H8") (pin "3") (pinfunction "3_3") (pintype "passive"))
      (node (ref "H9") (pin "3") (pinfunction "3_3") (pintype "passive"))
      (node (ref "LED1") (pin "3") (pinfunction "VSS_3") (pintype "passive"))
      (node (ref "LED10") (pin "3") (pinfunction "VSS_3") (pintype "passive"))
      (node (ref "LED100") (pin "3") (pinfunction "VSS_3") (pintype "passive"))
      (node (ref "LED101") (pin "3") (pinfunction "VSS_3") (pintype "passive"))
      (node (ref "LED102") (pin "3") (pinfunction "VSS_3") (pintype "passive"))
      (node (ref "LED103") (pin "3") (pinfunction "VSS_3") (pintype "passive"))
      (node (ref "LED104") (pin "3") (pinfunction "VSS_3") (pintype "passive"))
      (node (ref "LED105") (pin "3") (pinfunction "VSS_3") (pintype "passive"))
      (node (ref "LED106") (pin "3") (pinfunction "VSS_3") (pintype "passive"))
      (node (ref "LED107") (pin "3") (pinfunction "VSS_3") (pintype "passive"))
      (node (ref "LED108") (pin "3") (pinfunction "VSS_3") (pintype "passive"))
      (node (ref "LED109") (pin "3") (pinfunction "VSS_3") (pintype "passive"))
      (node (ref "LED11") (pin "3") (pinfunction "VSS_3") (pintype "passive"))
      (node (ref "LED110") (pin "3") (pinfunction "VSS_3") (pintype "passive"))
      (node (ref "LED111") (pin "3") (pinfunction "VSS_3") (pintype "passive"))
      (node (ref "LED112") (pin "3") (pinfunction "VSS_3") (pintype "passive"))
      (node (ref "LED113") (pin "3") (pinfunction "VSS_3") (pintype "passive"))
      (node (ref "LED114") (pin "3") (pinfunction "VSS_3") (pintype "passive"))
      (node (ref "LED115") (pin "3") (pinfunction "VSS_3") (pintype "passive"))
      (node (ref "LED116") (pin "1") (pinfunction "-_1") (pintype "passive"))
      (node (ref "LED12") (pin "3") (pinfunction "VSS_3") (pintype "passive"))
      (node (ref "LED13") (pin "3") (pinfunction "VSS_3") (pintype "passive"))
      (node (ref "LED14") (pin "3") (pinfunction "VSS_3") (pintype "passive"))
      (node (ref "LED15") (pin "3") (pinfunction "VSS_3") (pintype "passive"))
      (node (ref "LED16") (pin "3") (pinfunction "VSS_3") (pintype "passive"))
      (node (ref "LED17") (pin "3") (pinfunction "VSS_3") (pintype "passive"))
      (node (ref "LED18") (pin "3") (pinfunction "VSS_3") (pintype "passive"))
      (node (ref "LED19") (pin "3") (pinfunction "VSS_3") (pintype "passive"))
      (node (ref "LED20") (pin "3") (pinfunction "VSS_3") (pintype "passive"))
      (node (ref "LED21") (pin "3") (pinfunction "VSS_3") (pintype "passive"))
      (node (ref "LED22") (pin "3") (pinfunction "VSS_3") (pintype "passive"))
      (node (ref "LED23") (pin "3") (pinfunction "VSS_3") (pintype "passive"))
      (node (ref "LED24") (pin "3") (pinfunction "VSS_3") (pintype "passive"))
      (node (ref "LED25") (pin "3") (pinfunction "VSS_3") (pintype "passive"))
      (node (ref "LED26") (pin "3") (pinfunction "VSS_3") (pintype "passive"))
      (node (ref "LED27") (pin "3") (pinfunction "VSS_3") (pintype "passive"))
      (node (ref "LED28") (pin "3") (pinfunction "VSS_3") (pintype "passive"))
      (node (ref "LED29") (pin "3") (pinfunction "VSS_3") (pintype "passive"))
      (node (ref "LED3") (pin "3") (pinfunction "VSS_3") (pintype "passive"))
      (node (ref "LED30") (pin "3") (pinfunction "VSS_3") (pintype "passive"))
      (node (ref "LED31") (pin "3") (pinfunction "VSS_3") (pintype "passive"))
      (node (ref "LED32") (pin "3") (pinfunction "VSS_3") (pintype "passive"))
      (node (ref "LED33") (pin "3") (pinfunction "VSS_3") (pintype "passive"))
      (node (ref "LED34") (pin "3") (pinfunction "VSS_3") (pintype "passive"))
      (node (ref "LED35") (pin "3") (pinfunction "VSS_3") (pintype "passive"))
      (node (ref "LED36") (pin "3") (pinfunction "VSS_3") (pintype "passive"))
      (node (ref "LED37") (pin "3") (pinfunction "VSS_3") (pintype "passive"))
      (node (ref "LED38") (pin "3") (pinfunction "VSS_3") (pintype "passive"))
      (node (ref "LED39") (pin "3") (pinfunction "VSS_3") (pintype "passive"))
      (node (ref "LED4") (pin "3") (pinfunction "VSS_3") (pintype "passive"))
      (node (ref "LED40") (pin "3") (pinfunction "VSS_3") (pintype "passive"))
      (node (ref "LED41") (pin "3") (pinfunction "VSS_3") (pintype "passive"))
      (node (ref "LED42") (pin "3") (pinfunction "VSS_3") (pintype "passive"))
      (node (ref "LED43") (pin "3") (pinfunction "VSS_3") (pintype "passive"))
      (node (ref "LED44") (pin "3") (pinfunction "VSS_3") (pintype "passive"))
      (node (ref "LED45") (pin "3") (pinfunction "VSS_3") (pintype "passive"))
      (node (ref "LED46") (pin "3") (pinfunction "VSS_3") (pintype "passive"))
      (node (ref "LED47") (pin "3") (pinfunction "VSS_3") (pintype "passive"))
      (node (ref "LED48") (pin "3") (pinfunction "VSS_3") (pintype "passive"))
      (node (ref "LED49") (pin "3") (pinfunction "VSS_3") (pintype "passive"))
      (node (ref "LED5") (pin "3") (pinfunction "VSS_3") (pintype "passive"))
      (node (ref "LED50") (pin "3") (pinfunction "VSS_3") (pintype "passive"))
      (node (ref "LED51") (pin "3") (pinfunction "VSS_3") (pintype "passive"))
      (node (ref "LED52") (pin "3") (pinfunction "VSS_3") (pintype "passive"))
      (node (ref "LED53") (pin "3") (pinfunction "VSS_3") (pintype "passive"))
      (node (ref "LED54") (pin "3") (pinfunction "VSS_3") (pintype "passive"))
      (node (ref "LED55") (pin "3") (pinfunction "VSS_3") (pintype "passive"))
      (node (ref "LED56") (pin "3") (pinfunction "VSS_3") (pintype "passive"))
      (node (ref "LED57") (pin "3") (pinfunction "VSS_3") (pintype "passive"))
      (node (ref "LED58") (pin "3") (pinfunction "VSS_3") (pintype "passive"))
      (node (ref "LED59") (pin "3") (pinfunction "VSS_3") (pintype "passive"))
      (node (ref "LED6") (pin "3") (pinfunction "VSS_3") (pintype "passive"))
      (node (ref "LED60") (pin "3") (pinfunction "VSS_3") (pintype "passive"))
      (node (ref "LED61") (pin "3") (pinfunction "VSS_3") (pintype "passive"))
      (node (ref "LED62") (pin "3") (pinfunction "VSS_3") (pintype "passive"))
      (node (ref "LED63") (pin "3") (pinfunction "VSS_3") (pintype "passive"))
      (node (ref "LED64") (pin "3") (pinfunction "VSS_3") (pintype "passive"))
      (node (ref "LED65") (pin "3") (pinfunction "VSS_3") (pintype "passive"))
      (node (ref "LED66") (pin "3") (pinfunction "VSS_3") (pintype "passive"))
      (node (ref "LED67") (pin "3") (pinfunction "VSS_3") (pintype "passive"))
      (node (ref "LED68") (pin "3") (pinfunction "VSS_3") (pintype "passive"))
      (node (ref "LED69") (pin "3") (pinfunction "VSS_3") (pintype "passive"))
      (node (ref "LED7") (pin "3") (pinfunction "VSS_3") (pintype "passive"))
      (node (ref "LED70") (pin "3") (pinfunction "VSS_3") (pintype "passive"))
      (node (ref "LED71") (pin "3") (pinfunction "VSS_3") (pintype "passive"))
      (node (ref "LED72") (pin "3") (pinfunction "VSS_3") (pintype "passive"))
      (node (ref "LED73") (pin "3") (pinfunction "VSS_3") (pintype "passive"))
      (node (ref "LED74") (pin "3") (pinfunction "VSS_3") (pintype "passive"))
      (node (ref "LED75") (pin "3") (pinfunction "VSS_3") (pintype "passive"))
      (node (ref "LED76") (pin "3") (pinfunction "VSS_3") (pintype "passive"))
      (node (ref "LED77") (pin "3") (pinfunction "VSS_3") (pintype "passive"))
      (node (ref "LED78") (pin "3") (pinfunction "VSS_3") (pintype "passive"))
      (node (ref "LED79") (pin "3") (pinfunction "VSS_3") (pintype "passive"))
      (node (ref "LED8") (pin "3") (pinfunction "VSS_3") (pintype "passive"))
      (node (ref "LED80") (pin "3") (pinfunction "VSS_3") (pintype "passive"))
      (node (ref "LED81") (pin "3") (pinfunction "VSS_3") (pintype "passive"))
      (node (ref "LED82") (pin "3") (pinfunction "VSS_3") (pintype "passive"))
      (node (ref "LED83") (pin "3") (pinfunction "VSS_3") (pintype "passive"))
      (node (ref "LED84") (pin "3") (pinfunction "VSS_3") (pintype "passive"))
      (node (ref "LED85") (pin "3") (pinfunction "VSS_3") (pintype "passive"))
      (node (ref "LED86") (pin "3") (pinfunction "VSS_3") (pintype "passive"))
      (node (ref "LED87") (pin "3") (pinfunction "VSS_3") (pintype "passive"))
      (node (ref "LED88") (pin "3") (pinfunction "VSS_3") (pintype "passive"))
      (node (ref "LED89") (pin "3") (pinfunction "VSS_3") (pintype "passive"))
      (node (ref "LED9") (pin "3") (pinfunction "VSS_3") (pintype "passive"))
      (node (ref "LED90") (pin "3") (pinfunction "VSS_3") (pintype "passive"))
      (node (ref "LED91") (pin "3") (pinfunction "VSS_3") (pintype "passive"))
      (node (ref "LED92") (pin "3") (pinfunction "VSS_3") (pintype "passive"))
      (node (ref "LED93") (pin "3") (pinfunction "VSS_3") (pintype "passive"))
      (node (ref "LED94") (pin "3") (pinfunction "VSS_3") (pintype "passive"))
      (node (ref "LED95") (pin "3") (pinfunction "VSS_3") (pintype "passive"))
      (node (ref "LED96") (pin "3") (pinfunction "VSS_3") (pintype "passive"))
      (node (ref "LED97") (pin "3") (pinfunction "VSS_3") (pintype "passive"))
      (node (ref "LED98") (pin "3") (pinfunction "VSS_3") (pintype "passive"))
      (node (ref "LED99") (pin "3") (pinfunction "VSS_3") (pintype "passive"))
      (node (ref "P1") (pin "5") (pinfunction "5_5") (pintype "passive"))
      (node (ref "P2") (pin "1") (pinfunction "1_1") (pintype "passive"))
      (node (ref "QBOOT") (pin "4") (pinfunction "4_4") (pintype "passive"))
      (node (ref "QU1") (pin "19") (pinfunction "TESTEN_19") (pintype "passive"))
      (node (ref "QU1") (pin "57") (pinfunction "GND_57") (pintype "passive"))
      (node (ref "QU2") (pin "4") (pinfunction "GND_4") (pintype "passive"))
      (node (ref "QX1") (pin "2") (pinfunction "GND_2") (pintype "passive"))
      (node (ref "QX1") (pin "4") (pinfunction "GND_4") (pintype "passive"))
      (node (ref "R1") (pin "2") (pinfunction "2_2") (pintype "passive"))
      (node (ref "R16") (pin "1") (pinfunction "1_1") (pintype "passive"))
      (node (ref "R17") (pin "1") (pinfunction "1_1") (pintype "passive"))
      (node (ref "R19") (pin "1") (pinfunction "1_1") (pintype "passive"))
      (node (ref "R23") (pin "1") (pinfunction "1_1") (pintype "passive"))
      (node (ref "RPRST") (pin "4") (pinfunction "4_4") (pintype "passive"))
      (node (ref "RPUSB") (pin "4") (pinfunction "4_4") (pintype "passive"))
      (node (ref "RPUSB1") (pin "4") (pinfunction "4_4") (pintype "passive"))
      (node (ref "U1") (pin "3") (pinfunction "GND_3") (pintype "passive"))
      (node (ref "U10") (pin "3") (pinfunction "GND_3") (pintype "passive"))
      (node (ref "U11") (pin "3") (pinfunction "GND_3") (pintype "passive"))
      (node (ref "U12") (pin "11") (pinfunction "EP_11") (pintype "passive"))
      (node (ref "U12") (pin "8") (pinfunction "GND_8") (pintype "passive"))
      (node (ref "U2") (pin "1") (pinfunction "GND_1") (pintype "passive"))
      (node (ref "U3") (pin "5") (pinfunction "VSS_5") (pintype "passive"))
      (node (ref "U4") (pin "4") (pinfunction "VSS_4") (pintype "passive"))
      (node (ref "U5") (pin "9") (pinfunction "GND_9") (pintype "passive"))
      (node (ref "U6") (pin "17") (pinfunction "EP_17") (pintype "passive"))
      (node (ref "U6") (pin "2") (pinfunction "A0_2") (pintype "passive"))
      (node (ref "U6") (pin "3") (pinfunction "A1_3") (pintype "passive"))
      (node (ref "U6") (pin "4") (pinfunction "A2_4") (pintype "passive"))
      (node (ref "U6") (pin "9") (pinfunction "GND_9") (pintype "passive"))
      (node (ref "U7") (pin "2") (pinfunction "GND_2") (pintype "passive"))
      (node (ref "U8") (pin "3") (pinfunction "GND_3") (pintype "passive"))
      (node (ref "U9") (pin "3") (pinfunction "GND_3") (pintype "passive"))
      (node (ref "USB1") (pin "A1") (pinfunction "GND_A1") (pintype "passive"))
      (node (ref "USB1") (pin "A12") (pinfunction "GND_A12") (pintype "passive"))
      (node (ref "USB1") (pin "B1") (pinfunction "GND_B1") (pintype "passive"))
      (node (ref "USB1") (pin "B12") (pinfunction "GND_B12") (pintype "passive"))
    )
    (net (code "53") (name "Net-(D1-C)") (class "Default")
      (node (ref "C122") (pin "1") (pinfunction "1_1") (pintype "passive"))
      (node (ref "D1") (pin "1") (pinfunction "C_1") (pintype "passive"))
      (node (ref "JP4") (pin "2") (pinfunction "2_2") (pintype "passive"))
      (node (ref "LED115") (pin "1") (pinfunction "VDD_1") (pintype "passive"))
    )
    (net (code "54") (name "Net-(ESPFLASH-Pad2)") (class "Default")
      (node (ref "ESPFLASH") (pin "2") (pinfunction "2_2") (pintype "passive"))
      (node (ref "ESPRST") (pin "1") (pinfunction "1_1") (pintype "passive"))
    )
    (net (code "55") (name "Net-(ESPFLASH-Pad3)") (class "Default")
      (node (ref "ESPFLASH") (pin "3") (pinfunction "3_3") (pintype "passive"))
      (node (ref "JP15") (pin "1") (pinfunction "1_1") (pintype "passive"))
    )
    (net (code "56") (name "Net-(JP3-Pad1)") (class "Default")
      (node (ref "JP3") (pin "1") (pinfunction "1_1") (pintype "passive"))
      (node (ref "R12") (pin "1") (pinfunction "1_1") (pintype "passive"))
    )
    (net (code "57") (name "Net-(JP12-Pad1)") (class "Default")
      (node (ref "JP12") (pin "1") (pinfunction "1_1") (pintype "passive"))
      (node (ref "JP2") (pin "2") (pinfunction "2_2") (pintype "passive"))
    )
    (net (code "58") (name "Net-(JP13-Pad1)") (class "Default")
      (node (ref "JP13") (pin "1") (pinfunction "1_1") (pintype "passive"))
      (node (ref "JP9") (pin "2") (pinfunction "2_2") (pintype "passive"))
    )
    (net (code "59") (name "Net-(JP16-Pad2)") (class "Default")
      (node (ref "JP16") (pin "2") (pinfunction "2_2") (pintype "passive"))
      (node (ref "JP18") (pin "1") (pinfunction "1_1") (pintype "passive"))
    )
    (net (code "60") (name "Net-(JP17-Pad2)") (class "Default")
      (node (ref "JP17") (pin "2") (pinfunction "2_2") (pintype "passive"))
      (node (ref "JP19") (pin "1") (pinfunction "1_1") (pintype "passive"))
    )
    (net (code "61") (name "Net-(LED1-DIN)") (class "Default")
      (node (ref "LED1") (pin "4") (pinfunction "DIN_4") (pintype "passive"))
      (node (ref "LED16") (pin "2") (pinfunction "DOUT_2") (pintype "passive"))
    )
    (net (code "62") (name "Net-(LED1-DOUT)") (class "Default")
      (node (ref "LED1") (pin "2") (pinfunction "DOUT_2") (pintype "passive"))
      (node (ref "LED3") (pin "4") (pinfunction "DIN_4") (pintype "passive"))
    )
    (net (code "63") (name "Net-(LED2-+)") (class "Default")
      (node (ref "LED2") (pin "2") (pinfunction "+_2") (pintype "passive"))
      (node (ref "R25") (pin "2") (pinfunction "2_2") (pintype "passive"))
    )
    (net (code "64") (name "Net-(LED2--)") (class "Default")
      (node (ref "LED2") (pin "1") (pinfunction "-_1") (pintype "passive"))
      (node (ref "U6") (pin "13") (pinfunction "P7_13") (pintype "passive"))
    )
    (net (code "65") (name "Net-(LED6-DOUT)") (class "Default")
      (node (ref "LED6") (pin "2") (pinfunction "DOUT_2") (pintype "passive"))
      (node (ref "LED7") (pin "4") (pinfunction "DIN_4") (pintype "passive"))
    )
    (net (code "66") (name "Net-(LED8-DOUT)") (class "Default")
      (node (ref "LED8") (pin "2") (pinfunction "DOUT_2") (pintype "passive"))
      (node (ref "LED9") (pin "4") (pinfunction "DIN_4") (pintype "passive"))
    )
    (net (code "67") (name "Net-(LED10-DIN)") (class "Default")
      (node (ref "LED10") (pin "4") (pinfunction "DIN_4") (pintype "passive"))
      (node (ref "LED9") (pin "2") (pinfunction "DOUT_2") (pintype "passive"))
    )
    (net (code "68") (name "Net-(LED10-DOUT)") (class "Default")
      (node (ref "LED10") (pin "2") (pinfunction "DOUT_2") (pintype "passive"))
      (node (ref "LED11") (pin "4") (pinfunction "DIN_4") (pintype "passive"))
    )
    (net (code "69") (name "Net-(LED11-DOUT)") (class "Default")
      (node (ref "LED11") (pin "2") (pinfunction "DOUT_2") (pintype "passive"))
      (node (ref "LED12") (pin "4") (pinfunction "DIN_4") (pintype "passive"))
    )
    (net (code "70") (name "Net-(LED12-DOUT)") (class "Default")
      (node (ref "LED12") (pin "2") (pinfunction "DOUT_2") (pintype "passive"))
      (node (ref "LED15") (pin "4") (pinfunction "DIN_4") (pintype "passive"))
    )
    (net (code "71") (name "Net-(LED13-DIN)") (class "Default")
      (node (ref "LED13") (pin "4") (pinfunction "DIN_4") (pintype "passive"))
      (node (ref "LED14") (pin "2") (pinfunction "DOUT_2") (pintype "passive"))
    )
    (net (code "72") (name "Net-(LED13-DOUT)") (class "Default")
      (node (ref "LED13") (pin "2") (pinfunction "DOUT_2") (pintype "passive"))
      (node (ref "LED16") (pin "4") (pinfunction "DIN_4") (pintype "passive"))
    )
    (net (code "73") (name "Net-(LED14-DIN)") (class "Default")
      (node (ref "LED14") (pin "4") (pinfunction "DIN_4") (pintype "passive"))
      (node (ref "LED15") (pin "2") (pinfunction "DOUT_2") (pintype "passive"))
    )
    (net (code "74") (name "Net-(LED17-DIN)") (class "Default")
      (node (ref "LED17") (pin "4") (pinfunction "DIN_4") (pintype "passive"))
      (node (ref "LED7") (pin "2") (pinfunction "DOUT_2") (pintype "passive"))
    )
    (net (code "75") (name "Net-(LED17-DOUT)") (class "Default")
      (node (ref "LED17") (pin "2") (pinfunction "DOUT_2") (pintype "passive"))
      (node (ref "LED5") (pin "4") (pinfunction "DIN_4") (pintype "passive"))
    )
    (net (code "76") (name "Net-(LED18-DIN)") (class "Default")
      (node (ref "LED18") (pin "4") (pinfunction "DIN_4") (pintype "passive"))
      (node (ref "LED19") (pin "2") (pinfunction "DOUT_2") (pintype "passive"))
    )
    (net (code "77") (name "Net-(LED18-DOUT)") (class "Default")
      (node (ref "LED18") (pin "2") (pinfunction "DOUT_2") (pintype "passive"))
      (node (ref "LED6") (pin "4") (pinfunction "DIN_4") (pintype "passive"))
    )
    (net (code "78") (name "Net-(LED19-DIN)") (class "Default")
      (node (ref "LED19") (pin "4") (pinfunction "DIN_4") (pintype "passive"))
      (node (ref "LED20") (pin "2") (pinfunction "DOUT_2") (pintype "passive"))
    )
    (net (code "79") (name "Net-(LED20-DIN)") (class "Default")
      (node (ref "LED20") (pin "4") (pinfunction "DIN_4") (pintype "passive"))
      (node (ref "LED21") (pin "2") (pinfunction "DOUT_2") (pintype "passive"))
    )
    (net (code "80") (name "Net-(LED21-DIN)") (class "Default")
      (node (ref "LED21") (pin "4") (pinfunction "DIN_4") (pintype "passive"))
      (node (ref "LED22") (pin "2") (pinfunction "DOUT_2") (pintype "passive"))
    )
    (net (code "81") (name "Net-(LED23-DIN)") (class "Default")
      (node (ref "LED23") (pin "4") (pinfunction "DIN_4") (pintype "passive"))
      (node (ref "LED5") (pin "2") (pinfunction "DOUT_2") (pintype "passive"))
    )
    (net (code "82") (name "Net-(LED23-DOUT)") (class "Default")
      (node (ref "LED23") (pin "2") (pinfunction "DOUT_2") (pintype "passive"))
      (node (ref "LED4") (pin "4") (pinfunction "DIN_4") (pintype "passive"))
    )
    (net (code "83") (name "Net-(LED24-DIN)") (class "Default")
      (node (ref "LED24") (pin "4") (pinfunction "DIN_4") (pintype "passive"))
      (node (ref "LED33") (pin "2") (pinfunction "DOUT_2") (pintype "passive"))
    )
    (net (code "84") (name "Net-(LED24-DOUT)") (class "Default")
      (node (ref "LED24") (pin "2") (pinfunction "DOUT_2") (pintype "passive"))
      (node (ref "LED34") (pin "4") (pinfunction "DIN_4") (pintype "passive"))
    )
    (net (code "85") (name "Net-(LED25-DIN)") (class "Default")
      (node (ref "H1") (pin "2") (pinfunction "2_2") (pintype "passive"))
      (node (ref "H5") (pin "2") (pinfunction "2_2") (pintype "passive"))
      (node (ref "LED25") (pin "4") (pinfunction "DIN_4") (pintype "passive"))
      (node (ref "LED4") (pin "2") (pinfunction "DOUT_2") (pintype "passive"))
    )
    (net (code "86") (name "Net-(LED25-DOUT)") (class "Default")
      (node (ref "LED25") (pin "2") (pinfunction "DOUT_2") (pintype "passive"))
      (node (ref "LED26") (pin "4") (pinfunction "DIN_4") (pintype "passive"))
    )
    (net (code "87") (name "Net-(LED26-DOUT)") (class "Default")
      (node (ref "LED26") (pin "2") (pinfunction "DOUT_2") (pintype "passive"))
      (node (ref "LED27") (pin "4") (pinfunction "DIN_4") (pintype "passive"))
    )
    (net (code "88") (name "Net-(LED27-DOUT)") (class "Default")
      (node (ref "LED27") (pin "2") (pinfunction "DOUT_2") (pintype "passive"))
      (node (ref "LED28") (pin "4") (pinfunction "DIN_4") (pintype "passive"))
    )
    (net (code "89") (name "Net-(LED28-DOUT)") (class "Default")
      (node (ref "LED28") (pin "2") (pinfunction "DOUT_2") (pintype "passive"))
      (node (ref "LED29") (pin "4") (pinfunction "DIN_4") (pintype "passive"))
    )
    (net (code "90") (name "Net-(LED29-DOUT)") (class "Default")
      (node (ref "LED29") (pin "2") (pinfunction "DOUT_2") (pintype "passive"))
      (node (ref "LED32") (pin "4") (pinfunction "DIN_4") (pintype "passive"))
    )
    (net (code "91") (name "Net-(LED30-DIN)") (class "Default")
      (node (ref "LED30") (pin "4") (pinfunction "DIN_4") (pintype "passive"))
      (node (ref "LED31") (pin "2") (pinfunction "DOUT_2") (pintype "passive"))
    )
    (net (code "92") (name "Net-(LED30-DOUT)") (class "Default")
      (node (ref "LED30") (pin "2") (pinfunction "DOUT_2") (pintype "passive"))
      (node (ref "LED33") (pin "4") (pinfunction "DIN_4") (pintype "passive"))
    )
    (net (code "93") (name "Net-(LED31-DIN)") (class "Default")
      (node (ref "LED31") (pin "4") (pinfunction "DIN_4") (pintype "passive"))
      (node (ref "LED32") (pin "2") (pinfunction "DOUT_2") (pintype "passive"))
    )
    (net (code "94") (name "Net-(LED34-DOUT)") (class "Default")
      (node (ref "H6") (pin "2") (pinfunction "2_2") (pintype "passive"))
      (node (ref "H8") (pin "2") (pinfunction "2_2") (pintype "passive"))
      (node (ref "LED34") (pin "2") (pinfunction "DOUT_2") (pintype "passive"))
      (node (ref "LED44") (pin "4") (pinfunction "DIN_4") (pintype "passive"))
    )
    (net (code "95") (name "Net-(LED35-DIN)") (class "Default")
      (node (ref "LED35") (pin "4") (pinfunction "DIN_4") (pintype "passive"))
      (node (ref "LED45") (pin "2") (pinfunction "DOUT_2") (pintype "passive"))
    )
    (net (code "96") (name "Net-(LED35-DOUT)") (class "Default")
      (node (ref "H7") (pin "2") (pinfunction "2_2") (pintype "passive"))
      (node (ref "H9") (pin "2") (pinfunction "2_2") (pintype "passive"))
      (node (ref "LED35") (pin "2") (pinfunction "DOUT_2") (pintype "passive"))
      (node (ref "LED47") (pin "4") (pinfunction "DIN_4") (pintype "passive"))
    )
    (net (code "97") (name "Net-(LED36-DIN)") (class "Default")
      (node (ref "LED36") (pin "4") (pinfunction "DIN_4") (pintype "passive"))
      (node (ref "LED39") (pin "2") (pinfunction "DOUT_2") (pintype "passive"))
    )
    (net (code "98") (name "Net-(LED36-DOUT)") (class "Default")
      (node (ref "LED36") (pin "2") (pinfunction "DOUT_2") (pintype "passive"))
      (node (ref "LED45") (pin "4") (pinfunction "DIN_4") (pintype "passive"))
    )
    (net (code "99") (name "Net-(LED37-DIN)") (class "Default")
      (node (ref "LED37") (pin "4") (pinfunction "DIN_4") (pintype "passive"))
      (node (ref "LED40") (pin "2") (pinfunction "DOUT_2") (pintype "passive"))
    )
    (net (code "100") (name "Net-(LED37-DOUT)") (class "Default")
      (node (ref "LED37") (pin "2") (pinfunction "DOUT_2") (pintype "passive"))
      (node (ref "LED38") (pin "4") (pinfunction "DIN_4") (pintype "passive"))
    )
    (net (code "101") (name "Net-(LED38-DOUT)") (class "Default")
      (node (ref "LED38") (pin "2") (pinfunction "DOUT_2") (pintype "passive"))
      (node (ref "LED39") (pin "4") (pinfunction "DIN_4") (pintype "passive"))
    )
    (net (code "102") (name "Net-(LED40-DIN)") (class "Default")
      (node (ref "LED40") (pin "4") (pinfunction "DIN_4") (pintype "passive"))
      (node (ref "LED41") (pin "2") (pinfunction "DOUT_2") (pintype "passive"))
    )
    (net (code "103") (name "Net-(LED41-DIN)") (class "Default")
      (node (ref "LED41") (pin "4") (pinfunction "DIN_4") (pintype "passive"))
      (node (ref "LED42") (pin "2") (pinfunction "DOUT_2") (pintype "passive"))
    )
    (net (code "104") (name "Net-(LED42-DIN)") (class "Default")
      (node (ref "LED42") (pin "4") (pinfunction "DIN_4") (pintype "passive"))
      (node (ref "LED43") (pin "2") (pinfunction "DOUT_2") (pintype "passive"))
    )
    (net (code "105") (name "Net-(LED43-DIN)") (class "Default")
      (node (ref "LED43") (pin "4") (pinfunction "DIN_4") (pintype "passive"))
      (node (ref "LED44") (pin "2") (pinfunction "DOUT_2") (pintype "passive"))
    )
    (net (code "106") (name "Net-(LED46-DIN)") (class "Default")
      (node (ref "LED46") (pin "4") (pinfunction "DIN_4") (pintype "passive"))
      (node (ref "LED55") (pin "2") (pinfunction "DOUT_2") (pintype "passive"))
    )
    (net (code "107") (name "Net-(LED46-DOUT)") (class "Default")
      (node (ref "LED46") (pin "2") (pinfunction "DOUT_2") (pintype "passive"))
      (node (ref "LED56") (pin "4") (pinfunction "DIN_4") (pintype "passive"))
    )
    (net (code "108") (name "Net-(LED47-DOUT)") (class "Default")
      (node (ref "LED47") (pin "2") (pinfunction "DOUT_2") (pintype "passive"))
      (node (ref "LED48") (pin "4") (pinfunction "DIN_4") (pintype "passive"))
    )
    (net (code "109") (name "Net-(LED48-DOUT)") (class "Default")
      (node (ref "LED48") (pin "2") (pinfunction "DOUT_2") (pintype "passive"))
      (node (ref "LED49") (pin "4") (pinfunction "DIN_4") (pintype "passive"))
    )
    (net (code "110") (name "Net-(LED49-DOUT)") (class "Default")
      (node (ref "LED49") (pin "2") (pinfunction "DOUT_2") (pintype "passive"))
      (node (ref "LED50") (pin "4") (pinfunction "DIN_4") (pintype "passive"))
    )
    (net (code "111") (name "Net-(LED50-DOUT)") (class "Default")
      (node (ref "LED50") (pin "2") (pinfunction "DOUT_2") (pintype "passive"))
      (node (ref "LED51") (pin "4") (pinfunction "DIN_4") (pintype "passive"))
    )
    (net (code "112") (name "Net-(LED51-DOUT)") (class "Default")
      (node (ref "LED51") (pin "2") (pinfunction "DOUT_2") (pintype "passive"))
      (node (ref "LED54") (pin "4") (pinfunction "DIN_4") (pintype "passive"))
    )
    (net (code "113") (name "Net-(LED52-DIN)") (class "Default")
      (node (ref "LED52") (pin "4") (pinfunction "DIN_4") (pintype "passive"))
      (node (ref "LED53") (pin "2") (pinfunction "DOUT_2") (pintype "passive"))
    )
    (net (code "114") (name "Net-(LED52-DOUT)") (class "Default")
      (node (ref "LED52") (pin "2") (pinfunction "DOUT_2") (pintype "passive"))
      (node (ref "LED55") (pin "4") (pinfunction "DIN_4") (pintype "passive"))
    )
    (net (code "115") (name "Net-(LED53-DIN)") (class "Default")
      (node (ref "LED53") (pin "4") (pinfunction "DIN_4") (pintype "passive"))
      (node (ref "LED54") (pin "2") (pinfunction "DOUT_2") (pintype "passive"))
    )
    (net (code "116") (name "Net-(LED56-DOUT)") (class "Default")
      (node (ref "H10") (pin "2") (pinfunction "2_2") (pintype "passive"))
      (node (ref "H12") (pin "2") (pinfunction "2_2") (pintype "passive"))
      (node (ref "LED56") (pin "2") (pinfunction "DOUT_2") (pintype "passive"))
      (node (ref "LED66") (pin "4") (pinfunction "DIN_4") (pintype "passive"))
    )
    (net (code "117") (name "Net-(LED57-DIN)") (class "Default")
      (node (ref "LED57") (pin "4") (pinfunction "DIN_4") (pintype "passive"))
      (node (ref "LED67") (pin "2") (pinfunction "DOUT_2") (pintype "passive"))
    )
    (net (code "118") (name "Net-(LED57-DOUT)") (class "Default")
      (node (ref "H11") (pin "2") (pinfunction "2_2") (pintype "passive"))
      (node (ref "H13") (pin "2") (pinfunction "2_2") (pintype "passive"))
      (node (ref "LED57") (pin "2") (pinfunction "DOUT_2") (pintype "passive"))
      (node (ref "LED69") (pin "4") (pinfunction "DIN_4") (pintype "passive"))
    )
    (net (code "119") (name "Net-(LED58-DIN)") (class "Default")
      (node (ref "LED58") (pin "4") (pinfunction "DIN_4") (pintype "passive"))
      (node (ref "LED61") (pin "2") (pinfunction "DOUT_2") (pintype "passive"))
    )
    (net (code "120") (name "Net-(LED58-DOUT)") (class "Default")
      (node (ref "LED58") (pin "2") (pinfunction "DOUT_2") (pintype "passive"))
      (node (ref "LED67") (pin "4") (pinfunction "DIN_4") (pintype "passive"))
    )
    (net (code "121") (name "Net-(LED59-DIN)") (class "Default")
      (node (ref "LED59") (pin "4") (pinfunction "DIN_4") (pintype "passive"))
      (node (ref "LED62") (pin "2") (pinfunction "DOUT_2") (pintype "passive"))
    )
    (net (code "122") (name "Net-(LED59-DOUT)") (class "Default")
      (node (ref "LED59") (pin "2") (pinfunction "DOUT_2") (pintype "passive"))
      (node (ref "LED60") (pin "4") (pinfunction "DIN_4") (pintype "passive"))
    )
    (net (code "123") (name "Net-(LED60-DOUT)") (class "Default")
      (node (ref "LED60") (pin "2") (pinfunction "DOUT_2") (pintype "passive"))
      (node (ref "LED61") (pin "4") (pinfunction "DIN_4") (pintype "passive"))
    )
    (net (code "124") (name "Net-(LED62-DIN)") (class "Default")
      (node (ref "LED62") (pin "4") (pinfunction "DIN_4") (pintype "passive"))
      (node (ref "LED63") (pin "2") (pinfunction "DOUT_2") (pintype "passive"))
    )
    (net (code "125") (name "Net-(LED63-DIN)") (class "Default")
      (node (ref "LED63") (pin "4") (pinfunction "DIN_4") (pintype "passive"))
      (node (ref "LED64") (pin "2") (pinfunction "DOUT_2") (pintype "passive"))
    )
    (net (code "126") (name "Net-(LED64-DIN)") (class "Default")
      (node (ref "LED64") (pin "4") (pinfunction "DIN_4") (pintype "passive"))
      (node (ref "LED65") (pin "2") (pinfunction "DOUT_2") (pintype "passive"))
    )
    (net (code "127") (name "Net-(LED65-DIN)") (class "Default")
      (node (ref "LED65") (pin "4") (pinfunction "DIN_4") (pintype "passive"))
      (node (ref "LED66") (pin "2") (pinfunction "DOUT_2") (pintype "passive"))
    )
    (net (code "128") (name "Net-(LED68-DIN)") (class "Default")
      (node (ref "LED68") (pin "4") (pinfunction "DIN_4") (pintype "passive"))
      (node (ref "LED77") (pin "2") (pinfunction "DOUT_2") (pintype "passive"))
    )
    (net (code "129") (name "Net-(LED68-DOUT)") (class "Default")
      (node (ref "LED68") (pin "2") (pinfunction "DOUT_2") (pintype "passive"))
      (node (ref "LED78") (pin "4") (pinfunction "DIN_4") (pintype "passive"))
    )
    (net (code "130") (name "Net-(LED69-DOUT)") (class "Default")
      (node (ref "LED69") (pin "2") (pinfunction "DOUT_2") (pintype "passive"))
      (node (ref "LED70") (pin "4") (pinfunction "DIN_4") (pintype "passive"))
    )
    (net (code "131") (name "Net-(LED70-DOUT)") (class "Default")
      (node (ref "LED70") (pin "2") (pinfunction "DOUT_2") (pintype "passive"))
      (node (ref "LED71") (pin "4") (pinfunction "DIN_4") (pintype "passive"))
    )
    (net (code "132") (name "Net-(LED71-DOUT)") (class "Default")
      (node (ref "LED71") (pin "2") (pinfunction "DOUT_2") (pintype "passive"))
      (node (ref "LED72") (pin "4") (pinfunction "DIN_4") (pintype "passive"))
    )
    (net (code "133") (name "Net-(LED72-DOUT)") (class "Default")
      (node (ref "LED72") (pin "2") (pinfunction "DOUT_2") (pintype "passive"))
      (node (ref "LED73") (pin "4") (pinfunction "DIN_4") (pintype "passive"))
    )
    (net (code "134") (name "Net-(LED73-DOUT)") (class "Default")
      (node (ref "LED73") (pin "2") (pinfunction "DOUT_2") (pintype "passive"))
      (node (ref "LED76") (pin "4") (pinfunction "DIN_4") (pintype "passive"))
    )
    (net (code "135") (name "Net-(LED74-DIN)") (class "Default")
      (node (ref "LED74") (pin "4") (pinfunction "DIN_4") (pintype "passive"))
      (node (ref "LED75") (pin "2") (pinfunction "DOUT_2") (pintype "passive"))
    )
    (net (code "136") (name "Net-(LED74-DOUT)") (class "Default")
      (node (ref "LED74") (pin "2") (pinfunction "DOUT_2") (pintype "passive"))
      (node (ref "LED77") (pin "4") (pinfunction "DIN_4") (pintype "passive"))
    )
    (net (code "137") (name "Net-(LED75-DIN)") (class "Default")
      (node (ref "LED75") (pin "4") (pinfunction "DIN_4") (pintype "passive"))
      (node (ref "LED76") (pin "2") (pinfunction "DOUT_2") (pintype "passive"))
    )
    (net (code "138") (name "Net-(LED78-DOUT)") (class "Default")
      (node (ref "H14") (pin "2") (pinfunction "2_2") (pintype "passive"))
      (node (ref "H16") (pin "2") (pinfunction "2_2") (pintype "passive"))
      (node (ref "LED78") (pin "2") (pinfunction "DOUT_2") (pintype "passive"))
      (node (ref "LED88") (pin "4") (pinfunction "DIN_4") (pintype "passive"))
    )
    (net (code "139") (name "Net-(LED79-DIN)") (class "Default")
      (node (ref "LED79") (pin "4") (pinfunction "DIN_4") (pintype "passive"))
      (node (ref "LED89") (pin "2") (pinfunction "DOUT_2") (pintype "passive"))
    )
    (net (code "140") (name "Net-(LED79-DOUT)") (class "Default")
      (node (ref "H15") (pin "2") (pinfunction "2_2") (pintype "passive"))
      (node (ref "H17") (pin "2") (pinfunction "2_2") (pintype "passive"))
      (node (ref "LED79") (pin "2") (pinfunction "DOUT_2") (pintype "passive"))
      (node (ref "LED91") (pin "4") (pinfunction "DIN_4") (pintype "passive"))
    )
    (net (code "141") (name "Net-(LED80-DIN)") (class "Default")
      (node (ref "LED80") (pin "4") (pinfunction "DIN_4") (pintype "passive"))
      (node (ref "LED83") (pin "2") (pinfunction "DOUT_2") (pintype "passive"))
    )
    (net (code "142") (name "Net-(LED80-DOUT)") (class "Default")
      (node (ref "LED80") (pin "2") (pinfunction "DOUT_2") (pintype "passive"))
      (node (ref "LED89") (pin "4") (pinfunction "DIN_4") (pintype "passive"))
    )
    (net (code "143") (name "Net-(LED81-DIN)") (class "Default")
      (node (ref "LED81") (pin "4") (pinfunction "DIN_4") (pintype "passive"))
      (node (ref "LED84") (pin "2") (pinfunction "DOUT_2") (pintype "passive"))
    )
    (net (code "144") (name "Net-(LED81-DOUT)") (class "Default")
      (node (ref "LED81") (pin "2") (pinfunction "DOUT_2") (pintype "passive"))
      (node (ref "LED82") (pin "4") (pinfunction "DIN_4") (pintype "passive"))
    )
    (net (code "145") (name "Net-(LED82-DOUT)") (class "Default")
      (node (ref "LED82") (pin "2") (pinfunction "DOUT_2") (pintype "passive"))
      (node (ref "LED83") (pin "4") (pinfunction "DIN_4") (pintype "passive"))
    )
    (net (code "146") (name "Net-(LED84-DIN)") (class "Default")
      (node (ref "LED84") (pin "4") (pinfunction "DIN_4") (pintype "passive"))
      (node (ref "LED85") (pin "2") (pinfunction "DOUT_2") (pintype "passive"))
    )
    (net (code "147") (name "Net-(LED85-DIN)") (class "Default")
      (node (ref "LED85") (pin "4") (pinfunction "DIN_4") (pintype "passive"))
      (node (ref "LED86") (pin "2") (pinfunction "DOUT_2") (pintype "passive"))
    )
    (net (code "148") (name "Net-(LED86-DIN)") (class "Default")
      (node (ref "LED86") (pin "4") (pinfunction "DIN_4") (pintype "passive"))
      (node (ref "LED87") (pin "2") (pinfunction "DOUT_2") (pintype "passive"))
    )
    (net (code "149") (name "Net-(LED87-DIN)") (class "Default")
      (node (ref "LED87") (pin "4") (pinfunction "DIN_4") (pintype "passive"))
      (node (ref "LED88") (pin "2") (pinfunction "DOUT_2") (pintype "passive"))
    )
    (net (code "150") (name "Net-(LED90-DIN)") (class "Default")
      (node (ref "LED90") (pin "4") (pinfunction "DIN_4") (pintype "passive"))
      (node (ref "LED99") (pin "2") (pinfunction "DOUT_2") (pintype "passive"))
    )
    (net (code "151") (name "Net-(LED91-DOUT)") (class "Default")
      (node (ref "LED91") (pin "2") (pinfunction "DOUT_2") (pintype "passive"))
      (node (ref "LED92") (pin "4") (pinfunction "DIN_4") (pintype "passive"))
    )
    (net (code "152") (name "Net-(LED92-DOUT)") (class "Default")
      (node (ref "LED92") (pin "2") (pinfunction "DOUT_2") (pintype "passive"))
      (node (ref "LED93") (pin "4") (pinfunction "DIN_4") (pintype "passive"))
    )
    (net (code "153") (name "Net-(LED93-DOUT)") (class "Default")
      (node (ref "LED93") (pin "2") (pinfunction "DOUT_2") (pintype "passive"))
      (node (ref "LED94") (pin "4") (pinfunction "DIN_4") (pintype "passive"))
    )
    (net (code "154") (name "Net-(LED94-DOUT)") (class "Default")
      (node (ref "LED94") (pin "2") (pinfunction "DOUT_2") (pintype "passive"))
      (node (ref "LED95") (pin "4") (pinfunction "DIN_4") (pintype "passive"))
    )
    (net (code "155") (name "Net-(LED95-DOUT)") (class "Default")
      (node (ref "LED95") (pin "2") (pinfunction "DOUT_2") (pintype "passive"))
      (node (ref "LED98") (pin "4") (pinfunction "DIN_4") (pintype "passive"))
    )
    (net (code "156") (name "Net-(LED96-DIN)") (class "Default")
      (node (ref "LED96") (pin "4") (pinfunction "DIN_4") (pintype "passive"))
      (node (ref "LED97") (pin "2") (pinfunction "DOUT_2") (pintype "passive"))
    )
    (net (code "157") (name "Net-(LED96-DOUT)") (class "Default")
      (node (ref "LED96") (pin "2") (pinfunction "DOUT_2") (pintype "passive"))
      (node (ref "LED99") (pin "4") (pinfunction "DIN_4") (pintype "passive"))
    )
    (net (code "158") (name "Net-(LED97-DIN)") (class "Default")
      (node (ref "LED97") (pin "4") (pinfunction "DIN_4") (pintype "passive"))
      (node (ref "LED98") (pin "2") (pinfunction "DOUT_2") (pintype "passive"))
    )
    (net (code "159") (name "Net-(LED100-DIN)") (class "Default")
      (node (ref "LED100") (pin "4") (pinfunction "DIN_4") (pintype "passive"))
      (node (ref "LED90") (pin "2") (pinfunction "DOUT_2") (pintype "passive"))
    )
    (net (code "160") (name "Net-(LED100-DOUT)") (class "Default")
      (node (ref "H18") (pin "2") (pinfunction "2_2") (pintype "passive"))
      (node (ref "LED100") (pin "2") (pinfunction "DOUT_2") (pintype "passive"))
      (node (ref "LED113") (pin "4") (pinfunction "DIN_4") (pintype "passive"))
    )
    (net (code "161") (name "Net-(LED101-DIN)") (class "Default")
      (node (ref "LED101") (pin "4") (pinfunction "DIN_4") (pintype "passive"))
      (node (ref "LED111") (pin "2") (pinfunction "DOUT_2") (pintype "passive"))
    )
    (net (code "162") (name "Net-(LED101-DOUT)") (class "Default")
      (node (ref "H19") (pin "2") (pinfunction "2_2") (pintype "passive"))
      (node (ref "LED101") (pin "2") (pinfunction "DOUT_2") (pintype "passive"))
      (node (ref "LED112") (pin "4") (pinfunction "DIN_4") (pintype "passive"))
    )
    (net (code "163") (name "Net-(LED102-DIN)") (class "Default")
      (node (ref "LED102") (pin "4") (pinfunction "DIN_4") (pintype "passive"))
      (node (ref "LED105") (pin "2") (pinfunction "DOUT_2") (pintype "passive"))
    )
    (net (code "164") (name "Net-(LED102-DOUT)") (class "Default")
      (node (ref "LED102") (pin "2") (pinfunction "DOUT_2") (pintype "passive"))
      (node (ref "LED111") (pin "4") (pinfunction "DIN_4") (pintype "passive"))
    )
    (net (code "165") (name "Net-(LED103-DIN)") (class "Default")
      (node (ref "LED103") (pin "4") (pinfunction "DIN_4") (pintype "passive"))
      (node (ref "LED106") (pin "2") (pinfunction "DOUT_2") (pintype "passive"))
    )
    (net (code "166") (name "Net-(LED103-DOUT)") (class "Default")
      (node (ref "LED103") (pin "2") (pinfunction "DOUT_2") (pintype "passive"))
      (node (ref "LED104") (pin "4") (pinfunction "DIN_4") (pintype "passive"))
    )
    (net (code "167") (name "Net-(LED104-DOUT)") (class "Default")
      (node (ref "LED104") (pin "2") (pinfunction "DOUT_2") (pintype "passive"))
      (node (ref "LED105") (pin "4") (pinfunction "DIN_4") (pintype "passive"))
    )
    (net (code "168") (name "Net-(LED106-DIN)") (class "Default")
      (node (ref "LED106") (pin "4") (pinfunction "DIN_4") (pintype "passive"))
      (node (ref "LED107") (pin "2") (pinfunction "DOUT_2") (pintype "passive"))
    )
    (net (code "169") (name "Net-(LED107-DIN)") (class "Default")
      (node (ref "LED107") (pin "4") (pinfunction "DIN_4") (pintype "passive"))
      (node (ref "LED108") (pin "2") (pinfunction "DOUT_2") (pintype "passive"))
    )
    (net (code "170") (name "Net-(LED108-DIN)") (class "Default")
      (node (ref "LED108") (pin "4") (pinfunction "DIN_4") (pintype "passive"))
      (node (ref "LED109") (pin "2") (pinfunction "DOUT_2") (pintype "passive"))
    )
    (net (code "171") (name "Net-(LED109-DIN)") (class "Default")
      (node (ref "LED109") (pin "4") (pinfunction "DIN_4") (pintype "passive"))
      (node (ref "LED110") (pin "2") (pinfunction "DOUT_2") (pintype "passive"))
    )
    (net (code "172") (name "Net-(LED110-DIN)") (class "Default")
      (node (ref "H20") (pin "2") (pinfunction "2_2") (pintype "passive"))
      (node (ref "LED110") (pin "4") (pinfunction "DIN_4") (pintype "passive"))
      (node (ref "LED113") (pin "2") (pinfunction "DOUT_2") (pintype "passive"))
    )
    (net (code "173") (name "Net-(LED114-DIN)") (class "Default")
      (node (ref "H3") (pin "2") (pinfunction "2_2") (pintype "passive"))
      (node (ref "LED114") (pin "4") (pinfunction "DIN_4") (pintype "passive"))
      (node (ref "LED3") (pin "2") (pinfunction "DOUT_2") (pintype "passive"))
    )
    (net (code "174") (name "Net-(LED114-DOUT)") (class "Default")
      (node (ref "H4") (pin "2") (pinfunction "2_2") (pintype "passive"))
      (node (ref "LED114") (pin "2") (pinfunction "DOUT_2") (pintype "passive"))
      (node (ref "LED22") (pin "4") (pinfunction "DIN_4") (pintype "passive"))
    )
    (net (code "175") (name "Net-(LED116-+)") (class "Default")
      (node (ref "LED116") (pin "2") (pinfunction "+_2") (pintype "passive"))
      (node (ref "R13") (pin "2") (pinfunction "2_2") (pintype "passive"))
    )
    (net (code "176") (name "Net-(P3-Pad1)") (class "Default")
      (node (ref "P3") (pin "1") (pinfunction "1_1") (pintype "passive"))
      (node (ref "QBOOT") (pin "3") (pinfunction "3_3") (pintype "passive"))
    )
    (net (code "177") (name "Net-(P3-Pad2)") (class "Default")
      (node (ref "P3") (pin "2") (pinfunction "2_2") (pintype "passive"))
      (node (ref "QBOOT") (pin "1") (pinfunction "1_1") (pintype "passive"))
    )
    (net (code "178") (name "Net-(QBOOT-Pad2)") (class "Default")
      (node (ref "QBOOT") (pin "2") (pinfunction "2_2") (pintype "passive"))
      (node (ref "R11") (pin "2") (pinfunction "2_2") (pintype "passive"))
    )
    (net (code "179") (name "Net-(QU1-USB_DM)") (class "Default")
      (node (ref "QU1") (pin "46") (pinfunction "USB_DM_46") (pintype "passive"))
      (node (ref "R9") (pin "1") (pinfunction "1_1") (pintype "passive"))
    )
    (net (code "180") (name "Net-(QU1-USB_DP)") (class "Default")
      (node (ref "QU1") (pin "47") (pinfunction "USB_DP_47") (pintype "passive"))
      (node (ref "R7") (pin "1") (pinfunction "1_1") (pintype "passive"))
    )
    (net (code "181") (name "Net-(U1-ADDR)") (class "Default")
      (node (ref "R1") (pin "1") (pinfunction "1_1") (pintype "passive"))
      (node (ref "U1") (pin "2") (pinfunction "ADDR_2") (pintype "passive"))
    )
    (net (code "182") (name "Net-(U1-DVI)") (class "Default")
      (node (ref "C7") (pin "1") (pinfunction "1_1") (pintype "passive"))
      (node (ref "R2") (pin "1") (pinfunction "1_1") (pintype "passive"))
      (node (ref "U1") (pin "5") (pinfunction "DVI_5") (pintype "passive"))
    )
    (net (code "183") (name "Net-(U3-OSCI)") (class "Default")
      (node (ref "U3") (pin "1") (pinfunction "OSCI_1") (pintype "passive"))
      (node (ref "X1") (pin "1") (pinfunction "OSC1_1") (pintype "passive"))
    )
    (net (code "184") (name "Net-(U3-OSCO)") (class "Default")
      (node (ref "U3") (pin "2") (pinfunction "OSCO_2") (pintype "passive"))
      (node (ref "X1") (pin "2") (pinfunction "OSC2_2") (pintype "passive"))
    )
    (net (code "185") (name "Net-(U3-VBAT)") (class "Default")
      (node (ref "BT1") (pin "1") (pinfunction "1_1") (pintype "passive"))
      (node (ref "BT2") (pin "1") (pinfunction "1_1") (pintype "passive"))
      (node (ref "U3") (pin "3") (pinfunction "VBAT_3") (pintype "passive"))
    )
    (net (code "186") (name "Net-(U5-EN)") (class "Default")
      (node (ref "R8") (pin "1") (pinfunction "1_1") (pintype "passive"))
      (node (ref "U5") (pin "3") (pinfunction "EN_3") (pintype "passive"))
    )
    (net (code "187") (name "Net-(U5-GPIO0)") (class "Default")
      (node (ref "ESPFLASH") (pin "4") (pinfunction "4_4") (pintype "passive"))
      (node (ref "R14") (pin "2") (pinfunction "2_2") (pintype "passive"))
      (node (ref "U5") (pin "12") (pinfunction "GPIO0_12") (pintype "passive"))
    )
    (net (code "188") (name "Net-(U5-GPIO2)") (class "Default")
      (node (ref "R15") (pin "2") (pinfunction "2_2") (pintype "passive"))
      (node (ref "U5") (pin "11") (pinfunction "GPIO2_11") (pintype "passive"))
    )
    (net (code "189") (name "Net-(U5-GPIO15)") (class "Default")
      (node (ref "R16") (pin "2") (pinfunction "2_2") (pintype "passive"))
      (node (ref "U5") (pin "10") (pinfunction "GPIO15_10") (pintype "passive"))
    )
    (net (code "190") (name "Net-(U5-GPIO16)") (class "Default")
      (node (ref "ESPRST") (pin "3") (pinfunction "3_3") (pintype "passive"))
      (node (ref "JP14") (pin "1") (pinfunction "1_1") (pintype "passive"))
      (node (ref "P2") (pin "5") (pinfunction "5_5") (pintype "passive"))
      (node (ref "R6") (pin "1") (pinfunction "1_1") (pintype "passive"))
      (node (ref "U5") (pin "1") (pinfunction "RST_1") (pintype "passive"))
      (node (ref "U5") (pin "4") (pinfunction "GPIO16_4") (pintype "passive"))
    )
    (net (code "191") (name "Net-(U5-RXD0)") (class "Default")
      (node (ref "JP11") (pin "1") (pinfunction "1_1") (pintype "passive"))
      (node (ref "P2") (pin "3") (pinfunction "3_3") (pintype "passive"))
      (node (ref "U5") (pin "15") (pinfunction "RXD0_15") (pintype "passive"))
    )
    (net (code "192") (name "Net-(U5-TXD0)") (class "Default")
      (node (ref "JP10") (pin "1") (pinfunction "1_1") (pintype "passive"))
      (node (ref "P2") (pin "4") (pinfunction "4_4") (pintype "passive"))
      (node (ref "U5") (pin "16") (pinfunction "TXD0_16") (pintype "passive"))
    )
    (net (code "193") (name "Net-(U6-P2)") (class "Default")
      (node (ref "R20") (pin "1") (pinfunction "1_1") (pintype "passive"))
      (node (ref "U6") (pin "7") (pinfunction "P2_7") (pintype "passive"))
      (node (ref "U9") (pin "2") (pinfunction "VOUT_2") (pintype "passive"))
    )
    (net (code "194") (name "Net-(U6-P3)") (class "Default")
      (node (ref "R18") (pin "1") (pinfunction "1_1") (pintype "passive"))
      (node (ref "U6") (pin "8") (pinfunction "P3_8") (pintype "passive"))
      (node (ref "U8") (pin "2") (pinfunction "VOUT_2") (pintype "passive"))
    )
    (net (code "195") (name "Net-(U6-SCL)") (class "Default")
      (node (ref "JP9") (pin "1") (pinfunction "1_1") (pintype "passive"))
      (node (ref "U6") (pin "15") (pinfunction "SCL_15") (pintype "passive"))
    )
    (net (code "196") (name "Net-(U6-SDA)") (class "Default")
      (node (ref "JP2") (pin "1") (pinfunction "1_1") (pintype "passive"))
      (node (ref "U6") (pin "16") (pinfunction "SDA_16") (pintype "passive"))
    )
    (net (code "197") (name "Net-(U7-A)") (class "Default")
      (node (ref "JP8") (pin "1") (pinfunction "1_1") (pintype "passive"))
      (node (ref "R10") (pin "2") (pinfunction "2_2") (pintype "passive"))
      (node (ref "U7") (pin "3") (pinfunction "A_3") (pintype "passive"))
    )
    (net (code "198") (name "Net-(U7-B)") (class "Default")
      (node (ref "JP6") (pin "2") (pinfunction "2_2") (pintype "passive"))
      (node (ref "JP7") (pin "2") (pinfunction "2_2") (pintype "passive"))
      (node (ref "JP8") (pin "2") (pinfunction "2_2") (pintype "passive"))
      (node (ref "U7") (pin "4") (pinfunction "B_4") (pintype "passive"))
    )
    (net (code "199") (name "Net-(U7-OE)") (class "Default")
      (node (ref "JP1") (pin "2") (pinfunction "2_2") (pintype "passive"))
      (node (ref "U7") (pin "5") (pinfunction "OE_5") (pintype "passive"))
    )
    (net (code "200") (name "Net-(U10-VOUT)") (class "Default")
      (node (ref "R21") (pin "1") (pinfunction "1_1") (pintype "passive"))
      (node (ref "U10") (pin "2") (pinfunction "VOUT_2") (pintype "passive"))
      (node (ref "U6") (pin "6") (pinfunction "P1_6") (pintype "passive"))
    )
    (net (code "201") (name "Net-(U11-VOUT)") (class "Default")
      (node (ref "R22") (pin "1") (pinfunction "1_1") (pintype "passive"))
      (node (ref "U11") (pin "2") (pinfunction "VOUT_2") (pintype "passive"))
      (node (ref "U6") (pin "5") (pinfunction "P0_5") (pintype "passive"))
    )
    (net (code "202") (name "Net-(U12-#EN)") (class "Default")
      (node (ref "PWRRST") (pin "4") (pinfunction "4_4") (pintype "passive"))
      (node (ref "R23") (pin "2") (pinfunction "2_2") (pintype "passive"))
      (node (ref "U12") (pin "3") (pinfunction "#EN_3") (pintype "passive"))
    )
    (net (code "203") (name "Net-(USB1-CC1)") (class "Default")
      (node (ref "R17") (pin "2") (pinfunction "2_2") (pintype "passive"))
      (node (ref "USB1") (pin "A5") (pinfunction "CC1_A5") (pintype "passive"))
    )
    (net (code "204") (name "Net-(USB1-CC2)") (class "Default")
      (node (ref "R19") (pin "2") (pinfunction "2_2") (pintype "passive"))
      (node (ref "USB1") (pin "B5") (pinfunction "CC2_B5") (pintype "passive"))
    )
    (net (code "205") (name "VCC") (class "Default")
      (node (ref "C10") (pin "2") (pinfunction "2_2") (pintype "passive"))
      (node (ref "C125") (pin "2") (pinfunction "2_2") (pintype "passive"))
      (node (ref "C126") (pin "2") (pinfunction "2_2") (pintype "passive"))
      (node (ref "C127") (pin "2") (pinfunction "2_2") (pintype "passive"))
      (node (ref "C128") (pin "2") (pinfunction "2_2") (pintype "passive"))
      (node (ref "C129") (pin "1") (pinfunction "1_1") (pintype "passive"))
      (node (ref "C130") (pin "1") (pinfunction "1_1") (pintype "passive"))
      (node (ref "C131") (pin "2") (pinfunction "2_2") (pintype "passive"))
      (node (ref "C132") (pin "2") (pinfunction "2_2") (pintype "passive"))
      (node (ref "C133") (pin "2") (pinfunction "2_2") (pintype "passive"))
      (node (ref "C136") (pin "1") (pinfunction "1_1") (pintype "passive"))
      (node (ref "C139") (pin "2") (pinfunction "2_2") (pintype "passive"))
      (node (ref "C3") (pin "1") (pinfunction "1_1") (pintype "passive"))
      (node (ref "C4") (pin "1") (pinfunction "1_1") (pintype "passive"))
      (node (ref "C6") (pin "2") (pinfunction "2_2") (pintype "passive"))
      (node (ref "C9") (pin "1") (pinfunction "1_1") (pintype "passive"))
      (node (ref "H21") (pin "2") (pinfunction "2_2") (pintype "passive"))
      (node (ref "JP1") (pin "1") (pinfunction "1_1") (pintype "passive"))
      (node (ref "JP3") (pin "2") (pinfunction "2_2") (pintype "passive"))
      (node (ref "P1") (pin "1") (pinfunction "1_1") (pintype "passive"))
      (node (ref "P2") (pin "2") (pinfunction "2_2") (pintype "passive"))
      (node (ref "QU1") (pin "1") (pinfunction "IOVDD_1") (pintype "passive"))
      (node (ref "QU1") (pin "10") (pinfunction "IOVDD_10") (pintype "passive"))
      (node (ref "QU1") (pin "22") (pinfunction "IOVDD_22") (pintype "passive"))
      (node (ref "QU1") (pin "33") (pinfunction "IOVDD_33") (pintype "passive"))
      (node (ref "QU1") (pin "42") (pinfunction "IOVDD_42") (pintype "passive"))
      (node (ref "QU1") (pin "43") (pinfunction "ADC_AVDD_43") (pintype "passive"))
      (node (ref "QU1") (pin "44") (pinfunction "VREG_IN_44") (pintype "passive"))
      (node (ref "QU1") (pin "48") (pinfunction "USB_VDD_48") (pintype "passive"))
      (node (ref "QU1") (pin "49") (pinfunction "IOVDD_49") (pintype "passive"))
      (node (ref "QU2") (pin "8") (pinfunction "VCC_8") (pintype "passive"))
      (node (ref "R14") (pin "1") (pinfunction "1_1") (pintype "passive"))
      (node (ref "R15") (pin "1") (pinfunction "1_1") (pintype "passive"))
      (node (ref "R18") (pin "2") (pinfunction "2_2") (pintype "passive"))
      (node (ref "R2") (pin "2") (pinfunction "2_2") (pintype "passive"))
      (node (ref "R20") (pin "2") (pinfunction "2_2") (pintype "passive"))
      (node (ref "R21") (pin "2") (pinfunction "2_2") (pintype "passive"))
      (node (ref "R22") (pin "2") (pinfunction "2_2") (pintype "passive"))
      (node (ref "R24") (pin "2") (pinfunction "2_2") (pintype "passive"))
      (node (ref "R25") (pin "1") (pinfunction "1_1") (pintype "passive"))
      (node (ref "R3") (pin "1") (pinfunction "1_1") (pintype "passive"))
      (node (ref "R4") (pin "1") (pinfunction "1_1") (pintype "passive"))
      (node (ref "R5") (pin "2") (pinfunction "2_2") (pintype "passive"))
      (node (ref "R6") (pin "2") (pinfunction "2_2") (pintype "passive"))
      (node (ref "R8") (pin "2") (pinfunction "2_2") (pintype "passive"))
      (node (ref "U1") (pin "1") (pinfunction "VCC_1") (pintype "passive"))
      (node (ref "U10") (pin "1") (pinfunction "VCC_1") (pintype "passive"))
      (node (ref "U11") (pin "1") (pinfunction "VCC_1") (pintype "passive"))
      (node (ref "U2") (pin "2") (pinfunction "Out_2") (pintype "passive"))
      (node (ref "U3") (pin "10") (pinfunction "VDD_10") (pintype "passive"))
      (node (ref "U4") (pin "8") (pinfunction "VCC_8") (pintype "passive"))
      (node (ref "U5") (pin "8") (pinfunction "VCC_8") (pintype "passive"))
      (node (ref "U6") (pin "1") (pinfunction "VCC_1") (pintype "passive"))
      (node (ref "U7") (pin "6") (pinfunction "VCCB_6") (pintype "passive"))
      (node (ref "U8") (pin "1") (pinfunction "VCC_1") (pintype "passive"))
      (node (ref "U9") (pin "1") (pinfunction "VCC_1") (pintype "passive"))
    )
    (net (code "206") (name "unconnected-(ESPFLASH-Pad1)") (class "Default")
      (node (ref "ESPFLASH") (pin "1") (pinfunction "1_1") (pintype "passive+no_connect"))
    )
    (net (code "207") (name "unconnected-(ESPRST-Pad4)") (class "Default")
      (node (ref "ESPRST") (pin "4") (pinfunction "4_4") (pintype "passive+no_connect"))
    )
    (net (code "208") (name "unconnected-(LED112-DOUT-Pad2)") (class "Default")
      (node (ref "LED112") (pin "2") (pinfunction "DOUT_2") (pintype "passive"))
    )
    (net (code "209") (name "unconnected-(PWRRST-Pad1)") (class "Default")
      (node (ref "PWRRST") (pin "1") (pinfunction "1_1") (pintype "passive+no_connect"))
    )
    (net (code "210") (name "unconnected-(PWRRST-Pad3)") (class "Default")
      (node (ref "PWRRST") (pin "3") (pinfunction "3_3") (pintype "passive+no_connect"))
    )
    (net (code "211") (name "unconnected-(QU2-EP-Pad9)") (class "Default")
      (node (ref "QU2") (pin "9") (pinfunction "EP_9") (pintype "passive"))
    )
    (net (code "212") (name "unconnected-(RPRST-Pad1)") (class "Default")
      (node (ref "RPRST") (pin "1") (pinfunction "1_1") (pintype "passive+no_connect"))
    )
    (net (code "213") (name "unconnected-(RPRST-Pad3)") (class "Default")
      (node (ref "RPRST") (pin "3") (pinfunction "3_3") (pintype "passive+no_connect"))
    )
    (net (code "214") (name "unconnected-(U1-EP-Pad7)") (class "Default")
      (node (ref "U1") (pin "7") (pinfunction "EP_7") (pintype "passive+no_connect"))
    )
    (net (code "215") (name "unconnected-(U2-TAB-Pad4)") (class "Default")
      (node (ref "U2") (pin "4") (pinfunction "TAB_4") (pintype "passive"))
    )
    (net (code "216") (name "unconnected-(U3-CLK-Pad8)") (class "Default")
      (node (ref "U3") (pin "8") (pinfunction "CLK_8") (pintype "passive+no_connect"))
    )
    (net (code "217") (name "unconnected-(U3-EP-Pad11)") (class "Default")
      (node (ref "U3") (pin "11") (pinfunction "EP_11") (pintype "passive+no_connect"))
    )
    (net (code "218") (name "unconnected-(U3-INTA#(CLK)-Pad9)") (class "Default")
      (node (ref "U3") (pin "9") (pinfunction "INTA#(CLK)_9") (pintype "passive+no_connect"))
    )
    (net (code "219") (name "unconnected-(U3-TS(CLK{slash}INTB)#-Pad4)") (class "Default")
      (node (ref "U3") (pin "4") (pinfunction "TS(CLK/INTB)#_4") (pintype "passive+no_connect"))
    )
    (net (code "220") (name "unconnected-(U4-E1-Pad1)") (class "Default")
      (node (ref "U4") (pin "1") (pinfunction "E1_1") (pintype "passive+no_connect"))
    )
    (net (code "221") (name "unconnected-(U4-E2-Pad2)") (class "Default")
      (node (ref "U4") (pin "2") (pinfunction "E2_2") (pintype "passive+no_connect"))
    )
    (net (code "222") (name "unconnected-(U4-E3-Pad3)") (class "Default")
      (node (ref "U4") (pin "3") (pinfunction "E3_3") (pintype "passive+no_connect"))
    )
    (net (code "223") (name "unconnected-(U4-WC#-Pad7)") (class "Default")
      (node (ref "U4") (pin "7") (pinfunction "WC#_7") (pintype "passive+no_connect"))
    )
    (net (code "224") (name "unconnected-(U5-ADC-Pad2)") (class "Default")
      (node (ref "U5") (pin "2") (pinfunction "ADC_2") (pintype "passive"))
    )
    (net (code "225") (name "unconnected-(U5-CS0-Pad17)") (class "Default")
      (node (ref "U5") (pin "17") (pinfunction "CS0_17") (pintype "passive"))
    )
    (net (code "226") (name "unconnected-(U5-GPIO4-Pad13)") (class "Default")
      (node (ref "U5") (pin "13") (pinfunction "GPIO4_13") (pintype "passive"))
    )
    (net (code "227") (name "unconnected-(U5-GPIO5-Pad14)") (class "Default")
      (node (ref "U5") (pin "14") (pinfunction "GPIO5_14") (pintype "passive"))
    )
    (net (code "228") (name "unconnected-(U5-GPIO9-Pad19)") (class "Default")
      (node (ref "U5") (pin "19") (pinfunction "GPIO9_19") (pintype "passive"))
    )
    (net (code "229") (name "unconnected-(U5-GPIO10-Pad20)") (class "Default")
      (node (ref "U5") (pin "20") (pinfunction "GPIO10_20") (pintype "passive"))
    )
    (net (code "230") (name "unconnected-(U5-GPIO12-Pad6)") (class "Default")
      (node (ref "U5") (pin "6") (pinfunction "GPIO12_6") (pintype "passive"))
    )
    (net (code "231") (name "unconnected-(U5-GPIO13-Pad7)") (class "Default")
      (node (ref "U5") (pin "7") (pinfunction "GPIO13_7") (pintype "passive"))
    )
    (net (code "232") (name "unconnected-(U5-GPIO14-Pad5)") (class "Default")
      (node (ref "U5") (pin "5") (pinfunction "GPIO14_5") (pintype "passive"))
    )
    (net (code "233") (name "unconnected-(U5-MISO-Pad18)") (class "Default")
      (node (ref "U5") (pin "18") (pinfunction "MISO_18") (pintype "passive"))
    )
    (net (code "234") (name "unconnected-(U5-MOSI-Pad21)") (class "Default")
      (node (ref "U5") (pin "21") (pinfunction "MOSI_21") (pintype "passive"))
    )
    (net (code "235") (name "unconnected-(U5-SCLK-Pad22)") (class "Default")
      (node (ref "U5") (pin "22") (pinfunction "SCLK_22") (pintype "passive"))
    )
    (net (code "236") (name "unconnected-(U6-INT#-Pad14)") (class "Default")
      (node (ref "U6") (pin "14") (pinfunction "INT#_14") (pintype "passive+no_connect"))
    )
    (net (code "237") (name "unconnected-(U6-P5-Pad11)") (class "Default")
      (node (ref "U6") (pin "11") (pinfunction "P5_11") (pintype "passive+no_connect"))
    )
    (net (code "238") (name "unconnected-(U6-P6-Pad12)") (class "Default")
      (node (ref "U6") (pin "12") (pinfunction "P6_12") (pintype "passive+no_connect"))
    )
    (net (code "239") (name "unconnected-(U12-ID-Pad5)") (class "Default")
      (node (ref "U12") (pin "5") (pinfunction "ID_5") (pintype "passive+no_connect"))
    )
    (net (code "240") (name "unconnected-(USB1-EH-Pad17)") (class "Default")
      (node (ref "USB1") (pin "17") (pinfunction "EH_17") (pintype "passive+no_connect"))
    )
    (net (code "241") (name "unconnected-(USB1-EH-Pad18)") (class "Default")
      (node (ref "USB1") (pin "18") (pinfunction "EH_18") (pintype "passive+no_connect"))
    )
    (net (code "242") (name "unconnected-(USB1-EH-Pad19)") (class "Default")
      (node (ref "USB1") (pin "19") (pinfunction "EH_19") (pintype "passive"))
    )
    (net (code "243") (name "unconnected-(USB1-EH-Pad20)") (class "Default")
      (node (ref "USB1") (pin "20") (pinfunction "EH_20") (pintype "passive"))
    )
    (net (code "244") (name "unconnected-(USB1-SBU1-PadA8)") (class "Default")
      (node (ref "USB1") (pin "A8") (pinfunction "SBU1_A8") (pintype "passive"))
    )
    (net (code "245") (name "unconnected-(USB1-SBU2-PadB8)") (class "Default")
      (node (ref "USB1") (pin "B8") (pinfunction "SBU2_B8") (pintype "passive"))
    )
    (net (code "246") (name "unconnected-(USB1-VBUS-PadA9)") (class "Default")
      (node (ref "USB1") (pin "A9") (pinfunction "VBUS_A9") (pintype "passive"))
    )
    (net (code "247") (name "unconnected-(USB1-VBUS-PadB4)") (class "Default")
      (node (ref "USB1") (pin "B4") (pinfunction "VBUS_B4") (pintype "passive"))
    )
  )
)
